# Sheet4.net
KiCad netlist of a schematic drawn in Altium Designer
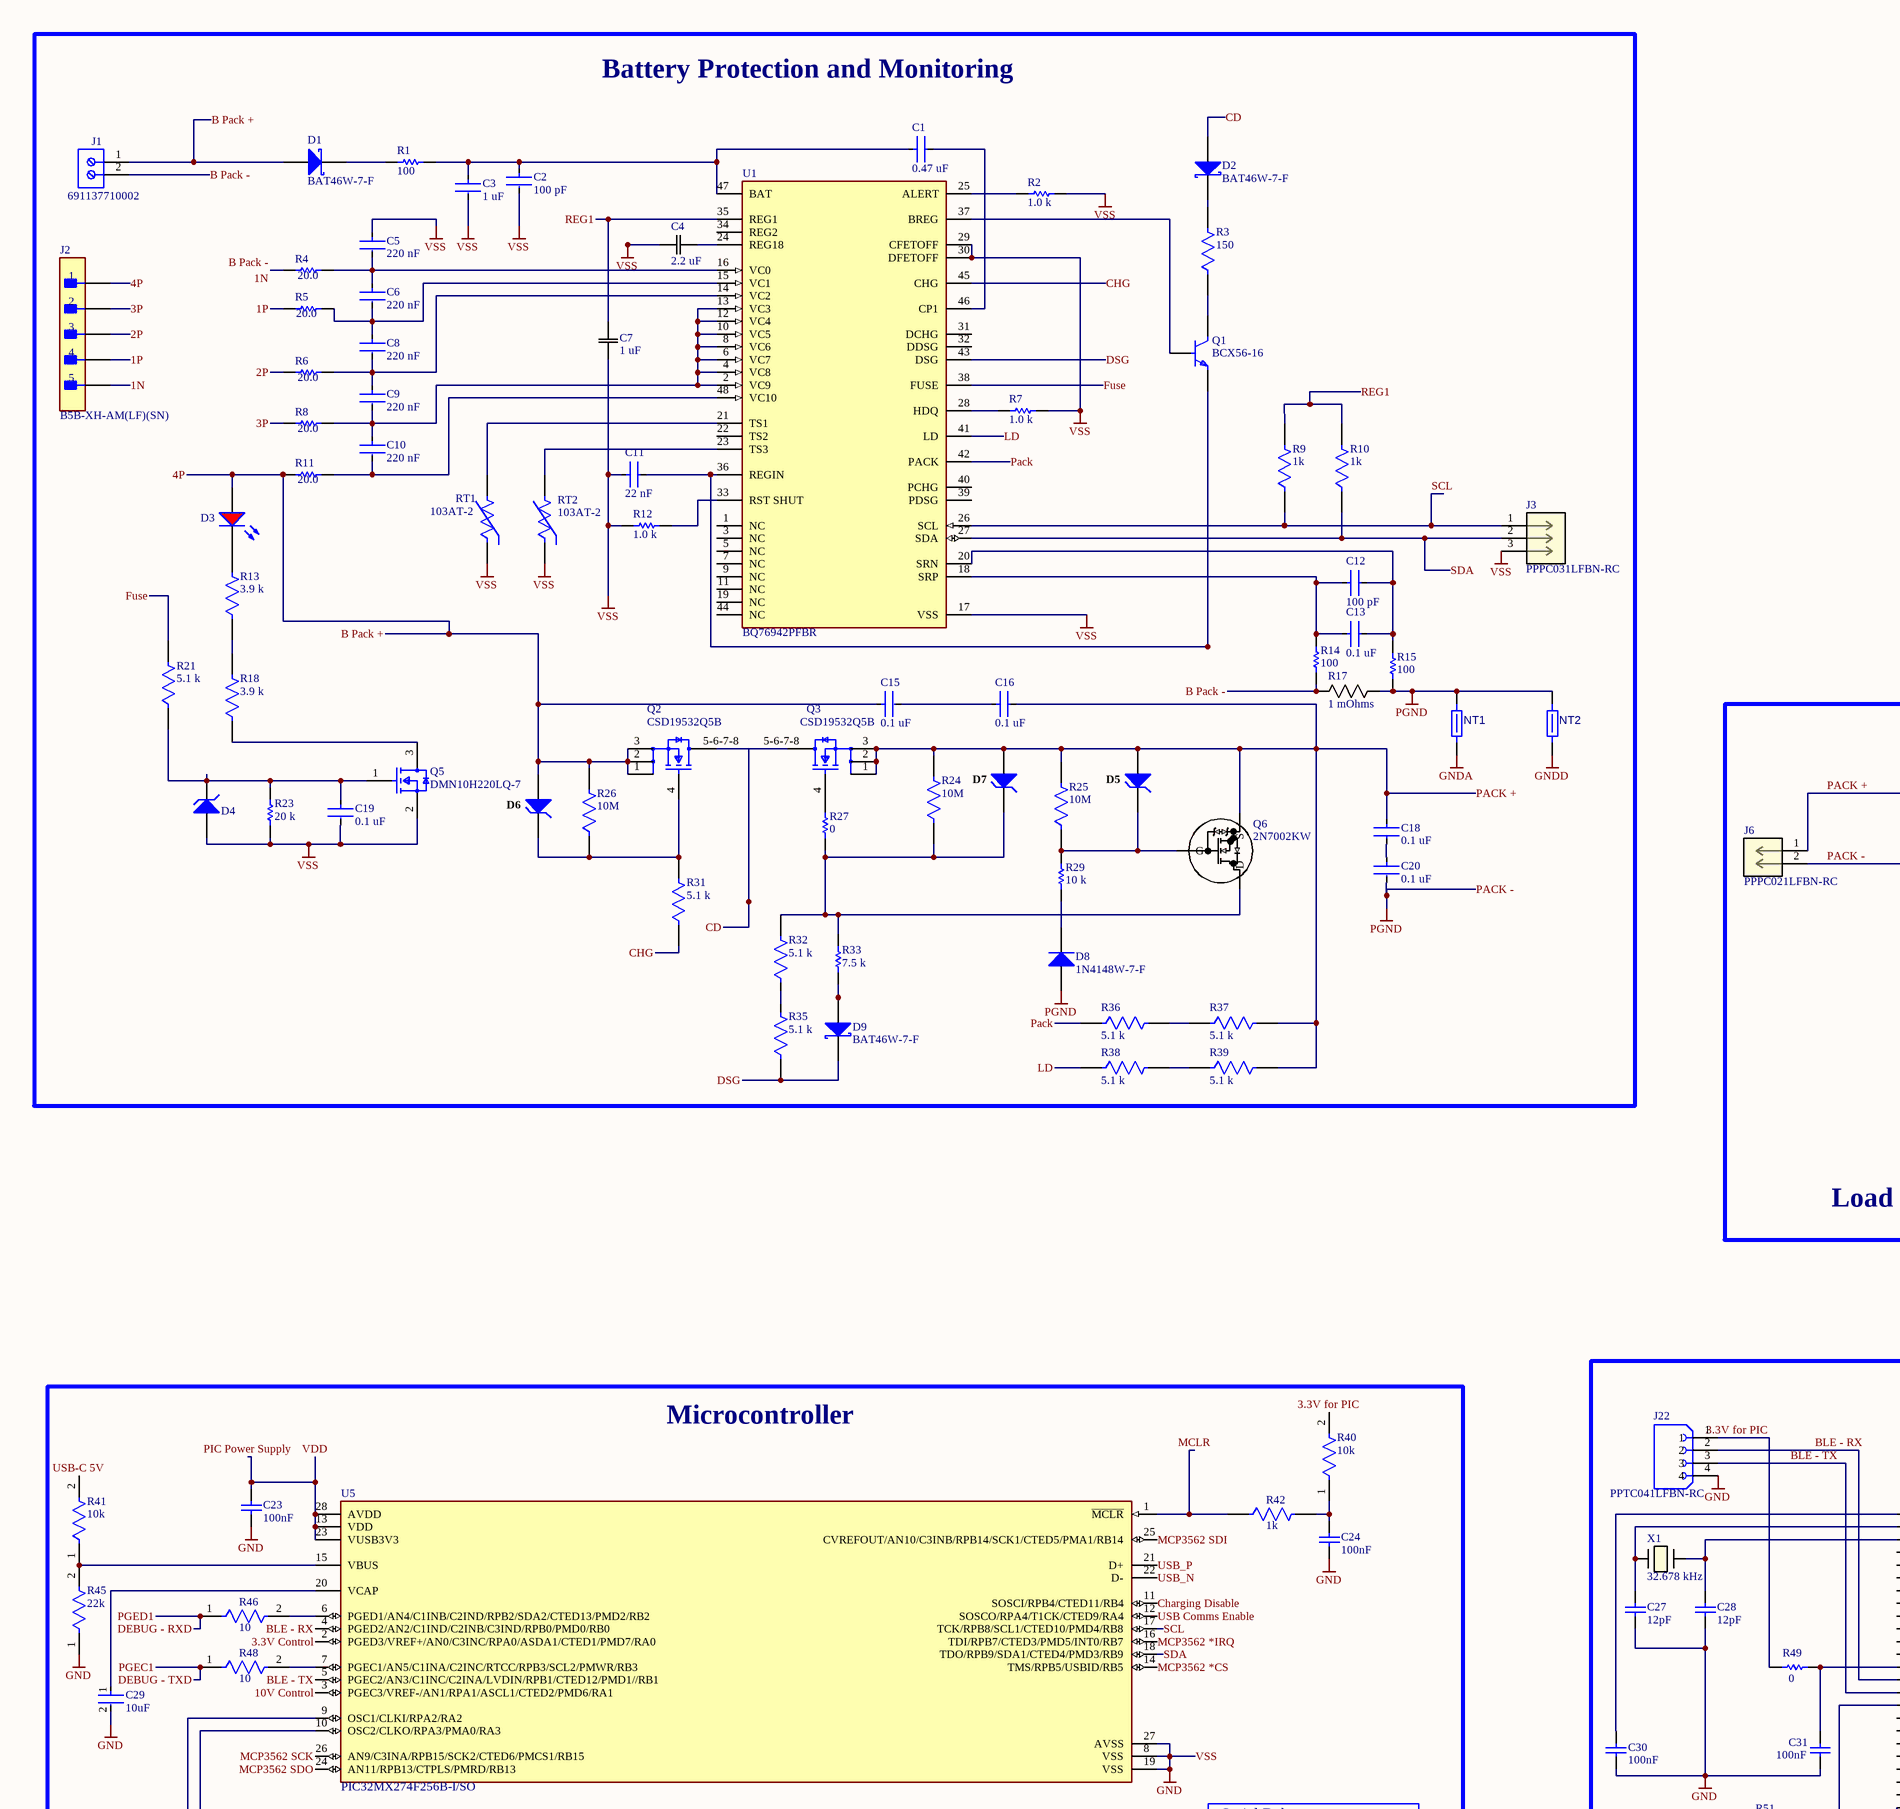
[diagram p0: Sheet4.SchDoc, top left]
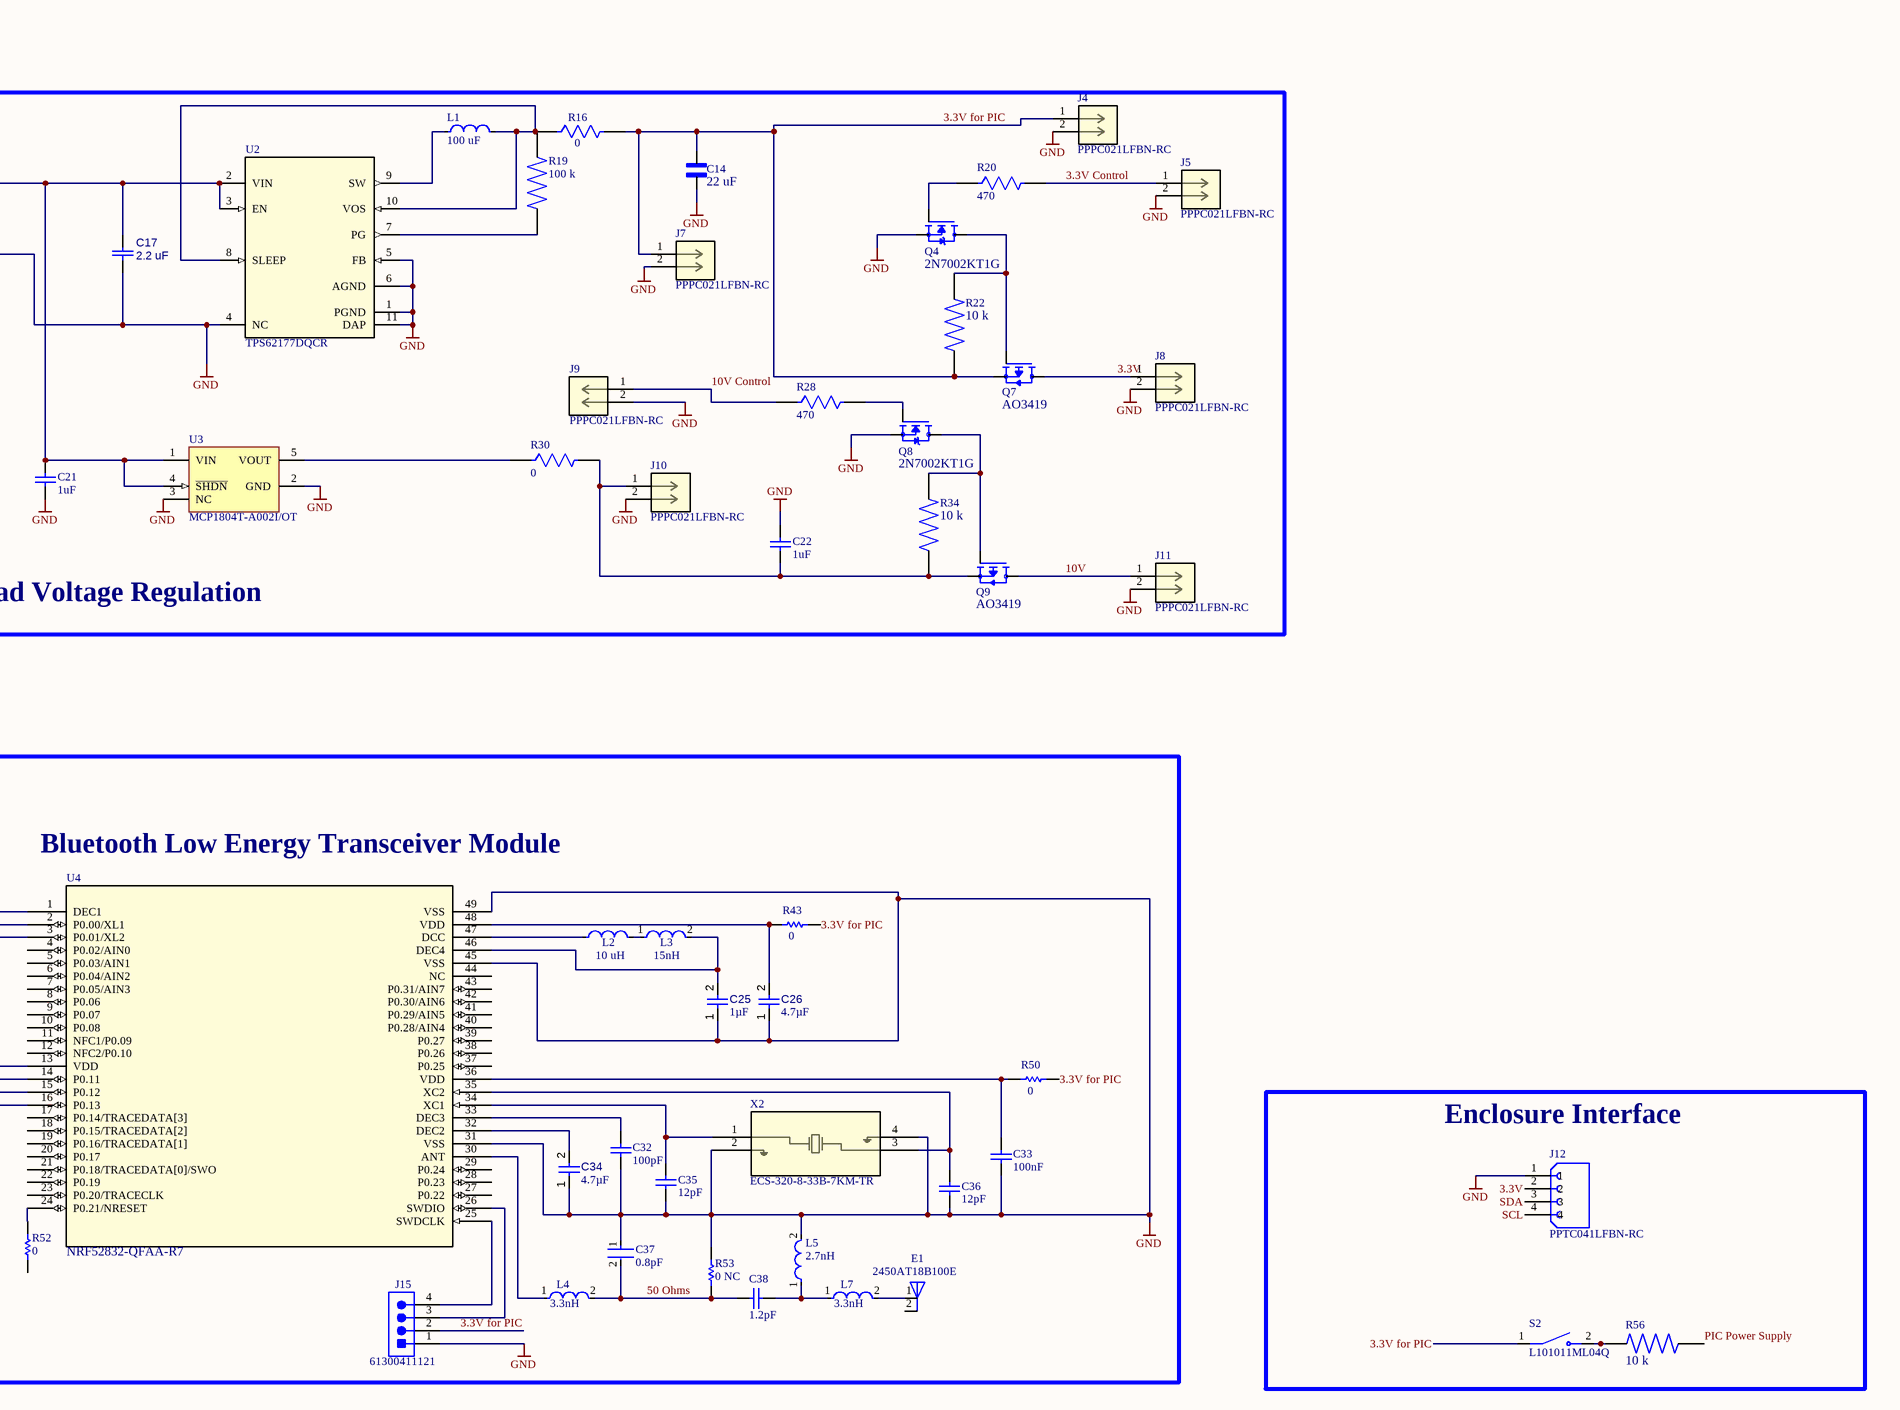
[diagram p1: Sheet4.SchDoc, top right]
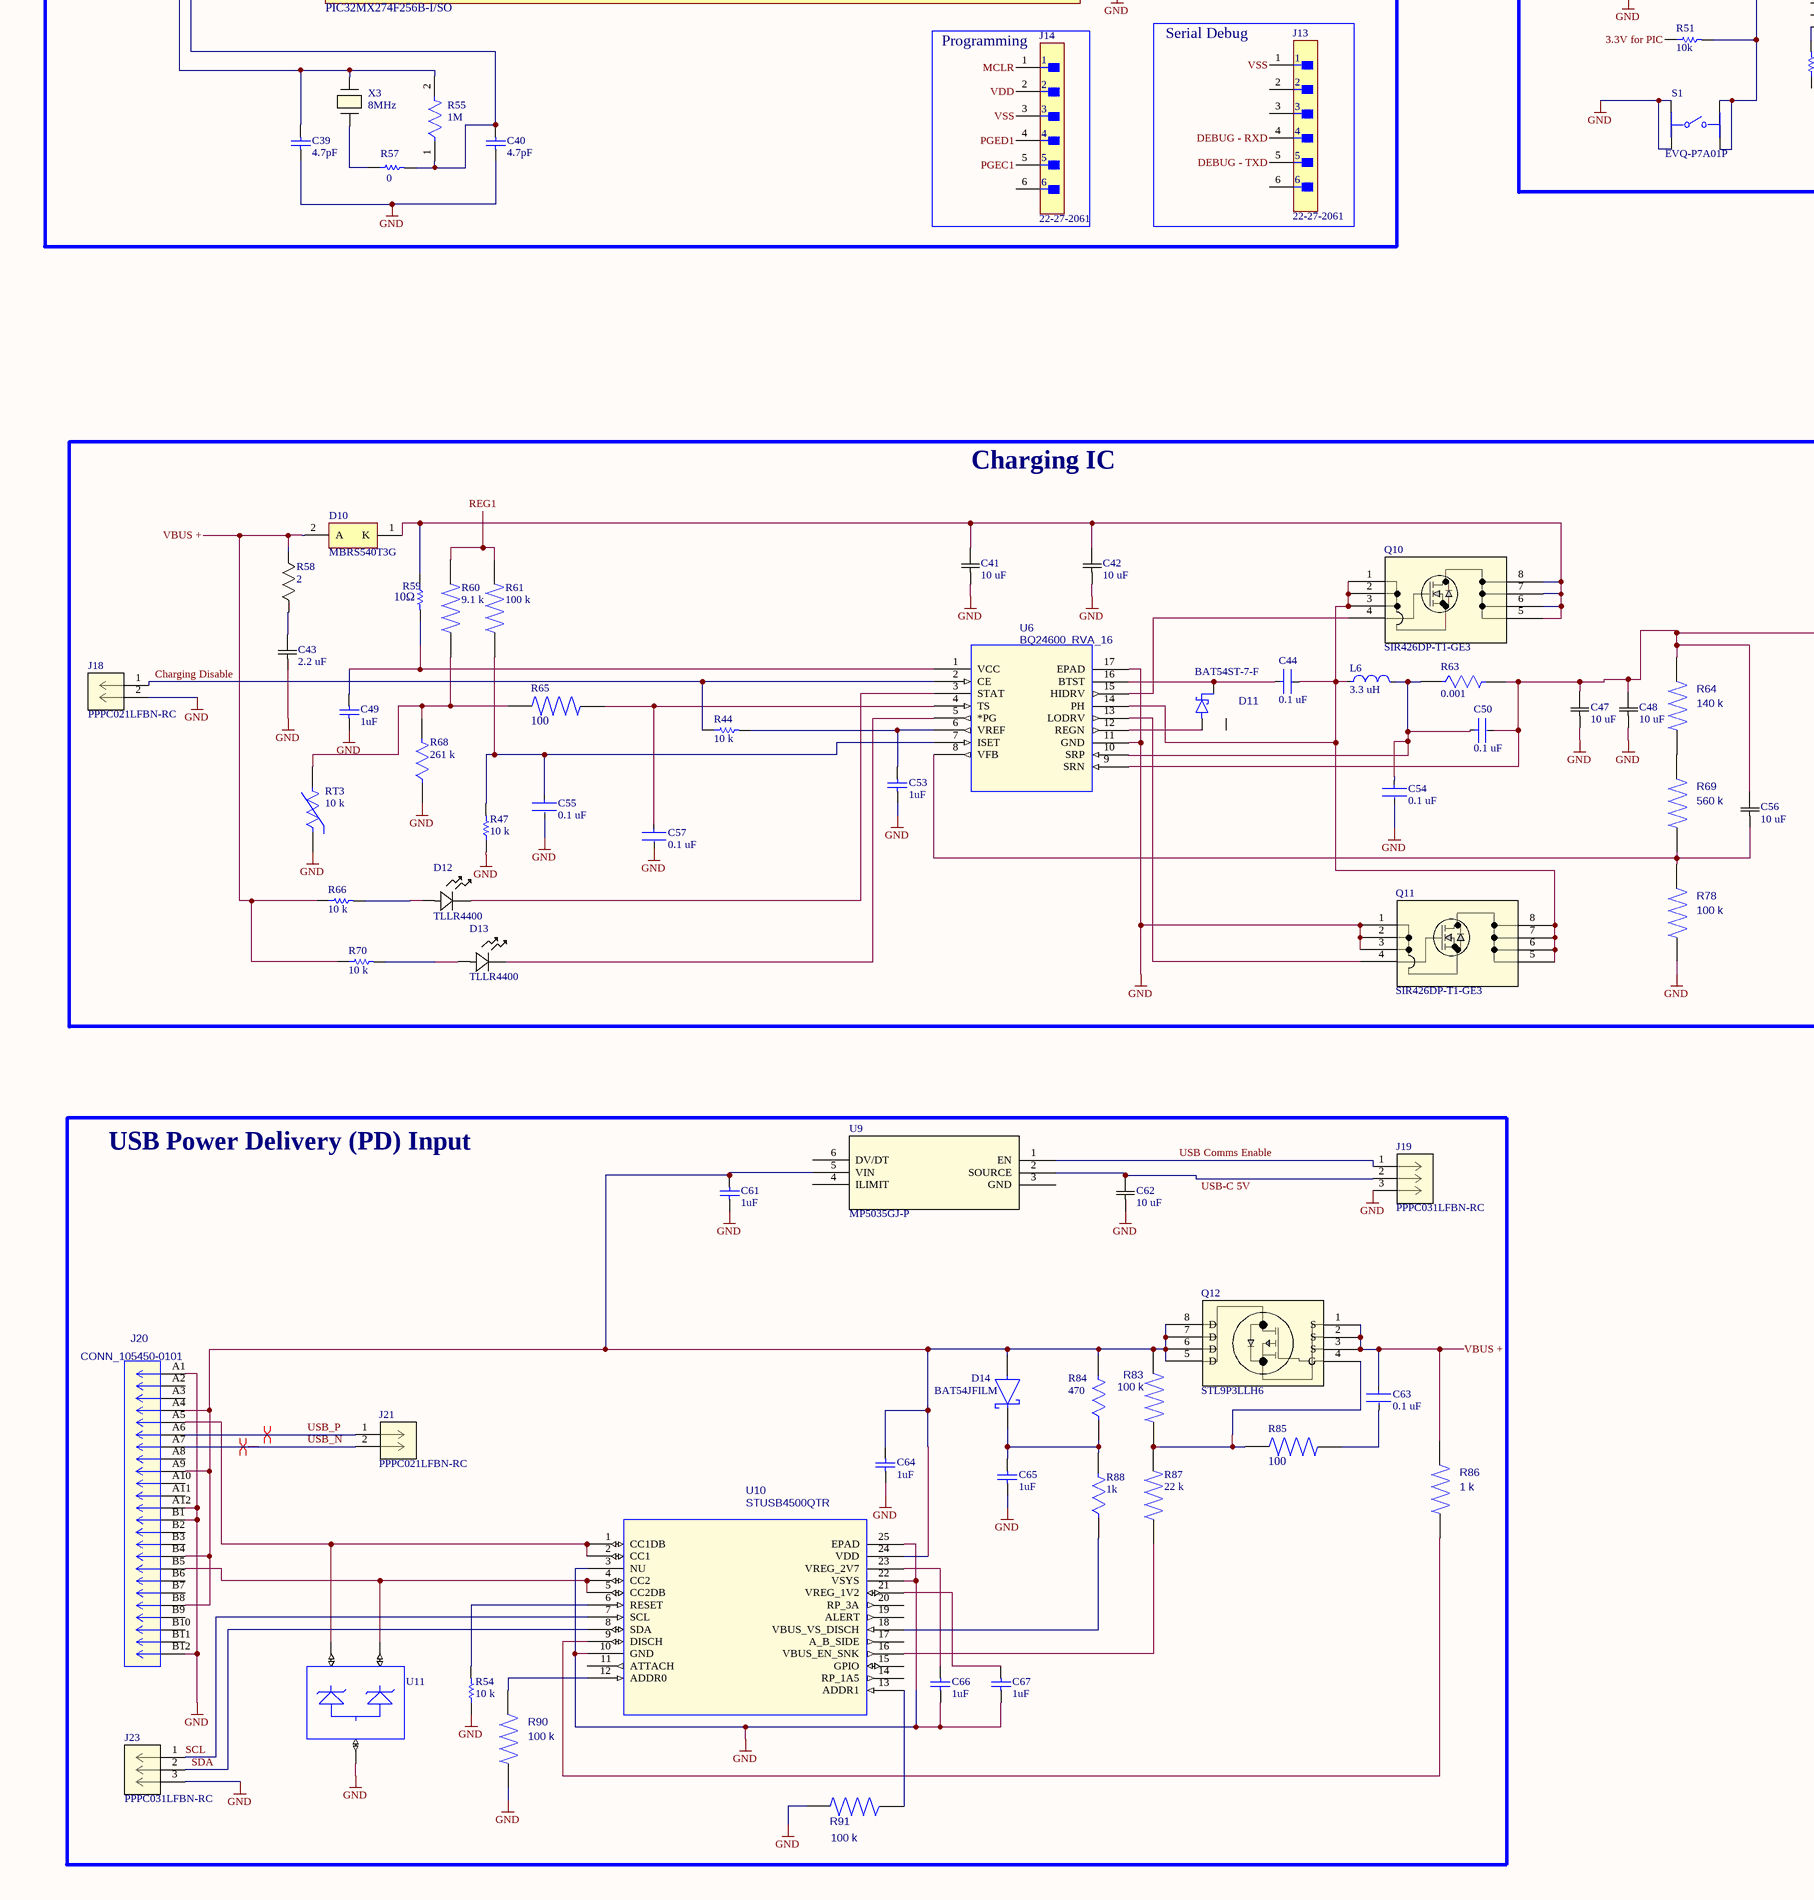
[diagram p2: Sheet4.SchDoc, bottom left]
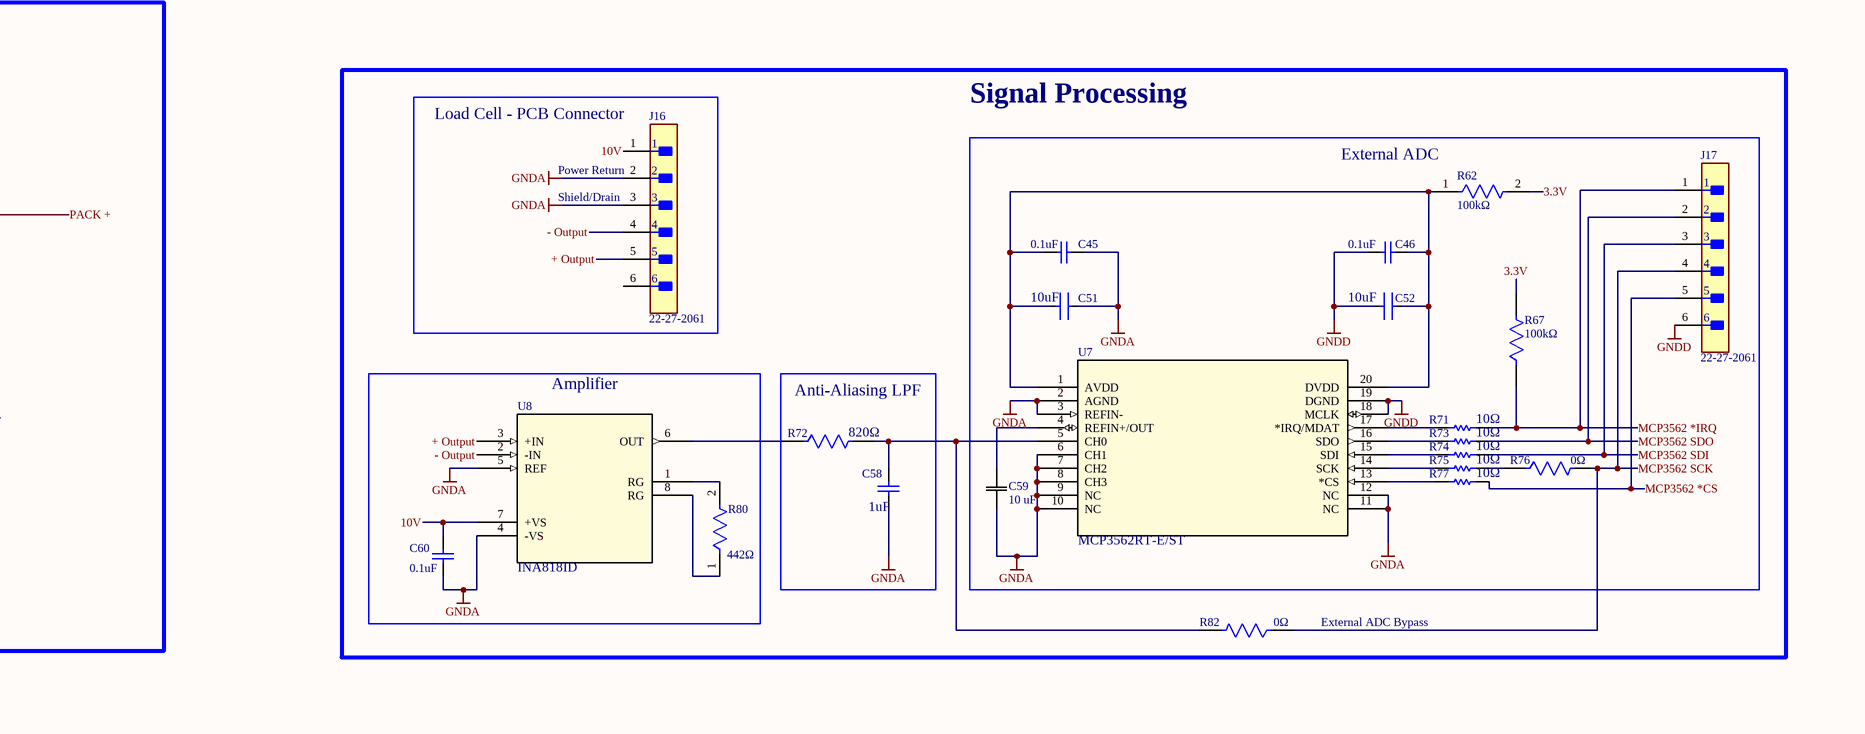
[diagram p3: Sheet4.SchDoc, bottom right]

(export (version "E")
  (design (tool "Eeschema 10.0.6"))
  (components
    (comp (ref "C1")
      (value "0.47 uF")
      (footprint "FP-GCM219-0_15-MFG")
      (description "Ceramic Capacitor for Automotive 470nF  ±10% 25VDC X7R 0805 Paper T/R")
      (fields (field (name "TOLERANCE") "10%"))
      (libsource (lib "Altium Content Vault") (part "11868f565c42a9108669ba33697ecf6"))
    )
    (comp (ref "C2")
      (value "100 pF")
      (footprint "FP-C0805C-DN-MFG")
      (description "CAP CER 100PF 100V C0G/NP0 0805")
      (fields
        (field (name "TOLERANCE") "0.05")
        (field (name "MANUFACTURER PART NUMBER") "C0805C101J1GACAUTO")
      )
      (libsource (lib "Altium Content Vault") (part "b4654b650e69147ec39a6b967a45e02"))
    )
    (comp (ref "C3")
      (value "1 uF")
      (footprint "FP-C3216-160-0_2-IPC_B")
      (description "Multilayer Ceramic Capacitors 1uF ±10% 100V X7R SMD 1206")
      (fields (field (name "TOLERANCE") "10%") (field (name "VOLTAGE") "100V"))
      (libsource (lib "Altium Content Vault") (part "11868f565c42a9108669ba33697ecf6"))
    )
    (comp (ref "C4")
      (value "2.2 uF")
      (footprint "CAPC2012X135N")
      (description "Description")
      (fields
        (field (name "MANUFACTURER_PART_NUMBER") "EMK212B7225KG-T")
        (field (name "COPYRIGHT") "Copyright (C) 2025 Ultra Librarian. All rights reserved.")
      )
      (libsource (lib "EMK212B7225KG-T") (part "EMK212B7225KG-T"))
    )
    (comp (ref "C5")
      (value "220 nF")
      (footprint "FP-C2012-125-0_2-IPC_C")
      (description "Multilayer Ceramic Capacitors 220nF ±10% 50V X7R SMD 0805")
      (fields (field (name "VOLTAGE") "50V") (field (name "TOLERANCE") "10%"))
      (libsource (lib "Altium Content Vault") (part "b4654b650e69147ec39a6b967a45e02"))
    )
    (comp (ref "C6")
      (value "220 nF")
      (footprint "FP-C2012-125-0_2-IPC_C")
      (description "Multilayer Ceramic Capacitors 220nF ±10% 50V X7R SMD 0805")
      (fields (field (name "VOLTAGE") "50V") (field (name "TOLERANCE") "10%"))
      (libsource (lib "Altium Content Vault") (part "b4654b650e69147ec39a6b967a45e02"))
    )
    (comp (ref "C7")
      (value "1 uF")
      (footprint "CAPC2012X135N")
      (description "No Description Available")
      (fields
        (field (name "MANUFACTURER_PART_NUMBER") "EMK212B7105KG-T")
        (field (name "COPYRIGHT") "Copyright (C) 2026 Ultra Librarian. All rights reserved.")
      )
      (libsource (lib "EMK212B7105KG-T") (part "EMK212B7105KG-T"))
    )
    (comp (ref "C8")
      (value "220 nF")
      (footprint "FP-C2012-125-0_2-IPC_C")
      (description "Multilayer Ceramic Capacitors 220nF ±10% 50V X7R SMD 0805")
      (fields (field (name "VOLTAGE") "50V") (field (name "TOLERANCE") "10%"))
      (libsource (lib "Altium Content Vault") (part "b4654b650e69147ec39a6b967a45e02"))
    )
    (comp (ref "C9")
      (value "220 nF")
      (footprint "FP-C2012-125-0_2-IPC_C")
      (description "Multilayer Ceramic Capacitors 220nF ±10% 50V X7R SMD 0805")
      (fields (field (name "VOLTAGE") "50V") (field (name "TOLERANCE") "10%"))
      (libsource (lib "Altium Content Vault") (part "b4654b650e69147ec39a6b967a45e02"))
    )
    (comp (ref "C10")
      (value "220 nF")
      (footprint "FP-C2012-125-0_2-IPC_C")
      (description "Multilayer Ceramic Capacitors 220nF ±10% 50V X7R SMD 0805")
      (fields (field (name "VOLTAGE") "50V") (field (name "TOLERANCE") "10%"))
      (libsource (lib "Altium Content Vault") (part "b4654b650e69147ec39a6b967a45e02"))
    )
    (comp (ref "C11")
      (value "22 nF")
      (footprint "FP-C0805C-DN-MFG")
      (description "CAP CER 0.022UF 16V X7R 0805")
      (fields
        (field (name "MANUFACTURER PART NUMBER") "C0805C223K4RACTU")
        (field (name "OCTOPART") "https://octopart.com/c0805c223k4ractu-kemet-16264534")
      )
      (libsource (lib "Altium Content Vault") (part "b4654b650e69147ec39a6b967a45e02"))
    )
    (comp (ref "C12")
      (value "100 pF")
      (footprint "FP-C0805C-DN-MFG")
      (description "CAP CER 100PF 100V C0G/NP0 0805")
      (fields
        (field (name "TOLERANCE") "0.05")
        (field (name "MANUFACTURER PART NUMBER") "C0805C101J1GACAUTO")
      )
      (libsource (lib "Altium Content Vault") (part "b4654b650e69147ec39a6b967a45e02"))
    )
    (comp (ref "C13")
      (value "0.1 uF")
      (footprint "FP-GCJ21B-0_3-MFG")
      (description "Multilayer Ceramic Capacitors MLCC - SMD/SMT 0805 0.1uF 10%, 100VDC,  X7R 15%")
      (libsource (lib "Altium Content Vault") (part "02cd4be3c70576c341d710602a673aa"))
    )
    (comp (ref "C14")
      (value "22 uF")
      (footprint "CAP_CL32_SAM")
      (description "Capacitor: ceramic; MLCC; 22uF; 25V; X5R; Â±10%; SMD; 1210; -55Ã·85Â°C")
      (fields (field (name "MF") "Samsung Electro-Mechanics") (field (name "MP") "CL32A226KAJNNNE"))
      (libsource (lib "CL32A226KAJNNNE") (part "CL32A226KAJNNNE"))
    )
    (comp (ref "C15")
      (value "0.1 uF")
      (footprint "FP-GCJ21B-0_3-MFG")
      (description "Multilayer Ceramic Capacitors MLCC - SMD/SMT 0805 0.1uF 10%, 100VDC,  X7R 15%")
      (libsource (lib "Altium Content Vault") (part "02cd4be3c70576c341d710602a673aa"))
    )
    (comp (ref "C16")
      (value "0.1 uF")
      (footprint "FP-GCJ21B-0_3-MFG")
      (description "Multilayer Ceramic Capacitors MLCC - SMD/SMT 0805 0.1uF 10%, 100VDC,  X7R 15%")
      (libsource (lib "Altium Content Vault") (part "02cd4be3c70576c341d710602a673aa"))
    )
    (comp (ref "C17")
      (value "2.2 uF")
      (footprint "CAPC3216X180N")
      (fields
        (field (name "MANUFACTURER_PART_NUMBER") "CL31B225KAHNNNE")
        (field (name "COPYRIGHT") "Copyright (C) 2025 Ultra Librarian. All rights reserved.")
      )
      (libsource (lib "*") (part "CL31B225KAHNNNE"))
    )
    (comp (ref "C18")
      (value "0.1 uF")
      (footprint "FP-GCJ21B-0_3-MFG")
      (description "Multilayer Ceramic Capacitors MLCC - SMD/SMT 0805 0.1uF 10%, 100VDC,  X7R 15%")
      (libsource (lib "Altium Content Vault") (part "02cd4be3c70576c341d710602a673aa"))
    )
    (comp (ref "C19")
      (value "0.1 uF")
      (footprint "FP-GCJ21B-0_3-MFG")
      (description "Multilayer Ceramic Capacitors MLCC - SMD/SMT 0805 0.1uF 10%, 100VDC,  X7R 15%")
      (libsource (lib "Altium Content Vault") (part "02cd4be3c70576c341d710602a673aa"))
    )
    (comp (ref "C20")
      (value "0.1 uF")
      (footprint "FP-GCJ21B-0_3-MFG")
      (description "Multilayer Ceramic Capacitors MLCC - SMD/SMT 0805 0.1uF 10%, 100VDC,  X7R 15%")
      (libsource (lib "Altium Content Vault") (part "02cd4be3c70576c341d710602a673aa"))
    )
    (comp (ref "C21")
      (value "1uF")
      (footprint "CAPC1206(3216)150_M")
      (description "CAP 1uF 6.3V ±10% 1206 (3216 Metric) Thickness 1.45mm SMD")
      (fields (field (name "TOLERANCE") "Â±10%"))
      (libsource (lib "Altium Content Vault") (part "CAP"))
    )
    (comp (ref "C22")
      (value "1uF")
      (footprint "CAPC1206(3216)150_M")
      (description "CAP 1uF 6.3V ±10% 1206 (3216 Metric) Thickness 1.45mm SMD")
      (fields (field (name "TOLERANCE") "Â±10%"))
      (libsource (lib "Altium Content Vault") (part "CAP"))
    )
    (comp (ref "C23")
      (value "100nF")
      (footprint "CAPC2013X145X48NL20T23")
      (fields (field (name "MANUFACTURER") "Vitramon") (field (name "PART NUMBER") "VJ0805Y104MXXMT"))
      (libsource (lib "Altium Content Vault") (part "CAP"))
    )
    (comp (ref "C24")
      (value "100nF")
      (footprint "CAPC2013X145X48NL20T23")
      (fields (field (name "MANUFACTURER") "Vitramon") (field (name "PART NUMBER") "VJ0805Y104MXXMT"))
      (libsource (lib "Altium Content Vault") (part "CAP"))
    )
    (comp (ref "C25")
      (value "1µF")
      (footprint "CAPC2013X145X50ML20T25")
      (description "Chip Capacitor, 1 uF, +/-10%, 25 V, 0805 (2012 Metric)")
      (fields (field (name "TOLERANCE") "10%") (field (name "Comment") "Capacitor 1 uF +/- 10% 25 V 0805"))
      (libsource (lib "UNB Workspace") (part "47uF Capacitor"))
    )
    (comp (ref "C26")
      (value "4.7µF")
      (footprint "CAPC0805(2012)145_L")
      (description "Chip Capacitor, 4.7µF +/-40%, 25V, 0805, Thickness 1.45 mm")
      (fields (field (name "TOLERANCE") "20%") (field (name "Comment") "Capacitor 4.7µF +/-40% 25V 0805"))
      (libsource (lib "UNB Workspace") (part "47uF Capacitor"))
    )
    (comp (ref "C27")
      (value "12pF")
      (footprint "CAPC0805(2012)145_M")
      (description "CAP 12pF 100V ±10% 0805 (2012 Metric) Thickness 1.45mm SMD")
      (fields (field (name "TOLERANCE") "Â±10%"))
      (libsource (lib "Altium Content Vault") (part "CAP"))
    )
    (comp (ref "C28")
      (value "12pF")
      (footprint "CAPC0805(2012)145_M")
      (description "CAP 12pF 100V ±10% 0805 (2012 Metric) Thickness 1.45mm SMD")
      (fields (field (name "TOLERANCE") "Â±10%"))
      (libsource (lib "Altium Content Vault") (part "CAP"))
    )
    (comp (ref "C29")
      (value "10uF")
      (footprint "FP-C0805C106K3PACTU-MFG")
      (description "CAP CER 10UF 25V X5R 0805")
      (fields (field (name "TOLERANCE") "10%") (field (name "VOLTAGE") "25V"))
      (libsource (lib "") (part "b4654b650e69147ec39a6b967a45e02_1"))
    )
    (comp (ref "C30")
      (value "100nF")
      (footprint "CAPC2013X145X48NL20T23")
      (fields (field (name "MANUFACTURER") "Vitramon") (field (name "PART NUMBER") "VJ0805Y104MXXMT"))
      (libsource (lib "Altium Content Vault") (part "CAP"))
    )
    (comp (ref "C31")
      (value "100nF")
      (footprint "CAPC2013X145X48NL20T23")
      (fields (field (name "MANUFACTURER") "Vitramon") (field (name "PART NUMBER") "VJ0805Y104MXXMT"))
      (libsource (lib "Altium Content Vault") (part "CAP"))
    )
    (comp (ref "C32")
      (value "100pF")
      (footprint "CAPC2013X145X48NL20T23")
      (fields (field (name "MANUFACTURER") "Vitramon") (field (name "PART NUMBER") "VJ0805Y104MXXMT"))
      (libsource (lib "Altium Content Vault") (part "CAP"))
    )
    (comp (ref "C33")
      (value "100nF")
      (footprint "CAPC2013X145X48NL20T23")
      (fields (field (name "MANUFACTURER") "Vitramon") (field (name "PART NUMBER") "VJ0805Y104MXXMT"))
      (libsource (lib "Altium Content Vault") (part "CAP"))
    )
    (comp (ref "C34")
      (value "4.7µF")
      (footprint "CAPC0805(2012)145_L")
      (description "Chip Capacitor, 4.7µF +/-40%, 25V, 0805, Thickness 1.45 mm")
      (fields (field (name "TOLERANCE") "20%") (field (name "Comment") "Capacitor 4.7µF +/-40% 25V 0805"))
      (libsource (lib "UNB Workspace") (part "47uF Capacitor"))
    )
    (comp (ref "C35")
      (value "12pF")
      (footprint "CAPC0805(2012)145_M")
      (description "CAP 12pF 100V ±10% 0805 (2012 Metric) Thickness 1.45mm SMD")
      (fields (field (name "TOLERANCE") "Â±10%"))
      (libsource (lib "Altium Content Vault") (part "CAP"))
    )
    (comp (ref "C36")
      (value "12pF")
      (footprint "CAPC0805(2012)145_M")
      (description "CAP 12pF 100V ±10% 0805 (2012 Metric) Thickness 1.45mm SMD")
      (fields (field (name "TOLERANCE") "Â±10%"))
      (libsource (lib "Altium Content Vault") (part "CAP"))
    )
    (comp (ref "C37")
      (value "0.8pF")
      (footprint "FP-CBR08C-MFG")
      (description "CAP CER 0.8PF 250V C0G/NP0 0805")
      (fields
        (field (name "OCTOPART") "https://octopart.com/cbr08c808bagac-kemet-23841679")
        (field (name "TOLERANCE") "0.1 pF")
      )
      (libsource (lib "") (part "11868f565c42a9108669ba33697ecf6_1"))
    )
    (comp (ref "C38")
      (value "1.2pF")
      (footprint "CAPC0805(2012)145_M")
      (description "CAP 1pF 100V ±0.1pF 0805 (2012 Metric) Thickness 1.45mm SMD")
      (fields (field (name "TOLERANCE") "Â±0.1pF"))
      (libsource (lib "Altium Content Vault") (part "CAP"))
    )
    (comp (ref "C39")
      (value "4.7pF")
      (footprint "CAPC0805(2012)75_N")
      (description "CAP 4.7pF 25V ±0.1pF 0805 (2012 Metric) Thickness 0.75mm SMD")
      (fields (field (name "TOLERANCE") "Â±0.1pF"))
      (libsource (lib "Altium Content Vault") (part "CAP"))
    )
    (comp (ref "C40")
      (value "4.7pF")
      (footprint "CAPC0805(2012)75_N")
      (description "CAP 4.7pF 25V ±0.1pF 0805 (2012 Metric) Thickness 0.75mm SMD")
      (fields (field (name "TOLERANCE") "Â±0.1pF"))
      (libsource (lib "Altium Content Vault") (part "CAP"))
    )
    (comp (ref "C41")
      (value "10 uF")
      (footprint "CAP_CL31_SAM")
      (description "Description")
      (fields
        (field (name "MANUFACTURER_PART_NUMBER") "CL31B106KAHNNNE")
        (field (name "COPYRIGHT") "Copyright (C) 2025 Ultra Librarian. All rights reserved.")
      )
      (libsource (lib "CL31B106KAHNNNE") (part "CL31B106KAHNNNE"))
    )
    (comp (ref "C42")
      (value "10 uF")
      (footprint "CAP_CL31_SAM")
      (description "Description")
      (fields
        (field (name "MANUFACTURER_PART_NUMBER") "CL31B106KAHNNNE")
        (field (name "COPYRIGHT") "Copyright (C) 2025 Ultra Librarian. All rights reserved.")
      )
      (libsource (lib "CL31B106KAHNNNE") (part "CL31B106KAHNNNE"))
    )
    (comp (ref "C43")
      (value "2.2 uF")
      (footprint "CAPC2012X135N")
      (description "Description")
      (fields
        (field (name "MANUFACTURER_PART_NUMBER") "EMK212B7225KG-T")
        (field (name "COPYRIGHT") "Copyright (C) 2025 Ultra Librarian. All rights reserved.")
      )
      (libsource (lib "EMK212B7225KG-T") (part "EMK212B7225KG-T"))
    )
    (comp (ref "C44")
      (value "0.1 uF")
      (footprint "FP-CC1206-1_25-MFG")
      (description "CAP CER 0.1UF 25V X7R 1206")
      (fields (field (name "TOLERANCE") "0.1") (field (name "MANUFACTURER PART NUMBER") "CC1206KRX7R8BB104"))
      (libsource (lib "Altium Content Vault") (part "11868f565c42a9108669ba33697ecf6"))
    )
    (comp (ref "C45")
      (value "0.1uF")
      (footprint "CAPC2013X145X50NL20T25")
      (fields (field (name "MANUFACTURER") "Kemet") (field (name "PART NUMBER") "C0805S104K5RACTU"))
      (libsource (lib "Altium Content Vault") (part "CAP"))
    )
    (comp (ref "C46")
      (value "0.1uF")
      (footprint "CAPC2013X145X50NL20T25")
      (fields (field (name "MANUFACTURER") "Kemet") (field (name "PART NUMBER") "C0805S104K5RACTU"))
      (libsource (lib "Altium Content Vault") (part "CAP"))
    )
    (comp (ref "C47")
      (value "10 uF")
      (footprint "CAP_CL31_SAM")
      (description "Description")
      (fields
        (field (name "MANUFACTURER_PART_NUMBER") "CL31B106KAHNNNE")
        (field (name "COPYRIGHT") "Copyright (C) 2025 Ultra Librarian. All rights reserved.")
      )
      (libsource (lib "CL31B106KAHNNNE") (part "CL31B106KAHNNNE"))
    )
    (comp (ref "C48")
      (value "10 uF")
      (footprint "CAP_CL31_SAM")
      (description "Description")
      (fields
        (field (name "MANUFACTURER_PART_NUMBER") "CL31B106KAHNNNE")
        (field (name "COPYRIGHT") "Copyright (C) 2025 Ultra Librarian. All rights reserved.")
      )
      (libsource (lib "CL31B106KAHNNNE") (part "CL31B106KAHNNNE"))
    )
    (comp (ref "C49")
      (value "1uF")
      (footprint "CAPC1206(3216)150_M")
      (description "CAP 1uF 6.3V ±10% 1206 (3216 Metric) Thickness 1.45mm SMD")
      (fields (field (name "TOLERANCE") "Â±10%"))
      (libsource (lib "Altium Content Vault") (part "CAP"))
    )
    (comp (ref "C50")
      (value "0.1 uF")
      (footprint "FP-CC1206-1_25-MFG")
      (description "CAP CER 0.1UF 25V X7R 1206")
      (fields (field (name "TOLERANCE") "0.1") (field (name "MANUFACTURER PART NUMBER") "CC1206KRX7R8BB104"))
      (libsource (lib "Altium Content Vault") (part "11868f565c42a9108669ba33697ecf6"))
    )
    (comp (ref "C51")
      (value "10uF")
      (footprint "FP-CL21B106KOQNNNE-MFG")
      (description "CAP CER 10UF 16V X7R 0805")
      (fields
        (field (name "MANUFACTURER PART NUMBER") "CL21B106KOQNNNE")
        (field (name "OCTOPART") "https://octopart.com/cl21b106koqnnne-samsung-19832289")
      )
      (libsource (lib "Altium Content Vault") (part "236180d848d6139a670b325ea6854c9"))
    )
    (comp (ref "C52")
      (value "10uF")
      (footprint "FP-CL21B106KOQNNNE-MFG")
      (description "CAP CER 10UF 16V X7R 0805")
      (fields
        (field (name "MANUFACTURER PART NUMBER") "CL21B106KOQNNNE")
        (field (name "OCTOPART") "https://octopart.com/cl21b106koqnnne-samsung-19832289")
      )
      (libsource (lib "Altium Content Vault") (part "236180d848d6139a670b325ea6854c9"))
    )
    (comp (ref "C53")
      (value "1uF")
      (footprint "CAPC1206(3216)150_M")
      (description "CAP 1uF 6.3V ±10% 1206 (3216 Metric) Thickness 1.45mm SMD")
      (fields (field (name "TOLERANCE") "Â±10%"))
      (libsource (lib "Altium Content Vault") (part "CAP"))
    )
    (comp (ref "C54")
      (value "0.1 uF")
      (footprint "FP-CC1206-1_25-MFG")
      (description "CAP CER 0.1UF 25V X7R 1206")
      (fields (field (name "TOLERANCE") "0.1") (field (name "MANUFACTURER PART NUMBER") "CC1206KRX7R8BB104"))
      (libsource (lib "Altium Content Vault") (part "11868f565c42a9108669ba33697ecf6"))
    )
    (comp (ref "C55")
      (value "0.1 uF")
      (footprint "FP-CC1206-1_25-MFG")
      (description "CAP CER 0.1UF 25V X7R 1206")
      (fields (field (name "TOLERANCE") "0.1") (field (name "MANUFACTURER PART NUMBER") "CC1206KRX7R8BB104"))
      (libsource (lib "Altium Content Vault") (part "11868f565c42a9108669ba33697ecf6"))
    )
    (comp (ref "C56")
      (value "10 uF")
      (footprint "CAP_CL31_SAM")
      (description "Description")
      (fields
        (field (name "MANUFACTURER_PART_NUMBER") "CL31B106KAHNNNE")
        (field (name "COPYRIGHT") "Copyright (C) 2025 Ultra Librarian. All rights reserved.")
      )
      (libsource (lib "CL31B106KAHNNNE") (part "CL31B106KAHNNNE"))
    )
    (comp (ref "C57")
      (value "0.1 uF")
      (footprint "FP-CC1206-1_25-MFG")
      (description "CAP CER 0.1UF 25V X7R 1206")
      (fields (field (name "TOLERANCE") "0.1") (field (name "MANUFACTURER PART NUMBER") "CC1206KRX7R8BB104"))
      (libsource (lib "Altium Content Vault") (part "11868f565c42a9108669ba33697ecf6"))
    )
    (comp (ref "C58")
      (value "1uF")
      (footprint "CAPC2013X145X50LL20T25")
      (fields (field (name "MANUFACTURER") "Kemet") (field (name "PART NUMBER") "C0805C105K4PACTU"))
      (libsource (lib "Altium Content Vault") (part "CAP"))
    )
    (comp (ref "C59")
      (value "10 uF")
      (footprint "CAP_CL31_SAM")
      (description "Description")
      (fields
        (field (name "MANUFACTURER_PART_NUMBER") "CL31B106KAHNNNE")
        (field (name "COPYRIGHT") "Copyright (C) 2025 Ultra Librarian. All rights reserved.")
      )
      (libsource (lib "CL31B106KAHNNNE") (part "CL31B106KAHNNNE"))
    )
    (comp (ref "C60")
      (value "0.1uF")
      (footprint "CAPC2013X145X50NL20T25")
      (fields (field (name "MANUFACTURER") "Kemet") (field (name "PART NUMBER") "C0805S104K5RACTU"))
      (libsource (lib "Altium Content Vault") (part "CAP"))
    )
    (comp (ref "C61")
      (value "1uF")
      (footprint "CAPC1206(3216)150_M")
      (description "CAP 1uF 6.3V ±10% 1206 (3216 Metric) Thickness 1.45mm SMD")
      (fields (field (name "TOLERANCE") "Â±10%"))
      (libsource (lib "Altium Content Vault") (part "CAP"))
    )
    (comp (ref "C62")
      (value "10 uF")
      (footprint "CAP_CL31_SAM")
      (description "Description")
      (fields
        (field (name "MANUFACTURER_PART_NUMBER") "CL31B106KAHNNNE")
        (field (name "COPYRIGHT") "Copyright (C) 2025 Ultra Librarian. All rights reserved.")
      )
      (libsource (lib "CL31B106KAHNNNE") (part "CL31B106KAHNNNE"))
    )
    (comp (ref "C63")
      (value "0.1 uF")
      (footprint "FP-CC1206-1_25-MFG")
      (description "CAP CER 0.1UF 25V X7R 1206")
      (fields (field (name "TOLERANCE") "0.1") (field (name "MANUFACTURER PART NUMBER") "CC1206KRX7R8BB104"))
      (libsource (lib "Altium Content Vault") (part "11868f565c42a9108669ba33697ecf6"))
    )
    (comp (ref "C64")
      (value "1uF")
      (footprint "CAPC1206(3216)150_M")
      (description "CAP 1uF 6.3V ±10% 1206 (3216 Metric) Thickness 1.45mm SMD")
      (fields (field (name "TOLERANCE") "Â±10%"))
      (libsource (lib "Altium Content Vault") (part "CAP"))
    )
    (comp (ref "C65")
      (value "1uF")
      (footprint "CAPC1206(3216)150_M")
      (description "CAP 1uF 6.3V ±10% 1206 (3216 Metric) Thickness 1.45mm SMD")
      (fields (field (name "TOLERANCE") "Â±10%"))
      (libsource (lib "Altium Content Vault") (part "CAP"))
    )
    (comp (ref "C66")
      (value "1uF")
      (footprint "CAPC1206(3216)150_M")
      (description "CAP 1uF 6.3V ±10% 1206 (3216 Metric) Thickness 1.45mm SMD")
      (fields (field (name "TOLERANCE") "Â±10%"))
      (libsource (lib "Altium Content Vault") (part "CAP"))
    )
    (comp (ref "C67")
      (value "1uF")
      (footprint "CAPC1206(3216)150_M")
      (description "CAP 1uF 6.3V ±10% 1206 (3216 Metric) Thickness 1.45mm SMD")
      (fields (field (name "TOLERANCE") "Â±10%"))
      (libsource (lib "Altium Content Vault") (part "CAP"))
    )
    (comp (ref "D1")
      (value "BAT46W-7-F")
      (footprint "DIOD-SOD-123-2_V")
      (description "Surface Mount Schottky Barrier Diode, 100 V, -55 to 125 degC, 2-Pin SOD123, RoHS, Tape and Reel")
      (fields (field (name "MANUFACTURER") "Diodes Inc"))
      (libsource (lib "Altium Content Vault") (part "DIOD-DSKY-A1K2-2"))
    )
    (comp (ref "D2")
      (value "BAT46W-7-F")
      (footprint "DIOD-SOD-123-2_V")
      (description "Surface Mount Schottky Barrier Diode, 100 V, -55 to 125 degC, 2-Pin SOD123, RoHS, Tape and Reel")
      (fields (field (name "MANUFACTURER") "Diodes Inc"))
      (libsource (lib "Altium Content Vault") (part "DIOD-DSKY-A1K2-2"))
    )
    (comp (ref "D3")
      (value "150060RS75000")
      (footprint "WL-SMCW_0603_150060xx75000")
      (description "LED Low-Power Uni-Color Red 630nm 2V 2-Pin Chip 0603(1608Metric) T/R")
      (libsource (lib "Altium Content Vault") (part "LED_Red_2A-1K"))
    )
    (comp (ref "D4")
      (value "MMSZ4697T1G")
      (footprint "ONSC-SOD-123-2-425-04_V")
      (description "Zener Voltage Regulator, 500 mW, 2-Pin SOD-123, Pb-Free, Tape and Reel")
      (fields (field (name "MANUFACTURER") "On Semiconductor"))
      (libsource (lib "Altium Content Vault") (part "ONSC-K1A2-2"))
    )
    (comp (ref "D5")
      (value "MMSZ5246B-E3-08")
      (footprint "VISH-SOD-123-2_V")
      (description "Small Signal Zener Diode, 16 V +/- 5%, -55 to 155 degC, 2-Pin SOD-123, RoHS, Tape and Reel")
      (fields (field (name "MANUFACTURER") "Vishay Semiconductor") (field (name "TOLERANCE") "+/- 5%"))
      (libsource (lib "Altium Content Vault") (part "VISH-DZEN_A1K2-2"))
    )
    (comp (ref "D6")
      (value "MMSZ5246B-E3-08")
      (footprint "VISH-SOD-123-2_V")
      (description "Small Signal Zener Diode, 16 V +/- 5%, -55 to 155 degC, 2-Pin SOD-123, RoHS, Tape and Reel")
      (fields (field (name "MANUFACTURER") "Vishay Semiconductor") (field (name "TOLERANCE") "+/- 5%"))
      (libsource (lib "Altium Content Vault") (part "VISH-DZEN_A1K2-2"))
    )
    (comp (ref "D7")
      (value "MMSZ5246B-E3-08")
      (footprint "VISH-SOD-123-2_V")
      (description "Small Signal Zener Diode, 16 V +/- 5%, -55 to 155 degC, 2-Pin SOD-123, RoHS, Tape and Reel")
      (fields (field (name "MANUFACTURER") "Vishay Semiconductor") (field (name "TOLERANCE") "+/- 5%"))
      (libsource (lib "Altium Content Vault") (part "VISH-DZEN_A1K2-2"))
    )
    (comp (ref "D8")
      (value "1N4148W-7-F")
      (footprint "DIOD-SOD123-2_V")
      (description "Fast Switching Diode, 100 V, 0.15 A, -65 to 150 degC, 2-Pin?SOD123, RoHS, Tape and Reel")
      (fields (field (name "MANUFACTURER") "DiodesIncorporated"))
      (libsource (lib "Altium Content Vault") (part "D-AK-2"))
    )
    (comp (ref "D9")
      (value "BAT46W-7-F")
      (footprint "DIOD-SOD-123-2_V")
      (description "Surface Mount Schottky Barrier Diode, 100 V, -55 to 125 degC, 2-Pin SOD123, RoHS, Tape and Reel")
      (fields (field (name "MANUFACTURER") "Diodes Inc"))
      (libsource (lib "Altium Content Vault") (part "DIOD-DSKY-A1K2-2"))
    )
    (comp (ref "D10")
      (value "MBRS540T3G")
      (footprint "ONSC-SMC-2-403-03_V")
      (description "Schottky Power Rectifier, 2-Pin SMC, Pb-Free, Tape and Reel")
      (fields (field (name "MANUFACTURER") "On Semiconductor"))
      (libsource (lib "Altium Content Vault") (part "ONSC-D-K1A2-2_A"))
    )
    (comp (ref "D11")
      (value "~")
      (footprint "SOT523_DIO")
      (description "Schottky, SOT-23, 30V, 0.2A, 150C")
      (fields
        (field (name "MF") "Diotec")
        (field (name "MP") "BAT54")
        (field (name "SUPPLIER PART NUMBER 1") "BAT54ST-7-F")
      )
      (libsource (lib "BAT54ST-7-F") (part "BAT54"))
    )
    (comp (ref "D12")
      (value "TLLR4400")
      (footprint "TLL_Series_VIS")
      (description "3MM LED RED LC TINT. DIFF-e3")
      (fields (field (name "COPYRIGHT") "Copyright (C) 2025 Ultra Librarian. All rights reserved."))
      (libsource (lib "TLLR4400") (part "TLLR4400"))
    )
    (comp (ref "D13")
      (value "TLLR4400")
      (footprint "TLL_Series_VIS")
      (description "3MM LED RED LC TINT. DIFF-e3")
      (fields (field (name "COPYRIGHT") "Copyright (C) 2025 Ultra Librarian. All rights reserved."))
      (libsource (lib "TLLR4400") (part "TLLR4400"))
    )
    (comp (ref "D14")
      (value "BAT54JFILM")
      (footprint "FP-SOD323-MFG")
      (description "DIODE SCHOTTKY 40V 300MA SOD323")
      (fields
        (field (name "OCTOPART") "https://octopart.com/bat54jfilm-stmicroelectronics-326073")
        (field (name "MANUFACTURER") "STMicroelectronics")
      )
      (libsource (lib "Altium Content Vault") (part "1d6ec82d83fb6aee721767c19dac4b9"))
    )
    (comp (ref "E1")
      (value "2450AT18B100E")
      (footprint "XDCR_2450AT18B100E")
      (description "2.4GHz - Chip RF Antenna 2.4GHz ~ 2.5GHz 0.5dBi Solder Surface Mount")
      (fields (field (name "MF") "Johanson Technology"))
      (libsource (lib "UNB Workspace") (part "2450AT18B100E"))
    )
    (comp (ref "J1")
      (value "691137710002")
      (footprint "691137710002")
      (description "Terminal Block, 5MM Pitch, Horizontal, Pressure Clamp Glow Wire, Pcb, 2PINS, Gr")
      (libsource (lib "Altium Content Vault") (part "TBL - 1R - 02P - Screw"))
    )
    (comp (ref "J2")
      (value "B5B-XH-AM(LF)(SN)")
      (footprint "FP-B5B-XH-AM_LF_SN-MFG")
      (description "CONN HEADER VERT 5POS 2.5MM")
      (libsource (lib "Altium Content Vault") (part "bf93c07fd2649a848d0ec8585582aab"))
    )
    (comp (ref "J3")
      (value "PPPC031LFBN-RC")
      (footprint "CONN_PPPC031LFBN-RC_SUL")
      (description "Description")
      (fields (field (name "COPYRIGHT") "Copyright (C) 2025 Ultra Librarian. All rights reserved."))
      (libsource (lib "PPPC031LFBN-RC") (part "PPPC031LFBN-RC"))
    )
    (comp (ref "J4")
      (value "PPPC021LFBN-RC")
      (footprint "CONN_PPPC021_SUL")
      (description "Description")
      (fields (field (name "COPYRIGHT") "Copyright (C) 2025 Ultra Librarian. All rights reserved."))
      (libsource (lib "") (part "PPPC021LFBN-RC_1"))
    )
    (comp (ref "J5")
      (value "PPPC021LFBN-RC")
      (footprint "CONN_PPPC021_SUL")
      (description "Description")
      (fields (field (name "COPYRIGHT") "Copyright (C) 2025 Ultra Librarian. All rights reserved."))
      (libsource (lib "") (part "PPPC021LFBN-RC_1"))
    )
    (comp (ref "J6")
      (value "PPPC021LFBN-RC")
      (footprint "CONN_PPPC021_SUL")
      (description "Description")
      (fields (field (name "COPYRIGHT") "Copyright (C) 2025 Ultra Librarian. All rights reserved."))
      (libsource (lib "PPPC021LFBN-RC") (part "PPPC021LFBN-RC"))
    )
    (comp (ref "J7")
      (value "PPPC021LFBN-RC")
      (footprint "CONN_PPPC021_SUL")
      (description "Description")
      (fields (field (name "COPYRIGHT") "Copyright (C) 2025 Ultra Librarian. All rights reserved."))
      (libsource (lib "") (part "PPPC021LFBN-RC_1"))
    )
    (comp (ref "J8")
      (value "PPPC021LFBN-RC")
      (footprint "CONN_PPPC021_SUL")
      (description "Description")
      (fields (field (name "COPYRIGHT") "Copyright (C) 2025 Ultra Librarian. All rights reserved."))
      (libsource (lib "") (part "PPPC021LFBN-RC_1"))
    )
    (comp (ref "J9")
      (value "PPPC021LFBN-RC")
      (footprint "CONN_PPPC021_SUL")
      (description "Description")
      (fields (field (name "COPYRIGHT") "Copyright (C) 2025 Ultra Librarian. All rights reserved."))
      (libsource (lib "PPPC021LFBN-RC") (part "PPPC021LFBN-RC"))
    )
    (comp (ref "J10")
      (value "PPPC021LFBN-RC")
      (footprint "CONN_PPPC021_SUL")
      (description "Description")
      (fields (field (name "COPYRIGHT") "Copyright (C) 2025 Ultra Librarian. All rights reserved."))
      (libsource (lib "") (part "PPPC021LFBN-RC_1"))
    )
    (comp (ref "J11")
      (value "PPPC021LFBN-RC")
      (footprint "CONN_PPPC021_SUL")
      (description "Description")
      (fields (field (name "COPYRIGHT") "Copyright (C) 2025 Ultra Librarian. All rights reserved."))
      (libsource (lib "") (part "PPPC021LFBN-RC_1"))
    )
    (comp (ref "J12")
      (value "PPTC041LFBN-RC")
      (footprint "SULLINS_PPTC041LFBN-RC")
      (description "4 Position Header Connector 0.100 (2.54mm) Through Hole Tin")
      (fields (field (name "MF") "Sullins Connector"))
      (libsource (lib "PPTC041LFBN-RC") (part "PPTC041LFBN-RC"))
    )
    (comp (ref "J13")
      (value "22-27-2061")
      (footprint "FP-22-27-2061-MFG")
      (description "CONN HEADER VERT 6POS 2.54MM")
      (libsource (lib "Altium Content Vault") (part "f2cb566baf1c37ab5a3b8e90bbeafd6"))
    )
    (comp (ref "J14")
      (value "22-27-2061")
      (footprint "FP-22-27-2061-MFG")
      (description "CONN HEADER VERT 6POS 2.54MM")
      (libsource (lib "Altium Content Vault") (part "f2cb566baf1c37ab5a3b8e90bbeafd6"))
    )
    (comp (ref "J15")
      (value "61300411121")
      (footprint "JST-S4B-XH-A(LF)(SN)_V")
      (fields (field (name "MANUFACTURER") "JST"))
      (libsource (lib "UNB Workspace") (part "CN-1P-M-R4"))
    )
    (comp (ref "J16")
      (value "22-27-2061")
      (footprint "FP-22-27-2061-MFG")
      (description "CONN HEADER VERT 6POS 2.54MM")
      (libsource (lib "Altium Content Vault") (part "f2cb566baf1c37ab5a3b8e90bbeafd6"))
    )
    (comp (ref "J17")
      (value "22-27-2061")
      (footprint "FP-22-27-2061-MFG")
      (description "CONN HEADER VERT 6POS 2.54MM")
      (libsource (lib "Altium Content Vault") (part "f2cb566baf1c37ab5a3b8e90bbeafd6"))
    )
    (comp (ref "J18")
      (value "PPPC021LFBN-RC")
      (footprint "CONN_PPPC021_SUL")
      (description "Description")
      (fields (field (name "COPYRIGHT") "Copyright (C) 2025 Ultra Librarian. All rights reserved."))
      (libsource (lib "PPPC021LFBN-RC") (part "PPPC021LFBN-RC"))
    )
    (comp (ref "J19")
      (value "PPPC031LFBN-RC")
      (footprint "CONN_PPPC031LFBN-RC_SUL")
      (description "Description")
      (fields (field (name "COPYRIGHT") "Copyright (C) 2025 Ultra Librarian. All rights reserved."))
      (libsource (lib "PPPC031LFBN-RC") (part "PPPC031LFBN-RC"))
    )
    (comp (ref "J20")
      (value "CONN_105450-0101")
      (footprint "CONN_1054500101_MOL")
      (fields
        (field (name "MANUFACTURER_PART_NUMBER") "1054500101")
        (field (name "COPYRIGHT") "Copyright (C) 2025 Ultra Librarian. All rights reserved.")
      )
      (libsource (lib "1054500101") (part "1054500101"))
    )
    (comp (ref "J21")
      (value "PPPC021LFBN-RC")
      (footprint "CONN_PPPC021_SUL")
      (description "Description")
      (fields (field (name "COPYRIGHT") "Copyright (C) 2025 Ultra Librarian. All rights reserved."))
      (libsource (lib "") (part "PPPC021LFBN-RC_1"))
    )
    (comp (ref "J22")
      (value "PPTC041LFBN-RC")
      (footprint "SULLINS_PPTC041LFBN-RC")
      (description "4 Position Header Connector 0.100 (2.54mm) Through Hole Tin")
      (fields (field (name "MF") "Sullins Connector"))
      (libsource (lib "") (part "PPTC041LFBN-RC_1"))
    )
    (comp (ref "J23")
      (value "PPPC031LFBN-RC")
      (footprint "CONN_PPPC031LFBN-RC_SUL")
      (description "Description")
      (fields (field (name "COPYRIGHT") "Copyright (C) 2025 Ultra Librarian. All rights reserved."))
      (libsource (lib "") (part "PPPC031LFBN-RC_1"))
    )
    (comp (ref "L1")
      (value "100 uF")
      (footprint "FP-CB3225-IPC_A")
      (description "SMD Inductors 100uH ±10% 0.34A 1.82Ω 1210")
      (fields (field (name "TOLERANCE") "10%"))
      (libsource (lib "Altium Content Vault") (part "725321dda6339637d4d059423bc1c3c"))
    )
    (comp (ref "L2")
      (value "10 uH")
      (footprint "FP-MLZ2012-1_25-MFG")
      (description "Shielded Multilayer Inductor 10uH ±20% 500mA 390mΩ SMD 0805")
      (fields (field (name "TOLERANCE") "20%"))
      (libsource (lib "Altium Content Vault") (part "725321dda6339637d4d059423bc1c3c"))
    )
    (comp (ref "L3")
      (value "15nH")
      (footprint "FP-LQW2BHN_03-MFG")
      (description "Wire Wound RF Inductor 15nH ±10% 1000mA 0.04Ω 0805 (2015)")
      (fields (field (name "TOLERANCE") "10%"))
      (libsource (lib "") (part "725321dda6339637d4d059423bc1c3c_1"))
    )
    (comp (ref "L4")
      (value "3.3nH")
      (footprint "FP-LQW2BHN_03-MFG")
      (description "Wire Wound RF Inductor 3.3nH ±0.5nH 1700mA 0.02Ω 0805 (2015)")
      (libsource (lib "") (part "725321dda6339637d4d059423bc1c3c_1"))
    )
    (comp (ref "L5")
      (value "2.7nH")
      (footprint "FP-LQW2BHN_03-MFG")
      (description "Wire Wound RF Inductor 2.7nH ±0.5nH 1900mA 0.02Ω 0805 (2015)")
      (libsource (lib "") (part "725321dda6339637d4d059423bc1c3c_1"))
    )
    (comp (ref "L6")
      (value "3.3 uH")
      (footprint "FP-IHLP-5050EZ-FP_3_226x4-MFG")
      (description "Commercial Inductors, High Saturation Series 3.3uH 15A 9.2mΩ 20%")
      (fields (field (name "TOLERANCE") "20%"))
      (libsource (lib "Altium Content Vault") (part "725321dda6339637d4d059423bc1c3c"))
    )
    (comp (ref "L7")
      (value "3.3nH")
      (footprint "FP-LQW2BHN_03-MFG")
      (description "Wire Wound RF Inductor 3.3nH ±0.5nH 1700mA 0.02Ω 0805 (2015)")
      (libsource (lib "") (part "725321dda6339637d4d059423bc1c3c_1"))
    )
    (comp (ref "NT1")
      (value "Net Tie 12x8mil")
      (footprint "SHORT06-FP")
      (libsource (lib "UNB Workspace") (part "CMP-00022-00002-2"))
    )
    (comp (ref "NT2")
      (value "Net Tie 12x8mil")
      (footprint "SHORT06-FP")
      (libsource (lib "UNB Workspace") (part "CMP-00022-00002-2"))
    )
    (comp (ref "Q1")
      (value "BCX56-16")
      (footprint "FP-SOT89-MFG")
      (description "TRANS NPN 150V 1A SOT89")
      (fields
        (field (name "MANUFACTURER PART NUMBER") "PBHV8115X,115")
        (field (name "MANUFACTURER") "Nexperia")
      )
      (libsource (lib "Altium Content Vault") (part "22d2bcc0fe72a7c4622b2c6aaace23d"))
    )
    (comp (ref "Q2")
      (value "CSD19532Q5B")
      (footprint "FP-DNK0008A-MFG")
      (description "MOSFET N-CH 100V 100A 8SON")
      (fields
        (field (name "OCTOPART") "https://octopart.com/csd19532q5b-texas+instruments-32890191")
        (field (name "MANUFACTURER") "Texas Instruments")
      )
      (libsource (lib "Altium Content Vault") (part "6fb2c024a3b9031f6d89538bc87a0fd"))
    )
    (comp (ref "Q3")
      (value "CSD19532Q5B")
      (footprint "FP-DNK0008A-MFG")
      (description "MOSFET N-CH 100V 100A 8SON")
      (fields
        (field (name "OCTOPART") "https://octopart.com/csd19532q5b-texas+instruments-32890191")
        (field (name "MANUFACTURER") "Texas Instruments")
      )
      (libsource (lib "Altium Content Vault") (part "6fb2c024a3b9031f6d89538bc87a0fd"))
    )
    (comp (ref "Q4")
      (value "2N7002KT1G")
      (footprint "SOT95P240X111-3N")
      (description "Mosfet Array 2 N-Channel (Dual) 60V 300mA 500mW Surface Mount PG-SOT363-6")
      (fields (field (name "MF") "onsemi") (field (name "MP") "2N7002"))
      (libsource (lib "2N7002") (part "2N7002"))
    )
    (comp (ref "Q5")
      (value "DMN10H220LQ-7")
      (footprint "FP-SOT23-MFG")
      (description "MOSFET N-CH 100V 1.6A SOT-23")
      (fields
        (field (name "MANUFACTURER PART NUMBER") "DMN10H220L-7")
        (field (name "MANUFACTURER") "Diodes Inc.")
      )
      (libsource (lib "Altium Content Vault") (part "3b9c635fedb024a5347a57b145af9cc"))
    )
    (comp (ref "Q6")
      (value "2N7002KW")
      (footprint "SC-70_419AB-01_OSI")
      (description "Description")
      (fields (field (name "COPYRIGHT") "Copyright (C) 2025 Ultra Librarian. All rights reserved."))
      (libsource (lib "2N7002KW") (part "2N7002KW"))
    )
    (comp (ref "Q7")
      (value "AO3419")
      (footprint "SOT95P237X112-3N")
      (description "P-Channel 20 V 3.7A (Ta) 1.3W (Ta) Surface Mount Micro3Ã¢â€žÂ¢ /SOT-23")
      (fields (field (name "MF") "Infineon") (field (name "MP") "IRLML6402TRPBF"))
      (libsource (lib "IRLML6402TRPBF") (part "IRLML6402TRPBF"))
    )
    (comp (ref "Q8")
      (value "2N7002KT1G")
      (footprint "SOT95P240X111-3N")
      (description "Mosfet Array 2 N-Channel (Dual) 60V 300mA 500mW Surface Mount PG-SOT363-6")
      (fields (field (name "MF") "onsemi") (field (name "MP") "2N7002"))
      (libsource (lib "2N7002") (part "2N7002"))
    )
    (comp (ref "Q9")
      (value "AO3419")
      (footprint "SOT95P237X112-3N")
      (description "P-Channel 20 V 3.7A (Ta) 1.3W (Ta) Surface Mount Micro3Ã¢â€žÂ¢ /SOT-23")
      (fields (field (name "MF") "Infineon") (field (name "MP") "IRLML6402TRPBF"))
      (libsource (lib "IRLML6402TRPBF") (part "IRLML6402TRPBF"))
    )
    (comp (ref "Q10")
      (value "SIR426DP-T1-GE3")
      (footprint "POWERPAK_SO-8_SINGLE")
      (description "N-CHANNEL 40-V (D-S) MOSFET")
      (fields (field (name "COPYRIGHT") "Copyright (C) 2025 Ultra Librarian. All rights reserved."))
      (libsource (lib "SIR426DP-T1-GE3") (part "SIR426DP-T1-GE3"))
    )
    (comp (ref "Q11")
      (value "SIR426DP-T1-GE3")
      (footprint "POWERPAK_SO-8_SINGLE")
      (description "N-CHANNEL 40-V (D-S) MOSFET")
      (fields (field (name "COPYRIGHT") "Copyright (C) 2025 Ultra Librarian. All rights reserved."))
      (libsource (lib "SIR426DP-T1-GE3") (part "SIR426DP-T1-GE3"))
    )
    (comp (ref "Q12")
      (value "STL9P3LLH6")
      (footprint "POWERFLAT_3P3X3P3_STM")
      (description "P-channel -30 V, 12 mOhm typ., -9 A STripFET H6 Power MOSFET in a PowerFLAT 3.3 x 3.3 package")
      (fields (field (name "COPYRIGHT") "Copyright (C) 2025 Ultra Librarian. All rights reserved."))
      (libsource (lib "STL9P3LLH6") (part "STL9P3LLH6"))
    )
    (comp (ref "R1")
      (value "100")
      (footprint "RESC2013X70X40ML20T20")
      (fields (field (name "PART NUMBER") "ERJ-6GEYJ101V") (field (name "MANUFACTURER") "Panasonic"))
      (libsource (lib "Altium Content Vault") (part "RES"))
    )
    (comp (ref "R2")
      (value "1.0 k")
      (footprint "RESC2013X70X40ML20T20")
      (fields (field (name "MANUFACTURER") "Panasonic") (field (name "PART NUMBER") "ERJ-6GEYJ102V"))
      (libsource (lib "Altium Content Vault") (part "RES"))
    )
    (comp (ref "R3")
      (value "150")
      (footprint "FP-CRCW2512-e3-IPC_B")
      (description "RES Thick Film, 150Ω, 5%, 1W, 200ppm/°C, 2512")
      (fields (field (name "TOLERANCE") "5%"))
      (libsource (lib "Altium Content Vault") (part "1029c3af85768c4190bb7ad29bc67b5"))
    )
    (comp (ref "R4")
      (value "20.0")
      (footprint "RESC3216X60X45ML10T20")
      (fields (field (name "MANUFACTURER") "Vishay Dale") (field (name "PART NUMBER") "CRCW120620R0FKEA"))
      (libsource (lib "Altium Content Vault") (part "RES"))
    )
    (comp (ref "R5")
      (value "20.0")
      (footprint "RESC3216X60X45ML10T20")
      (fields (field (name "MANUFACTURER") "Vishay Dale") (field (name "PART NUMBER") "CRCW120620R0FKEA"))
      (libsource (lib "Altium Content Vault") (part "RES"))
    )
    (comp (ref "R6")
      (value "20.0")
      (footprint "RESC3216X60X45ML10T20")
      (fields (field (name "MANUFACTURER") "Vishay Dale") (field (name "PART NUMBER") "CRCW120620R0FKEA"))
      (libsource (lib "Altium Content Vault") (part "RES"))
    )
    (comp (ref "R7")
      (value "1.0 k")
      (footprint "RESC2013X70X40ML20T20")
      (fields (field (name "MANUFACTURER") "Panasonic") (field (name "PART NUMBER") "ERJ-6GEYJ102V"))
      (libsource (lib "Altium Content Vault") (part "RES"))
    )
    (comp (ref "R8")
      (value "20.0")
      (footprint "RESC3216X60X45ML10T20")
      (fields (field (name "MANUFACTURER") "Vishay Dale") (field (name "PART NUMBER") "CRCW120620R0FKEA"))
      (libsource (lib "Altium Content Vault") (part "RES"))
    )
    (comp (ref "R9")
      (value "1k")
      (footprint "FP-RMCF0805-MFG")
      (description "1kΩ ±1% 0.125W 0805 Thick Film Chip Resistor AEC-Q200 compliant")
      (fields (field (name "TOLERANCE") "1%"))
      (libsource (lib "Altium Content Vault") (part "1029c3af85768c4190bb7ad29bc67b5"))
    )
    (comp (ref "R10")
      (value "1k")
      (footprint "FP-RMCF0805-MFG")
      (description "1kΩ ±1% 0.125W 0805 Thick Film Chip Resistor AEC-Q200 compliant")
      (fields (field (name "TOLERANCE") "1%"))
      (libsource (lib "Altium Content Vault") (part "1029c3af85768c4190bb7ad29bc67b5"))
    )
    (comp (ref "R11")
      (value "20.0")
      (footprint "RESC3216X60X45ML10T20")
      (fields (field (name "MANUFACTURER") "Vishay Dale") (field (name "PART NUMBER") "CRCW120620R0FKEA"))
      (libsource (lib "Altium Content Vault") (part "RES"))
    )
    (comp (ref "R12")
      (value "1.0 k")
      (footprint "RESC2013X70X40ML20T20")
      (fields (field (name "MANUFACTURER") "Panasonic") (field (name "PART NUMBER") "ERJ-6GEYJ102V"))
      (libsource (lib "Altium Content Vault") (part "RES"))
    )
    (comp (ref "R13")
      (value "3.9 k")
      (footprint "Vishay_CRCW1206-e3_MFG")
      (fields (field (name "TOLERANCE") "5%"))
      (libsource (lib "Altium Content Vault") (part "CRCW12063K90JNEA"))
    )
    (comp (ref "R14")
      (value "100")
      (footprint "RESC2013X70X40ML20T20")
      (fields (field (name "PART NUMBER") "ERJ-6GEYJ101V") (field (name "MANUFACTURER") "Panasonic"))
      (libsource (lib "Altium Content Vault") (part "RES"))
    )
    (comp (ref "R15")
      (value "100")
      (footprint "RESC2013X70X40ML20T20")
      (fields (field (name "PART NUMBER") "ERJ-6GEYJ101V") (field (name "MANUFACTURER") "Panasonic"))
      (libsource (lib "Altium Content Vault") (part "RES"))
    )
    (comp (ref "R16")
      (value "0")
      (footprint "FP-RMCF0805-MFG")
      (description "RES 0 OHM JUMPER 1/8W 0805")
      (libsource (lib "Altium Content Vault") (part "1029c3af85768c4190bb7ad29bc67b5"))
    )
    (comp (ref "R17")
      (value "1 mOhms")
      (footprint "RES_R2512_ROM")
      (description "No Description Available")
      (fields
        (field (name "MANUFACTURER_PART_NUMBER") "PMR100HZPFV1L00")
        (field (name "COPYRIGHT") "Copyright (C) 2026 Ultra Librarian. All rights reserved.")
      )
      (libsource (lib "PMR100HZPFV1L00") (part "PMR100HZPFV1L00"))
    )
    (comp (ref "R18")
      (value "3.9 k")
      (footprint "Vishay_CRCW1206-e3_MFG")
      (fields (field (name "TOLERANCE") "5%"))
      (libsource (lib "Altium Content Vault") (part "CRCW12063K90JNEA"))
    )
    (comp (ref "R19")
      (value "100 k")
      (footprint "RESC5025X65N")
      (fields (field (name "MF") "Yageo Corporation") (field (name "MP") "RC2010FK07100KL"))
      (libsource (lib "RC2010FK-07100KL") (part "RC2010FK-07100KL"))
    )
    (comp (ref "R20")
      (value "470")
      (footprint "FP-CRGCQ0805-IPC_C")
      (description "CRGCQ0805 470Ω 0.125W ±100ppm/°C 5% 150V")
      (fields (field (name "TOLERANCE") "0.05") (field (name "MANUFACTURER") "TE Connectivity"))
      (libsource (lib "Altium Content Vault") (part "1029c3af85768c4190bb7ad29bc67b5"))
    )
    (comp (ref "R21")
      (value "5.1 k")
      (footprint "FP-CRCW1206-e3-IPC_A")
      (description "RES Thick Film, 5.1kΩ, 5%, 0.25W, 200ppm/°C, 1206")
      (fields (field (name "TOLERANCE") "5%"))
      (libsource (lib "Altium Content Vault") (part "1029c3af85768c4190bb7ad29bc67b5"))
    )
    (comp (ref "R22")
      (value "10 k")
      (footprint "RESC5025X65N")
      (fields (field (name "MP") "RC2010JK-0710KL"))
      (libsource (lib "RC2010JK-0710KL") (part "RC2010JK-0710KL"))
    )
    (comp (ref "R23")
      (value "20 k")
      (footprint "RESC2013X70X40NL20T20")
      (fields (field (name "MANUFACTURER") "Panasonic") (field (name "PART NUMBER") "ERJ-6GEYJ203V"))
      (libsource (lib "Altium Content Vault") (part "RES"))
    )
    (comp (ref "R24")
      (value "10M")
      (footprint "FP-RMCF0805-IPC_A")
      (description "10MΩ ±5% 0.125W 0805 Thick Film Chip Resistor AEC-Q200 compliant")
      (fields (field (name "TOLERANCE") "5%"))
      (libsource (lib "Altium Content Vault") (part "1029c3af85768c4190bb7ad29bc67b5"))
    )
    (comp (ref "R25")
      (value "10M")
      (footprint "FP-RMCF0805-IPC_A")
      (description "10MΩ ±5% 0.125W 0805 Thick Film Chip Resistor AEC-Q200 compliant")
      (fields (field (name "TOLERANCE") "5%"))
      (libsource (lib "Altium Content Vault") (part "1029c3af85768c4190bb7ad29bc67b5"))
    )
    (comp (ref "R26")
      (value "10M")
      (footprint "FP-RMCF0805-IPC_A")
      (description "10MΩ ±5% 0.125W 0805 Thick Film Chip Resistor AEC-Q200 compliant")
      (fields (field (name "TOLERANCE") "5%"))
      (libsource (lib "Altium Content Vault") (part "1029c3af85768c4190bb7ad29bc67b5"))
    )
    (comp (ref "R27")
      (value "0")
      (footprint "RESC2013X65X40LL15T20")
      (description "Chip Resistor, 0 Ohm, 0.125 W, -55 to 125 degC, 0805 (2012 Metric), RoHS, Tape and Reel")
      (fields (field (name "TOLERANCE") "0%") (field (name "MANUFACTURER") "TE Connectivity"))
      (libsource (lib "Altium Content Vault") (part "RES-2"))
    )
    (comp (ref "R28")
      (value "470")
      (footprint "FP-CRGCQ0805-IPC_C")
      (description "CRGCQ0805 470Ω 0.125W ±100ppm/°C 5% 150V")
      (fields (field (name "TOLERANCE") "0.05") (field (name "MANUFACTURER") "TE Connectivity"))
      (libsource (lib "Altium Content Vault") (part "1029c3af85768c4190bb7ad29bc67b5"))
    )
    (comp (ref "R29")
      (value "10 k")
      (footprint "RESC2013X70X40LL20T20")
      (fields (field (name "PART NUMBER") "ERJ-6GEYJ103V") (field (name "MANUFACTURER") "Panasonic"))
      (libsource (lib "Altium Content Vault") (part "RES"))
    )
    (comp (ref "R30")
      (value "0")
      (footprint "FP-RMCF0805-MFG")
      (description "RES 0 OHM JUMPER 1/8W 0805")
      (libsource (lib "Altium Content Vault") (part "1029c3af85768c4190bb7ad29bc67b5"))
    )
    (comp (ref "R31")
      (value "5.1 k")
      (footprint "FP-CRCW1206-e3-IPC_A")
      (description "RES Thick Film, 5.1kΩ, 5%, 0.25W, 200ppm/°C, 1206")
      (fields (field (name "TOLERANCE") "5%"))
      (libsource (lib "Altium Content Vault") (part "1029c3af85768c4190bb7ad29bc67b5"))
    )
    (comp (ref "R32")
      (value "5.1 k")
      (footprint "FP-CRCW1206-e3-IPC_A")
      (description "RES Thick Film, 5.1kΩ, 5%, 0.25W, 200ppm/°C, 1206")
      (fields (field (name "TOLERANCE") "5%"))
      (libsource (lib "Altium Content Vault") (part "1029c3af85768c4190bb7ad29bc67b5"))
    )
    (comp (ref "R33")
      (value "7.5 k")
      (footprint "RESC2013X70X40LL20T20")
      (fields (field (name "PART NUMBER") "ERJ-6GEYJ752V") (field (name "MANUFACTURER") "Panasonic"))
      (libsource (lib "Altium Content Vault") (part "RES"))
    )
    (comp (ref "R34")
      (value "10 k")
      (footprint "RESC5025X65N")
      (fields (field (name "MP") "RC2010JK-0710KL"))
      (libsource (lib "RC2010JK-0710KL") (part "RC2010JK-0710KL"))
    )
    (comp (ref "R35")
      (value "5.1 k")
      (footprint "FP-CRCW1206-e3-IPC_A")
      (description "RES Thick Film, 5.1kΩ, 5%, 0.25W, 200ppm/°C, 1206")
      (fields (field (name "TOLERANCE") "5%"))
      (libsource (lib "Altium Content Vault") (part "1029c3af85768c4190bb7ad29bc67b5"))
    )
    (comp (ref "R36")
      (value "5.1 k")
      (footprint "FP-CRCW1206-e3-IPC_A")
      (description "RES Thick Film, 5.1kΩ, 5%, 0.25W, 200ppm/°C, 1206")
      (fields (field (name "TOLERANCE") "5%"))
      (libsource (lib "Altium Content Vault") (part "1029c3af85768c4190bb7ad29bc67b5"))
    )
    (comp (ref "R37")
      (value "5.1 k")
      (footprint "FP-CRCW1206-e3-IPC_A")
      (description "RES Thick Film, 5.1kΩ, 5%, 0.25W, 200ppm/°C, 1206")
      (fields (field (name "TOLERANCE") "5%"))
      (libsource (lib "Altium Content Vault") (part "1029c3af85768c4190bb7ad29bc67b5"))
    )
    (comp (ref "R38")
      (value "5.1 k")
      (footprint "FP-CRCW1206-e3-IPC_A")
      (description "RES Thick Film, 5.1kΩ, 5%, 0.25W, 200ppm/°C, 1206")
      (fields (field (name "TOLERANCE") "5%"))
      (libsource (lib "Altium Content Vault") (part "1029c3af85768c4190bb7ad29bc67b5"))
    )
    (comp (ref "R39")
      (value "5.1 k")
      (footprint "FP-CRCW1206-e3-IPC_A")
      (description "RES Thick Film, 5.1kΩ, 5%, 0.25W, 200ppm/°C, 1206")
      (fields (field (name "TOLERANCE") "5%"))
      (libsource (lib "Altium Content Vault") (part "1029c3af85768c4190bb7ad29bc67b5"))
    )
    (comp (ref "R40")
      (value "10k")
      (footprint "FP-AT0805-MFG")
      (description "Thin Film Chip Resistors Automotive Grade 10kΩ 0.5% 50ppm/°C 0805")
      (fields (field (name "TOLERANCE") "0.5%"))
      (libsource (lib "") (part "1029c3af85768c4190bb7ad29bc67b5_1"))
    )
    (comp (ref "R41")
      (value "10k")
      (footprint "FP-AT0805-MFG")
      (description "Thin Film Chip Resistors Automotive Grade 10kΩ 0.5% 50ppm/°C 0805")
      (fields (field (name "TOLERANCE") "0.5%"))
      (libsource (lib "") (part "1029c3af85768c4190bb7ad29bc67b5_1"))
    )
    (comp (ref "R42")
      (value "1k")
      (footprint "FP-RMCF0805-MFG")
      (description "1kΩ ±1% 0.125W 0805 Thick Film Chip Resistor AEC-Q200 compliant")
      (fields (field (name "TOLERANCE") "1%"))
      (libsource (lib "Altium Content Vault") (part "1029c3af85768c4190bb7ad29bc67b5"))
    )
    (comp (ref "R43")
      (value "0")
      (footprint "RESC2013X65X40LL15T20")
      (description "Chip Resistor, 0 Ohm, 0.125 W, -55 to 125 degC, 0805 (2012 Metric), RoHS, Tape and Reel")
      (fields (field (name "TOLERANCE") "0%") (field (name "MANUFACTURER") "TE Connectivity"))
      (libsource (lib "Altium Content Vault") (part "RES-2"))
    )
    (comp (ref "R44")
      (value "10 k")
      (footprint "RESC2013X70X40LL20T20")
      (fields (field (name "PART NUMBER") "ERJ-6GEYJ103V") (field (name "MANUFACTURER") "Panasonic"))
      (libsource (lib "Altium Content Vault") (part "RES"))
    )
    (comp (ref "R45")
      (value "22k")
      (footprint "FP-MCU0805-IPC_C")
      (description "RES 1.05K OHM 0.5% 1/5W 0805")
      (fields (field (name "TOLERANCE") "1%"))
      (libsource (lib "") (part "1029c3af85768c4190bb7ad29bc67b5_1"))
    )
    (comp (ref "R46")
      (value "10")
      (footprint "FP-RT0805-MFG")
      (description "RT0805 10Ω 0.125W 10 ppm/°C 0.25%")
      (fields (field (name "MANUFACTURER") "Yageo") (field (name "TOLERANCE") "0.0025"))
      (libsource (lib "") (part "1029c3af85768c4190bb7ad29bc67b5_1"))
    )
    (comp (ref "R47")
      (value "10 k")
      (footprint "RESC2013X70X40LL20T20")
      (fields (field (name "PART NUMBER") "ERJ-6GEYJ103V") (field (name "MANUFACTURER") "Panasonic"))
      (libsource (lib "Altium Content Vault") (part "RES"))
    )
    (comp (ref "R48")
      (value "10")
      (footprint "FP-RT0805-MFG")
      (description "RT0805 10Ω 0.125W 10 ppm/°C 0.25%")
      (fields (field (name "MANUFACTURER") "Yageo") (field (name "TOLERANCE") "0.0025"))
      (libsource (lib "") (part "1029c3af85768c4190bb7ad29bc67b5_1"))
    )
    (comp (ref "R49")
      (value "0")
      (footprint "RESC2013X65X40LL15T20")
      (description "Chip Resistor, 0 Ohm, 0.125 W, -55 to 125 degC, 0805 (2012 Metric), RoHS, Tape and Reel")
      (fields (field (name "TOLERANCE") "0%") (field (name "MANUFACTURER") "TE Connectivity"))
      (libsource (lib "Altium Content Vault") (part "RES-2"))
    )
    (comp (ref "R50")
      (value "0")
      (footprint "RESC2013X65X40LL15T20")
      (description "Chip Resistor, 0 Ohm, 0.125 W, -55 to 125 degC, 0805 (2012 Metric), RoHS, Tape and Reel")
      (fields (field (name "TOLERANCE") "0%") (field (name "MANUFACTURER") "TE Connectivity"))
      (libsource (lib "Altium Content Vault") (part "RES-2"))
    )
    (comp (ref "R51")
      (value "10k")
      (footprint "RESC0805(2012)_L")
      (description "10K 0.125W 5% 0805 (2012 Metric)  SMD")
      (fields (field (name "POWER") "0.125 W") (field (name "TOLERANCE") "5 %"))
      (libsource (lib "Altium Content Vault") (part "RES"))
    )
    (comp (ref "R52")
      (value "0")
      (footprint "RESC2013X65X40LL15T20")
      (description "Chip Resistor, 0 Ohm, 0.125 W, -55 to 125 degC, 0805 (2012 Metric), RoHS, Tape and Reel")
      (fields (field (name "TOLERANCE") "0%") (field (name "MANUFACTURER") "TE Connectivity"))
      (libsource (lib "Altium Content Vault") (part "RES-2"))
    )
    (comp (ref "R53")
      (value "0 NC")
      (footprint "RESC2013X65X40LL15T20")
      (description "Chip Resistor, 0 Ohm, 0.125 W, -55 to 125 degC, 0805 (2012 Metric), RoHS, Tape and Reel")
      (fields (field (name "TOLERANCE") "0%") (field (name "MANUFACTURER") "TE Connectivity"))
      (libsource (lib "Altium Content Vault") (part "RES-2"))
    )
    (comp (ref "R54")
      (value "10 k")
      (footprint "RESC2013X70X40LL20T20")
      (fields (field (name "PART NUMBER") "ERJ-6GEYJ103V") (field (name "MANUFACTURER") "Panasonic"))
      (libsource (lib "Altium Content Vault") (part "RES"))
    )
    (comp (ref "R55")
      (value "1M")
      (footprint "FP-MCU0805-IPC_B")
      (description "RES 1.05K OHM 0.5% 1/5W 0805")
      (fields (field (name "TOLERANCE") "0.1%"))
      (libsource (lib "") (part "1029c3af85768c4190bb7ad29bc67b5_1"))
    )
    (comp (ref "R56")
      (value "10 k")
      (footprint "RESC5025X65N")
      (fields (field (name "MP") "RC2010JK-0710KL"))
      (libsource (lib "RC2010JK-0710KL") (part "RC2010JK-0710KL"))
    )
    (comp (ref "R57")
      (value "0")
      (footprint "RESC2013X65X40LL15T20")
      (description "Chip Resistor, 0 Ohm, 0.125 W, -55 to 125 degC, 0805 (2012 Metric), RoHS, Tape and Reel")
      (fields (field (name "TOLERANCE") "0%") (field (name "MANUFACTURER") "TE Connectivity"))
      (libsource (lib "Altium Content Vault") (part "RES-2"))
    )
    (comp (ref "R58")
      (value "2")
      (footprint "RES_RMCF2010_STP")
      (description "No Description Available")
      (fields
        (field (name "MANUFACTURER_PART_NUMBER") "RMCF2010FT2R00")
        (field (name "COPYRIGHT") "Copyright (C) 2026 Ultra Librarian. All rights reserved.")
      )
      (libsource (lib "RMCF2010FT2R00") (part "RMCF2010FT2R00"))
    )
    (comp (ref "R59")
      (value "10Ω")
      (footprint "RESC2013X60X35NL10T20")
      (fields (field (name "MANUFACTURER") "Yageo") (field (name "PART NUMBER") "RC0805JR-1310RL"))
      (libsource (lib "Altium Content Vault") (part "RES"))
    )
    (comp (ref "R60")
      (value "9.1 k")
      (footprint "RESC5025X65N:RESC5025X65N")
      (description "RES SMD 9.1K OHM 5% 3/4W 2010")
      (fields (field (name "MP") "RC2010JK-079K1L"))
      (libsource (lib "RC2010JK-079K1L") (part "RC2010JK-079K1L"))
    )
    (comp (ref "R61")
      (value "100 k")
      (footprint "RESC5025X65N")
      (fields (field (name "MF") "Yageo Corporation") (field (name "MP") "RC2010FK07100KL"))
      (libsource (lib "RC2010FK-07100KL") (part "RC2010FK-07100KL"))
    )
    (comp (ref "R62")
      (value "100kΩ")
      (footprint "FP-CRCW0805-e3-MFG")
      (description "RES Thick Film, 100kΩ, 1%, 0.125W, 100ppm/°C, 0805")
      (fields (field (name "TOLERANCE") "1%"))
      (libsource (lib "") (part "1029c3af85768c4190bb7ad29bc67b5_1"))
    )
    (comp (ref "R63")
      (value "0.001")
      (footprint "FP-WSL2010-1_47-MFG")
      (fields (field (name "TOLERANCE") "1%"))
      (libsource (lib "Altium Content Vault") (part "1029c3af85768c4190bb7ad29bc67b5"))
    )
    (comp (ref "R64")
      (value "140 k")
      (footprint "RES_RMCF2010_STP")
      (fields (field (name "MANUFACTURER PART NUMBER") "RMCF2010FT140K"))
      (libsource (lib "*") (part "RMCF2010FT140K"))
    )
    (comp (ref "R65")
      (value "100")
      (footprint "RESC3126X65N")
      (description "100 Ohms Â±5% 0.5W, 1/2W Chip Resistor 1210 (3225 Metric) Moisture Resistant Thick Film")
      (fields (field (name "MF") "Yageo") (field (name "MP") "RC1210JR-07100RL"))
      (libsource (lib "RC1210JR-07100RL") (part "RC1210JR-07100RL"))
    )
    (comp (ref "R66")
      (value "10 k")
      (footprint "RESC2013X70X40LL20T20")
      (fields (field (name "PART NUMBER") "ERJ-6GEYJ103V") (field (name "MANUFACTURER") "Panasonic"))
      (libsource (lib "Altium Content Vault") (part "RES"))
    )
    (comp (ref "R67")
      (value "100kΩ")
      (footprint "FP-CRCW0805-e3-MFG")
      (description "RES Thick Film, 100kΩ, 1%, 0.125W, 100ppm/°C, 0805")
      (fields (field (name "TOLERANCE") "1%"))
      (libsource (lib "Altium Content Vault") (part "1029c3af85768c4190bb7ad29bc67b5"))
    )
    (comp (ref "R68")
      (value "261 k")
      (footprint "FP-CRCW2512-e3-IPC_B")
      (description "RES Thick Film, 261kΩ, 1%, 1W, 100ppm/°C, 2512")
      (fields (field (name "TOLERANCE") "1%"))
      (libsource (lib "Altium Content Vault") (part "1029c3af85768c4190bb7ad29bc67b5"))
    )
    (comp (ref "R69")
      (value "560 k")
      (footprint "RESC5025X65N")
      (fields (field (name "MANUFACTURER PART NUMBER") "RC2010FK-07560KL"))
      (libsource (lib "*") (part "RC2010FK-07560KL"))
    )
    (comp (ref "R70")
      (value "10 k")
      (footprint "RESC2013X70X40LL20T20")
      (fields (field (name "PART NUMBER") "ERJ-6GEYJ103V") (field (name "MANUFACTURER") "Panasonic"))
      (libsource (lib "Altium Content Vault") (part "RES"))
    )
    (comp (ref "R71")
      (value "10Ω")
      (footprint "RESC2013X60X35NL10T20")
      (fields (field (name "MANUFACTURER") "Yageo") (field (name "PART NUMBER") "RC0805JR-1310RL"))
      (libsource (lib "Altium Content Vault") (part "RES"))
    )
    (comp (ref "R72")
      (value "820Ω")
      (footprint "FP-AC0805-MFG")
      (description "RES SMD 820 OHM 1% 1/8W 0805")
      (fields
        (field (name "TOLERANCE") "0.01")
        (field (name "OCTOPART") "https://octopart.com/ac0805fr-07820rl-yageo-26041182")
      )
      (libsource (lib "Altium Content Vault") (part "1029c3af85768c4190bb7ad29bc67b5"))
    )
    (comp (ref "R73")
      (value "10Ω")
      (footprint "RESC2013X60X35NL10T20")
      (fields (field (name "MANUFACTURER") "Yageo") (field (name "PART NUMBER") "RC0805JR-1310RL"))
      (libsource (lib "Altium Content Vault") (part "RES"))
    )
    (comp (ref "R74")
      (value "10Ω")
      (footprint "RESC2013X60X35NL10T20")
      (fields (field (name "MANUFACTURER") "Yageo") (field (name "PART NUMBER") "RC0805JR-1310RL"))
      (libsource (lib "Altium Content Vault") (part "RES"))
    )
    (comp (ref "R75")
      (value "10Ω")
      (footprint "RESC2013X60X35NL10T20")
      (fields (field (name "MANUFACTURER") "Yageo") (field (name "PART NUMBER") "RC0805JR-1310RL"))
      (libsource (lib "Altium Content Vault") (part "RES"))
    )
    (comp (ref "R76")
      (value "0Ω")
      (footprint "FP-RCC0805-e3-MFG")
      (description "RCC08050000Z0EA Res Thick Film 0805 0 Ohm Conformal Coated Pad SMD Automotive AEC-Q200 T/R")
      (libsource (lib "Altium Content Vault") (part "1029c3af85768c4190bb7ad29bc67b5"))
    )
    (comp (ref "R77")
      (value "10Ω")
      (footprint "RESC2013X60X35NL10T20")
      (fields (field (name "MANUFACTURER") "Yageo") (field (name "PART NUMBER") "RC0805JR-1310RL"))
      (libsource (lib "Altium Content Vault") (part "RES"))
    )
    (comp (ref "R78")
      (value "100 k")
      (footprint "RESC5025X65N")
      (fields (field (name "MANUFACTURER PART NUMBER") "RC2010FK-07100KL"))
      (libsource (lib "*") (part "RC2010FK-07100KL"))
    )
    (comp (ref "R80")
      (value "442Ω")
      (footprint "FP-RN73R2A-IPC_C")
      (description "442Ω ±0.1% 0.125W, 1/8W Chip Resistor 0805 (2012 Metric) Moisture Resistant Thin Film")
      (libsource (lib "") (part "1029c3af85768c4190bb7ad29bc67b5_1"))
    )
    (comp (ref "R82")
      (value "0Ω")
      (footprint "FP-RCC0805-e3-MFG")
      (description "RCC08050000Z0EA Res Thick Film 0805 0 Ohm Conformal Coated Pad SMD Automotive AEC-Q200 T/R")
      (libsource (lib "Altium Content Vault") (part "1029c3af85768c4190bb7ad29bc67b5"))
    )
    (comp (ref "R83")
      (value "100 k")
      (footprint "RESC5025X65N")
      (fields (field (name "MANUFACTURER PART NUMBER") "RC2010FK-07100KL"))
      (libsource (lib "*") (part "RC2010FK-07100KL"))
    )
    (comp (ref "R84")
      (value "470")
      (footprint "FP-CRGCQ0805-IPC_C")
      (description "CRGCQ0805 470Ω 0.125W ±100ppm/°C 5% 150V")
      (fields (field (name "TOLERANCE") "0.05") (field (name "MANUFACTURER") "TE Connectivity"))
      (libsource (lib "Altium Content Vault") (part "1029c3af85768c4190bb7ad29bc67b5"))
    )
    (comp (ref "R85")
      (value "100")
      (footprint "RESC3126X65N")
      (description "100 Ohms Â±5% 0.5W, 1/2W Chip Resistor 1210 (3225 Metric) Moisture Resistant Thick Film")
      (fields (field (name "MF") "Yageo") (field (name "MP") "RC1210JR-07100RL"))
      (libsource (lib "RC1210JR-07100RL") (part "RC1210JR-07100RL"))
    )
    (comp (ref "R86")
      (value "1 k")
      (footprint "RESC5025X65N")
      (fields (field (name "MANUFACTURER PART NUMBER") "RC2010FK-071KL"))
      (libsource (lib "*") (part "RC2010FK-071KL"))
    )
    (comp (ref "R87")
      (value "22 k")
      (footprint "RESC5025X65N")
      (fields (field (name "MP") "RC2010FK-0722KL"))
      (libsource (lib "RC2010FK-0722KL") (part "RC2010FK-0722KL"))
    )
    (comp (ref "R88")
      (value "1k")
      (footprint "FP-RMCF0805-MFG")
      (description "1kΩ ±1% 0.125W 0805 Thick Film Chip Resistor AEC-Q200 compliant")
      (fields (field (name "TOLERANCE") "1%"))
      (libsource (lib "Altium Content Vault") (part "1029c3af85768c4190bb7ad29bc67b5"))
    )
    (comp (ref "R90")
      (value "100 k")
      (footprint "RESC5025X65N")
      (fields (field (name "MANUFACTURER PART NUMBER") "RC2010FK-07100KL"))
      (libsource (lib "*") (part "RC2010FK-07100KL"))
    )
    (comp (ref "R91")
      (value "100 k")
      (footprint "RESC5025X65N")
      (fields (field (name "MANUFACTURER PART NUMBER") "RC2010FK-07100KL"))
      (libsource (lib "*") (part "RC2010FK-07100KL"))
    )
    (comp (ref "RT1")
      (value "103AT-2")
      (footprint "FP-103AT-2-MFG")
      (description "Thermistor NTC 10KOhm 1% 2-Pin")
      (fields (field (name "TOLERANCE") "1%"))
      (libsource (lib "Altium Content Vault") (part "3b148a6ebabc5fb4d708a66c052d352"))
    )
    (comp (ref "RT2")
      (value "103AT-2")
      (footprint "FP-103AT-2-MFG")
      (description "Thermistor NTC 10KOhm 1% 2-Pin")
      (fields (field (name "TOLERANCE") "1%"))
      (libsource (lib "Altium Content Vault") (part "3b148a6ebabc5fb4d708a66c052d352"))
    )
    (comp (ref "RT3")
      (value "10 k")
      (footprint "FP-NCP15-NCU15-0_05-IPC_A")
      (description "NTC Thermistor for Temperature Sensor, Automotive, 0402, 10kΩ, 1%, 0.1mA, 5V")
      (libsource (lib "Altium Content Vault") (part "3b148a6ebabc5fb4d708a66c052d352"))
    )
    (comp (ref "S1")
      (value "EVQ-P7A01P")
      (footprint "FP-EVQ-P7A01P-MFG")
      (description "SWITCH TACTILE SPST-NO 0.05A 12V")
      (fields
        (field (name "OCTOPART") "https://octopart.com/evq-p7a01p-panasonic-29917075")
        (field (name "MANUFACTURER") "Panasonic")
      )
      (libsource (lib "Altium Content Vault") (part "c93661f14280f1e5a1fd29b4a471f7d"))
    )
    (comp (ref "S2")
      (value "L101011ML04Q")
      (footprint "SW_L101011ML04Q")
      (description "Switch Slide ON OFF SPST Side Slide 4A 250VAC 125VDC PC Pins Thru-Hole Bulk")
      (fields (field (name "MF") "C&K"))
      (libsource (lib "L101011ML04Q") (part "L101011ML04Q"))
    )
    (comp (ref "U1")
      (value "BQ76942PFBR")
      (footprint "FP-PFB0048A-IPC_C")
      (description "3-SERIES TO 10-SERIES MULTICELL")
      (libsource (lib "Altium Content Vault") (part "9d4dc2406375bad60342955c0997ed6"))
    )
    (comp (ref "U2")
      (value "TPS62177DQCR")
      (footprint "DQC0010A")
      (description "28V, 0.5A Step-Down Converter with SNOOZE Mode 10-WSON -40 to 85")
      (fields (field (name "COPYRIGHT") "Copyright (C) 2026 Ultra Librarian. All rights reserved."))
      (libsource (lib "TPS62177DQCR") (part "TPS62177DQCR"))
    )
    (comp (ref "U3")
      (value "MCP1804T-A002I/OT")
      (footprint "SOT-23-OT5_N")
      (description "150 mA, 28V LDO Regulator With Shutdown, 5-Pin SOT-23, Industrial Temperature, Tape and Reel")
      (libsource (lib "Altium Content Vault") (part "PM-LINEREG-MCP1804T-SOT23-5"))
    )
    (comp (ref "U4")
      (value "NRF52832-QFAA-R7")
      (footprint "QFN48_6X6_QF_NOR")
      (description "Description")
      (fields (field (name "COPYRIGHT") "Copyright (C) 2025 Ultra Librarian. All rights reserved."))
      (libsource (lib "NRF52832-QFAA-R7") (part "NRF52832-QFAA-R7"))
    )
    (comp (ref "U5")
      (value "PIC32MX274F256B-I/SO")
      (footprint "FP-C04-052-MFG")
      (description "PIC32MX274F256BT-I/SO MCU 32-bit MIPS32 M4K RISC 256KB Flash 2.5V/3.3V 28-Pin SOIC W T/R")
      (libsource (lib "Altium Content Vault") (part "cc761d43bf30e6de3bae40b41436225"))
    )
    (comp (ref "U6")
      (value "BQ24600_RVA_16")
      (footprint "RVA16_2P14X2P14")
      (description "Standalone 1-6 cell Buck battery charge controller 16-VQFN -40 to 85")
      (fields
        (field (name "MANUFACTURER_PART_NUMBER") "BQ24600RVAR")
        (field (name "COPYRIGHT") "Copyright (C) 2025 Ultra Librarian. All rights reserved.")
      )
      (libsource (lib "*") (part "BQ24600RVAR"))
    )
    (comp (ref "U7")
      (value "MCP3562RT-E/ST")
      (footprint "TSSOP20_ST_MCH")
      (description "Description")
      (fields (field (name "COPYRIGHT") "Copyright (C) 2025 Ultra Librarian. All rights reserved."))
      (libsource (lib "MCP3562RT-EST") (part "MCP3562RT-EST"))
    )
    (comp (ref "U8")
      (value "INA818ID")
      (footprint "SOIC-8_TEX")
      (fields (field (name "COPYRIGHT") "Copyright (C) 2025 Ultra Librarian. All rights reserved."))
      (libsource (lib "INA818ID") (part "INA818ID"))
    )
    (comp (ref "U9")
      (value "MP5035GJ-P")
      (footprint "TSOT23-6_MP5035_MNP")
      (description "2.9V to 22V 50mA to 2A Configurable Current-Limit Switch in a TSOT23-6 Package")
      (fields (field (name "COPYRIGHT") "Copyright (C) 2026 Ultra Librarian. All rights reserved."))
      (libsource (lib "MP5035GJ-P") (part "MP5035GJ-P"))
    )
    (comp (ref "U10")
      (value "STUSB4500QTR")
      (footprint "QFN24_STUSB4500_STM")
      (description "Standalone USB Type-C port controller for power sinking devices")
      (fields
        (field (name "MANUFACTURER_PART_NUMBER") "STUSB4500LQTR")
        (field (name "COPYRIGHT") "Copyright (C) 2025 Ultra Librarian. All rights reserved.")
      )
      (libsource (lib "STUSB4500LQTR") (part "STUSB4500LQTR"))
    )
    (comp (ref "U11")
      (value "ESDA25L")
      (footprint "SOT_A25L_STM")
      (description "- Clamp - Ipp Tvs Diode Surface Mount SOT-23-3")
      (fields (field (name "MF") "STMicroelectronics"))
      (libsource (lib "ESDA25L") (part "ESDA25L"))
    )
    (comp (ref "X1")
      (value "32.678 kHz")
      (footprint "XTAL_FC-135R_EPS")
      (description "SMD Crystal 32.768KHz-12.5pF-20ppm-2P-3.2*1.5*0.9mm")
      (fields
        (field (name "MANUFACTURER_PART_NUMBER") "FC-135 32.7680KA-A3")
        (field (name "COPYRIGHT") "Copyright (C) 2025 Ultra Librarian. All rights reserved.")
      )
      (libsource (lib "FC-13532P7680KA-A3") (part "FC-135 32.7680KA-A3"))
    )
    (comp (ref "X2")
      (value "ECS-320-8-33B-7KM-TR")
      (footprint "ECS-33B_ECS")
      (description "No Description Available")
      (fields (field (name "COPYRIGHT") "Copyright (C) 2026 Ultra Librarian. All rights reserved."))
      (libsource (lib "ECS-320-8-33B-7KM-TR") (part "ECS-320-8-33B-7KM-TR"))
    )
    (comp (ref "X3")
      (value "8MHz")
      (footprint "XTAL_NX3225GD-8MHZ-STD-CRA-3_NDK")
      (description "Description")
      (fields
        (field (name "MANUFACTURER_PART_NUMBER") "NX3225GD-8MHZ-STD-CRA-3")
        (field (name "COPYRIGHT") "Copyright (C) 2025 Ultra Librarian. All rights reserved.")
      )
      (libsource (lib "NX3225GD-8MHZ-STD-CRA-3") (part "NX3225GD-8MHZ-STD-CRA-3"))
    )
  )
  (nets
    (net (code "1") (name "/+ Output") (class "Default")
      (node (ref "J16") (pin "5") (pinfunction "5_5") (pintype "passive"))
      (node (ref "U8") (pin "3") (pinfunction "+IN_3") (pintype "input"))
    )
    (net (code "2") (name "/- Output") (class "Default")
      (node (ref "J16") (pin "4") (pinfunction "4_4") (pintype "passive"))
      (node (ref "U8") (pin "2") (pinfunction "-IN_2") (pintype "input"))
    )
    (net (code "3") (name "/1N") (class "Default")
      (node (ref "J1") (pin "2") (pinfunction "2_2") (pintype "passive"))
      (node (ref "J2") (pin "5") (pinfunction "5_5") (pintype "passive"))
      (node (ref "R14") (pin "1") (pinfunction "1_1") (pintype "passive"))
      (node (ref "R17") (pin "1") (pinfunction "1_1") (pintype "passive"))
      (node (ref "R4") (pin "1") (pinfunction "1_1") (pintype "passive"))
    )
    (net (code "4") (name "/1P") (class "Default")
      (node (ref "J2") (pin "4") (pinfunction "4_4") (pintype "passive"))
      (node (ref "R5") (pin "1") (pinfunction "1_1") (pintype "passive"))
    )
    (net (code "5") (name "/2P") (class "Default")
      (node (ref "J2") (pin "3") (pinfunction "3_3") (pintype "passive"))
      (node (ref "R6") (pin "1") (pinfunction "1_1") (pintype "passive"))
    )
    (net (code "6") (name "/3.3V") (class "Default")
      (node (ref "J12") (pin "2") (pinfunction "2_2") (pintype "passive"))
      (node (ref "J8") (pin "1") (pinfunction "1_1") (pintype "passive"))
      (node (ref "Q7") (pin "3") (pinfunction "D_3") (pintype "passive"))
      (node (ref "R62") (pin "2") (pinfunction "2_2") (pintype "passive"))
      (node (ref "R67") (pin "2") (pinfunction "2_2") (pintype "passive"))
    )
    (net (code "7") (name "/3.3V Control") (class "Default")
      (node (ref "J5") (pin "1") (pinfunction "1_1") (pintype "passive"))
      (node (ref "R20") (pin "2") (pinfunction "2_2") (pintype "passive"))
      (node (ref "U5") (pin "2") (pinfunction "PGED3/VREF+/AN0/C3INC/RPA0/ASDA1/CTED1/PMD7/RA0_2") (pintype "bidirectional"))
    )
    (net (code "8") (name "/3.3V for PIC") (class "Default")
      (node (ref "C14") (pin "2") (pinfunction "2_2") (pintype "passive"))
      (node (ref "J15") (pin "2") (pinfunction "2_2") (pintype "passive"))
      (node (ref "J22") (pin "1") (pinfunction "1_1") (pintype "passive"))
      (node (ref "J4") (pin "1") (pinfunction "1_1") (pintype "passive"))
      (node (ref "J7") (pin "1") (pinfunction "1_1") (pintype "passive"))
      (node (ref "Q7") (pin "2") (pinfunction "S_2") (pintype "passive"))
      (node (ref "R16") (pin "2") (pinfunction "2_2") (pintype "passive"))
      (node (ref "R22") (pin "1") (pinfunction "1_1") (pintype "passive"))
      (node (ref "R40") (pin "2") (pinfunction "2_2") (pintype "passive"))
      (node (ref "R43") (pin "2") (pinfunction "2_2") (pintype "passive"))
      (node (ref "R49") (pin "1") (pinfunction "1_1") (pintype "passive"))
      (node (ref "R50") (pin "2") (pinfunction "2_2") (pintype "passive"))
      (node (ref "R51") (pin "1") (pinfunction "1_1") (pintype "passive"))
      (node (ref "S2") (pin "1") (pinfunction "COM_1") (pintype "passive"))
    )
    (net (code "9") (name "/3P") (class "Default")
      (node (ref "J2") (pin "2") (pinfunction "2_2") (pintype "passive"))
      (node (ref "R8") (pin "1") (pinfunction "1_1") (pintype "passive"))
    )
    (net (code "10") (name "/4P") (class "Default")
      (node (ref "C15") (pin "1") (pinfunction "1_1") (pintype "passive"))
      (node (ref "D1") (pin "1") (pinfunction "A_1") (pintype "passive"))
      (node (ref "D3") (pin "2") (pinfunction "A_2") (pintype "passive"))
      (node (ref "D6") (pin "1") (pinfunction "A_1") (pintype "passive"))
      (node (ref "J1") (pin "1") (pinfunction "1_1") (pintype "passive"))
      (node (ref "J2") (pin "1") (pinfunction "1_1") (pintype "passive"))
      (node (ref "Q2") (pin "1") (pinfunction "S_1") (pintype "passive"))
      (node (ref "Q2") (pin "2") (pinfunction "S_2") (pintype "passive"))
      (node (ref "Q2") (pin "3") (pinfunction "S_3") (pintype "passive"))
      (node (ref "R11") (pin "1") (pinfunction "1_1") (pintype "passive"))
      (node (ref "R26") (pin "2") (pinfunction "2_2") (pintype "passive"))
    )
    (net (code "11") (name "/10V") (class "Default")
      (node (ref "C60") (pin "2") (pinfunction "2_2") (pintype "passive"))
      (node (ref "J11") (pin "1") (pinfunction "1_1") (pintype "passive"))
      (node (ref "J16") (pin "1") (pinfunction "1_1") (pintype "passive"))
      (node (ref "Q9") (pin "3") (pinfunction "D_3") (pintype "passive"))
      (node (ref "U8") (pin "7") (pinfunction "+VS_7") (pintype "passive"))
    )
    (net (code "12") (name "/10V Control") (class "Default")
      (node (ref "J9") (pin "1") (pinfunction "1_1") (pintype "passive"))
      (node (ref "R28") (pin "1") (pinfunction "1_1") (pintype "passive"))
      (node (ref "U5") (pin "3") (pinfunction "PGEC3/VREF-/AN1/RPA1/ASCL1/CTED2/PMD6/RA1_3") (pintype "bidirectional"))
    )
    (net (code "13") (name "/50 Ohms") (class "Default")
      (node (ref "C37") (pin "2") (pinfunction "2_2") (pintype "passive"))
      (node (ref "C38") (pin "2") (pinfunction "2_2") (pintype "passive"))
      (node (ref "L4") (pin "2") (pinfunction "2_2") (pintype "passive"))
      (node (ref "R53") (pin "1") (pinfunction "1_1") (pintype "passive"))
    )
    (net (code "14") (name "/BLE - RX") (class "Default")
      (node (ref "J22") (pin "2") (pinfunction "2_2") (pintype "passive"))
      (node (ref "U4") (pin "14") (pinfunction "P0.11_14") (pintype "bidirectional"))
      (node (ref "U5") (pin "4") (pinfunction "PGED2/AN2/C1IND/C2INB/C3IND/RPB0/PMD0/RB0_4") (pintype "bidirectional"))
    )
    (net (code "15") (name "/BLE - TX") (class "Default")
      (node (ref "J22") (pin "3") (pinfunction "3_3") (pintype "passive"))
      (node (ref "U4") (pin "15") (pinfunction "P0.12_15") (pintype "bidirectional"))
      (node (ref "U5") (pin "5") (pinfunction "PGEC2/AN3/C1INC/C2INA/LVDIN/RPB1/CTED12/PMD1//RB1_5") (pintype "bidirectional"))
    )
    (net (code "16") (name "/CD") (class "Default")
      (node (ref "D2") (pin "1") (pinfunction "A_1") (pintype "passive"))
      (node (ref "Q2") (pin "5-6-7-8") (pinfunction "D_5-6-7-8") (pintype "passive"))
      (node (ref "Q3") (pin "5-6-7-8") (pinfunction "D_5-6-7-8") (pintype "passive"))
    )
    (net (code "17") (name "/CHG") (class "Default")
      (node (ref "R31") (pin "1") (pinfunction "1_1") (pintype "passive"))
      (node (ref "U1") (pin "45") (pinfunction "CHG_45") (pintype "passive"))
    )
    (net (code "18") (name "/Charging Disable") (class "Default")
      (node (ref "J18") (pin "1") (pinfunction "1_1") (pintype "passive"))
      (node (ref "R44") (pin "1") (pinfunction "1_1") (pintype "passive"))
      (node (ref "U5") (pin "11") (pinfunction "SOSCI/RPB4/CTED11/RB4_11") (pintype "bidirectional"))
      (node (ref "U6") (pin "2") (pinfunction "CE_2") (pintype "input"))
    )
    (net (code "19") (name "/DEBUG - RXD") (class "Default")
      (node (ref "J13") (pin "4") (pinfunction "4_4") (pintype "passive"))
      (node (ref "J14") (pin "4") (pinfunction "4_4") (pintype "passive"))
      (node (ref "R46") (pin "1") (pinfunction "1_1") (pintype "passive"))
    )
    (net (code "20") (name "/DEBUG - TXD") (class "Default")
      (node (ref "J13") (pin "5") (pinfunction "5_5") (pintype "passive"))
      (node (ref "J14") (pin "5") (pinfunction "5_5") (pintype "passive"))
      (node (ref "R48") (pin "1") (pinfunction "1_1") (pintype "passive"))
    )
    (net (code "21") (name "/DSG") (class "Default")
      (node (ref "D9") (pin "2") (pinfunction "K_2") (pintype "passive"))
      (node (ref "R35") (pin "1") (pinfunction "1_1") (pintype "passive"))
      (node (ref "U1") (pin "43") (pinfunction "DSG_43") (pintype "passive"))
    )
    (net (code "22") (name "/Fuse") (class "Default")
      (node (ref "R21") (pin "2") (pinfunction "2_2") (pintype "passive"))
      (node (ref "U1") (pin "38") (pinfunction "FUSE_38") (pintype "passive"))
    )
    (net (code "23") (name "/LD") (class "Default")
      (node (ref "R38") (pin "1") (pinfunction "1_1") (pintype "passive"))
      (node (ref "U1") (pin "41") (pinfunction "LD_41") (pintype "passive"))
    )
    (net (code "24") (name "/MCLR") (class "Default")
      (node (ref "J14") (pin "1") (pinfunction "1_1") (pintype "passive"))
      (node (ref "R42") (pin "1") (pinfunction "1_1") (pintype "passive"))
      (node (ref "U5") (pin "1") (pinfunction "~{MCLR}_1") (pintype "input"))
    )
    (net (code "25") (name "/MCP3562 *CS") (class "Default")
      (node (ref "J17") (pin "5") (pinfunction "5_5") (pintype "passive"))
      (node (ref "R77") (pin "2") (pinfunction "2_2") (pintype "passive"))
      (node (ref "U5") (pin "14") (pinfunction "TMS/RPB5/USBID/RB5_14") (pintype "bidirectional"))
    )
    (net (code "26") (name "/MCP3562 *IRQ") (class "Default")
      (node (ref "J17") (pin "1") (pinfunction "1_1") (pintype "passive"))
      (node (ref "R67") (pin "1") (pinfunction "1_1") (pintype "passive"))
      (node (ref "R71") (pin "2") (pinfunction "2_2") (pintype "passive"))
      (node (ref "U5") (pin "16") (pinfunction "TDI/RPB7/CTED3/PMD5/INT0/RB7_16") (pintype "bidirectional"))
    )
    (net (code "27") (name "/MCP3562 SCK") (class "Default")
      (node (ref "J17") (pin "4") (pinfunction "4_4") (pintype "passive"))
      (node (ref "R76") (pin "2") (pinfunction "2_2") (pintype "passive"))
      (node (ref "R82") (pin "1") (pinfunction "1_1") (pintype "passive"))
      (node (ref "U5") (pin "26") (pinfunction "AN9/C3INA/RPB15/SCK2/CTED6/PMCS1/RB15_26") (pintype "bidirectional"))
    )
    (net (code "28") (name "/MCP3562 SDI") (class "Default")
      (node (ref "J17") (pin "3") (pinfunction "3_3") (pintype "passive"))
      (node (ref "R74") (pin "2") (pinfunction "2_2") (pintype "passive"))
      (node (ref "U5") (pin "25") (pinfunction "CVREFOUT/AN10/C3INB/RPB14/SCK1/CTED5/PMA1/RB14_25") (pintype "bidirectional"))
    )
    (net (code "29") (name "/MCP3562 SDO") (class "Default")
      (node (ref "J17") (pin "2") (pinfunction "2_2") (pintype "passive"))
      (node (ref "R73") (pin "2") (pinfunction "2_2") (pintype "passive"))
      (node (ref "U5") (pin "24") (pinfunction "AN11/RPB13/CTPLS/PMRD/RB13_24") (pintype "bidirectional"))
    )
    (net (code "30") (name "/PACK +") (class "Default")
      (node (ref "C16") (pin "2") (pinfunction "2_2") (pintype "passive"))
      (node (ref "C17") (pin "2") (pinfunction "2_2") (pintype "passive"))
      (node (ref "C18") (pin "1") (pinfunction "1_1") (pintype "passive"))
      (node (ref "C21") (pin "2") (pinfunction "2_2") (pintype "passive"))
      (node (ref "C47") (pin "2") (pinfunction "2_2") (pintype "passive"))
      (node (ref "C48") (pin "2") (pinfunction "2_2") (pintype "passive"))
      (node (ref "C50") (pin "2") (pinfunction "2_2") (pintype "passive"))
      (node (ref "C56") (pin "2") (pinfunction "2_2") (pintype "passive"))
      (node (ref "D5") (pin "1") (pinfunction "A_1") (pintype "passive"))
      (node (ref "D7") (pin "1") (pinfunction "A_1") (pintype "passive"))
      (node (ref "J6") (pin "1") (pinfunction "1_1") (pintype "passive"))
      (node (ref "Q3") (pin "1") (pinfunction "S_1") (pintype "passive"))
      (node (ref "Q3") (pin "2") (pinfunction "S_2") (pintype "passive"))
      (node (ref "Q3") (pin "3") (pinfunction "S_3") (pintype "passive"))
      (node (ref "Q6") (pin "2") (pinfunction "S_2") (pintype "passive"))
      (node (ref "R24") (pin "2") (pinfunction "2_2") (pintype "passive"))
      (node (ref "R25") (pin "2") (pinfunction "2_2") (pintype "passive"))
      (node (ref "R37") (pin "2") (pinfunction "2_2") (pintype "passive"))
      (node (ref "R39") (pin "2") (pinfunction "2_2") (pintype "passive"))
      (node (ref "R63") (pin "2") (pinfunction "2_2") (pintype "passive"))
      (node (ref "R64") (pin "2") (pinfunction "2_2") (pintype "passive"))
      (node (ref "U2") (pin "2") (pinfunction "VIN_2") (pintype "power_in"))
      (node (ref "U2") (pin "3") (pinfunction "EN_3") (pintype "input"))
      (node (ref "U3") (pin "1") (pinfunction "VIN_1") (pintype "power_in"))
      (node (ref "U3") (pin "4") (pinfunction "~{SHDN}_4") (pintype "input"))
      (node (ref "U6") (pin "9") (pinfunction "SRN_9") (pintype "input"))
    )
    (net (code "31") (name "/PIC Power Supply") (class "Default")
      (node (ref "C23") (pin "2") (pinfunction "2_2") (pintype "passive"))
      (node (ref "J14") (pin "2") (pinfunction "2_2") (pintype "passive"))
      (node (ref "R56") (pin "2") (pinfunction "2_2") (pintype "passive"))
      (node (ref "U5") (pin "13") (pinfunction "VDD_13") (pintype "power_in"))
      (node (ref "U5") (pin "23") (pinfunction "VUSB3V3_23") (pintype "power_in"))
      (node (ref "U5") (pin "28") (pinfunction "AVDD_28") (pintype "power_in"))
    )
    (net (code "32") (name "/Pack") (class "Default")
      (node (ref "R36") (pin "1") (pinfunction "1_1") (pintype "passive"))
      (node (ref "U1") (pin "42") (pinfunction "PACK_42") (pintype "passive"))
    )
    (net (code "33") (name "/REG1") (class "Default")
      (node (ref "C7") (pin "2") (pinfunction "2_2") (pintype "passive"))
      (node (ref "R10") (pin "2") (pinfunction "2_2") (pintype "passive"))
      (node (ref "R60") (pin "2") (pinfunction "2_2") (pintype "passive"))
      (node (ref "R61") (pin "2") (pinfunction "2_2") (pintype "passive"))
      (node (ref "R9") (pin "2") (pinfunction "2_2") (pintype "passive"))
      (node (ref "U1") (pin "35") (pinfunction "REG1_35") (pintype "passive"))
    )
    (net (code "34") (name "/SCL") (class "Default")
      (node (ref "J12") (pin "4") (pinfunction "4_4") (pintype "passive"))
      (node (ref "J23") (pin "1") (pinfunction "1_1") (pintype "passive"))
      (node (ref "J3") (pin "1") (pinfunction "1_1") (pintype "passive"))
      (node (ref "R9") (pin "1") (pinfunction "1_1") (pintype "passive"))
      (node (ref "U1") (pin "26") (pinfunction "SCL_26") (pintype "input"))
      (node (ref "U10") (pin "7") (pinfunction "SCL_7") (pintype "input"))
      (node (ref "U5") (pin "17") (pinfunction "TCK/RPB8/SCL1/CTED10/PMD4/RB8_17") (pintype "bidirectional"))
    )
    (net (code "35") (name "/SDA") (class "Default")
      (node (ref "J12") (pin "3") (pinfunction "3_3") (pintype "passive"))
      (node (ref "J23") (pin "2") (pinfunction "2_2") (pintype "passive"))
      (node (ref "J3") (pin "2") (pinfunction "2_2") (pintype "passive"))
      (node (ref "R10") (pin "1") (pinfunction "1_1") (pintype "passive"))
      (node (ref "U1") (pin "27") (pinfunction "SDA_27") (pintype "bidirectional"))
      (node (ref "U10") (pin "8") (pinfunction "SDA_8") (pintype "bidirectional"))
      (node (ref "U5") (pin "18") (pinfunction "TDO/RPB9/SDA1/CTED4/PMD3/RB9_18") (pintype "bidirectional"))
    )
    (net (code "36") (name "/USB Comms Enable") (class "Default")
      (node (ref "J19") (pin "1") (pinfunction "1_1") (pintype "passive"))
      (node (ref "U5") (pin "12") (pinfunction "SOSCO/RPA4/T1CK/CTED9/RA4_12") (pintype "bidirectional"))
      (node (ref "U9") (pin "1") (pinfunction "EN_1") (pintype "passive"))
    )
    (net (code "37") (name "/USB-C 5V") (class "Default")
      (node (ref "C62") (pin "2") (pinfunction "2_2") (pintype "passive"))
      (node (ref "J19") (pin "2") (pinfunction "2_2") (pintype "passive"))
      (node (ref "R41") (pin "2") (pinfunction "2_2") (pintype "passive"))
      (node (ref "U9") (pin "2") (pinfunction "SOURCE_2") (pintype "power_in"))
    )
    (net (code "38") (name "/USB_N") (class "Default")
      (node (ref "J20") (pin "A7") (pinfunction "A7_A7") (pintype "passive"))
      (node (ref "J21") (pin "2") (pinfunction "2_2") (pintype "passive"))
      (node (ref "U5") (pin "22") (pinfunction "D-_22") (pintype "passive"))
    )
    (net (code "39") (name "/USB_P") (class "Default")
      (node (ref "J20") (pin "A6") (pinfunction "A6_A6") (pintype "passive"))
      (node (ref "J21") (pin "1") (pinfunction "1_1") (pintype "passive"))
      (node (ref "U5") (pin "21") (pinfunction "D+_21") (pintype "passive"))
    )
    (net (code "40") (name "/VBUS +") (class "Default")
      (node (ref "C63") (pin "1") (pinfunction "1_1") (pintype "passive"))
      (node (ref "D10") (pin "2") (pinfunction "A_2") (pintype "passive"))
      (node (ref "Q12") (pin "1") (pinfunction "S_1") (pintype "passive"))
      (node (ref "Q12") (pin "2") (pinfunction "S_2") (pintype "passive"))
      (node (ref "Q12") (pin "3") (pinfunction "S_3") (pintype "passive"))
      (node (ref "R58") (pin "2") (pinfunction "2_2") (pintype "passive"))
      (node (ref "R66") (pin "1") (pinfunction "1_1") (pintype "passive"))
      (node (ref "R70") (pin "1") (pinfunction "1_1") (pintype "passive"))
      (node (ref "R86") (pin "2") (pinfunction "2_2") (pintype "passive"))
    )
    (net (code "41") (name "GND") (class "Default")
      (node (ref "C11") (pin "1") (pinfunction "1_1") (pintype "passive"))
      (node (ref "C14") (pin "1") (pinfunction "1_1") (pintype "passive"))
      (node (ref "C17") (pin "1") (pinfunction "1_1") (pintype "passive"))
      (node (ref "C19") (pin "2") (pinfunction "2_2") (pintype "passive"))
      (node (ref "C2") (pin "2") (pinfunction "2_2") (pintype "passive"))
      (node (ref "C20") (pin "2") (pinfunction "2_2") (pintype "passive"))
      (node (ref "C21") (pin "1") (pinfunction "1_1") (pintype "passive"))
      (node (ref "C22") (pin "2") (pinfunction "2_2") (pintype "passive"))
      (node (ref "C23") (pin "1") (pinfunction "1_1") (pintype "passive"))
      (node (ref "C24") (pin "1") (pinfunction "1_1") (pintype "passive"))
      (node (ref "C25") (pin "1") (pinfunction "1_1") (pintype "passive"))
      (node (ref "C26") (pin "1") (pinfunction "1_1") (pintype "passive"))
      (node (ref "C27") (pin "1") (pinfunction "1_1") (pintype "passive"))
      (node (ref "C28") (pin "1") (pinfunction "1_1") (pintype "passive"))
      (node (ref "C29") (pin "2") (pinfunction "2_2") (pintype "passive"))
      (node (ref "C3") (pin "2") (pinfunction "2_2") (pintype "passive"))
      (node (ref "C30") (pin "1") (pinfunction "1_1") (pintype "passive"))
      (node (ref "C31") (pin "1") (pinfunction "1_1") (pintype "passive"))
      (node (ref "C32") (pin "1") (pinfunction "1_1") (pintype "passive"))
      (node (ref "C33") (pin "1") (pinfunction "1_1") (pintype "passive"))
      (node (ref "C34") (pin "1") (pinfunction "1_1") (pintype "passive"))
      (node (ref "C35") (pin "1") (pinfunction "1_1") (pintype "passive"))
      (node (ref "C36") (pin "1") (pinfunction "1_1") (pintype "passive"))
      (node (ref "C37") (pin "1") (pinfunction "1_1") (pintype "passive"))
      (node (ref "C39") (pin "1") (pinfunction "1_1") (pintype "passive"))
      (node (ref "C4") (pin "1") (pinfunction "1_1") (pintype "passive"))
      (node (ref "C40") (pin "1") (pinfunction "1_1") (pintype "passive"))
      (node (ref "C41") (pin "1") (pinfunction "1_1") (pintype "passive"))
      (node (ref "C42") (pin "1") (pinfunction "1_1") (pintype "passive"))
      (node (ref "C43") (pin "1") (pinfunction "1_1") (pintype "passive"))
      (node (ref "C47") (pin "1") (pinfunction "1_1") (pintype "passive"))
      (node (ref "C48") (pin "1") (pinfunction "1_1") (pintype "passive"))
      (node (ref "C49") (pin "1") (pinfunction "1_1") (pintype "passive"))
      (node (ref "C5") (pin "1") (pinfunction "1_1") (pintype "passive"))
      (node (ref "C53") (pin "1") (pinfunction "1_1") (pintype "passive"))
      (node (ref "C54") (pin "2") (pinfunction "2_2") (pintype "passive"))
      (node (ref "C55") (pin "2") (pinfunction "2_2") (pintype "passive"))
      (node (ref "C57") (pin "2") (pinfunction "2_2") (pintype "passive"))
      (node (ref "C61") (pin "1") (pinfunction "1_1") (pintype "passive"))
      (node (ref "C62") (pin "1") (pinfunction "1_1") (pintype "passive"))
      (node (ref "C64") (pin "1") (pinfunction "1_1") (pintype "passive"))
      (node (ref "C65") (pin "1") (pinfunction "1_1") (pintype "passive"))
      (node (ref "C66") (pin "1") (pinfunction "1_1") (pintype "passive"))
      (node (ref "C67") (pin "1") (pinfunction "1_1") (pintype "passive"))
      (node (ref "C7") (pin "1") (pinfunction "1_1") (pintype "passive"))
      (node (ref "D4") (pin "2") (pinfunction "A_2") (pintype "passive"))
      (node (ref "D8") (pin "1") (pinfunction "A_1") (pintype "passive"))
      (node (ref "J10") (pin "2") (pinfunction "2_2") (pintype "passive"))
      (node (ref "J11") (pin "2") (pinfunction "2_2") (pintype "passive"))
      (node (ref "J12") (pin "1") (pinfunction "1_1") (pintype "passive"))
      (node (ref "J13") (pin "1") (pinfunction "1_1") (pintype "passive"))
      (node (ref "J14") (pin "3") (pinfunction "3_3") (pintype "passive"))
      (node (ref "J15") (pin "1") (pinfunction "1_1") (pintype "passive"))
      (node (ref "J18") (pin "2") (pinfunction "2_2") (pintype "passive"))
      (node (ref "J19") (pin "3") (pinfunction "3_3") (pintype "passive"))
      (node (ref "J20") (pin "A1") (pinfunction "A1_A1") (pintype "passive"))
      (node (ref "J20") (pin "A12") (pinfunction "A12_A12") (pintype "passive"))
      (node (ref "J20") (pin "B1") (pinfunction "B1_B1") (pintype "passive"))
      (node (ref "J20") (pin "B12") (pinfunction "B12_B12") (pintype "passive"))
      (node (ref "J22") (pin "4") (pinfunction "4_4") (pintype "passive"))
      (node (ref "J23") (pin "3") (pinfunction "3_3") (pintype "passive"))
      (node (ref "J3") (pin "3") (pinfunction "3_3") (pintype "passive"))
      (node (ref "J4") (pin "2") (pinfunction "2_2") (pintype "passive"))
      (node (ref "J5") (pin "2") (pinfunction "2_2") (pintype "passive"))
      (node (ref "J6") (pin "2") (pinfunction "2_2") (pintype "passive"))
      (node (ref "J7") (pin "2") (pinfunction "2_2") (pintype "passive"))
      (node (ref "J8") (pin "2") (pinfunction "2_2") (pintype "passive"))
      (node (ref "J9") (pin "2") (pinfunction "2_2") (pintype "passive"))
      (node (ref "L5") (pin "2") (pinfunction "2_2") (pintype "passive"))
      (node (ref "NT1") (pin "2") (pinfunction "2_2") (pintype "passive"))
      (node (ref "NT2") (pin "2") (pinfunction "2_2") (pintype "passive"))
      (node (ref "Q11") (pin "1") (pinfunction "S_1") (pintype "passive"))
      (node (ref "Q11") (pin "2") (pinfunction "S_2") (pintype "passive"))
      (node (ref "Q11") (pin "3") (pinfunction "S_3") (pintype "passive"))
      (node (ref "Q4") (pin "2") (pinfunction "S_2") (pintype "passive"))
      (node (ref "Q5") (pin "2") (pinfunction "S_2") (pintype "passive"))
      (node (ref "Q8") (pin "2") (pinfunction "S_2") (pintype "passive"))
      (node (ref "R12") (pin "1") (pinfunction "1_1") (pintype "passive"))
      (node (ref "R15") (pin "1") (pinfunction "1_1") (pintype "passive"))
      (node (ref "R17") (pin "2") (pinfunction "2_2") (pintype "passive"))
      (node (ref "R2") (pin "2") (pinfunction "2_2") (pintype "passive"))
      (node (ref "R23") (pin "1") (pinfunction "1_1") (pintype "passive"))
      (node (ref "R45") (pin "1") (pinfunction "1_1") (pintype "passive"))
      (node (ref "R47") (pin "1") (pinfunction "1_1") (pintype "passive"))
      (node (ref "R53") (pin "2") (pinfunction "2_2") (pintype "passive"))
      (node (ref "R54") (pin "1") (pinfunction "1_1") (pintype "passive"))
      (node (ref "R68") (pin "1") (pinfunction "1_1") (pintype "passive"))
      (node (ref "R7") (pin "2") (pinfunction "2_2") (pintype "passive"))
      (node (ref "R78") (pin "1") (pinfunction "1_1") (pintype "passive"))
      (node (ref "R90") (pin "1") (pinfunction "1_1") (pintype "passive"))
      (node (ref "R91") (pin "1") (pinfunction "1_1") (pintype "passive"))
      (node (ref "RT1") (pin "1") (pinfunction "1_1") (pintype "passive"))
      (node (ref "RT2") (pin "1") (pinfunction "1_1") (pintype "passive"))
      (node (ref "RT3") (pin "1") (pinfunction "1_1") (pintype "passive"))
      (node (ref "S1") (pin "2") (pinfunction "2_2") (pintype "passive"))
      (node (ref "S1") (pin "2'") (pinfunction "2'_2'") (pintype "passive"))
      (node (ref "U1") (pin "17") (pinfunction "VSS_17") (pintype "power_in"))
      (node (ref "U1") (pin "29") (pinfunction "CFETOFF_29") (pintype "passive"))
      (node (ref "U1") (pin "30") (pinfunction "DFETOFF_30") (pintype "passive"))
      (node (ref "U10") (pin "10") (pinfunction "GND_10") (pintype "power_in"))
      (node (ref "U10") (pin "22") (pinfunction "VSYS_22") (pintype "power_in"))
      (node (ref "U10") (pin "25") (pinfunction "EPAD_25") (pintype "power_in"))
      (node (ref "U10") (pin "3") (pinfunction "NU_3") (pintype "power_in"))
      (node (ref "U11") (pin "3") (pinfunction "3_3") (pintype "bidirectional"))
      (node (ref "U2") (pin "1") (pinfunction "PGND_1") (pintype "power_in"))
      (node (ref "U2") (pin "11") (pinfunction "DAP_11") (pintype "power_in"))
      (node (ref "U2") (pin "4") (pinfunction "NC_4") (pintype "passive"))
      (node (ref "U2") (pin "5") (pinfunction "FB_5") (pintype "input"))
      (node (ref "U2") (pin "6") (pinfunction "AGND_6") (pintype "power_in"))
      (node (ref "U3") (pin "2") (pinfunction "GND_2") (pintype "power_in"))
      (node (ref "U3") (pin "3") (pinfunction "NC_3") (pintype "passive"))
      (node (ref "U4") (pin "31") (pinfunction "VSS_31") (pintype "power_in"))
      (node (ref "U4") (pin "45") (pinfunction "VSS_45") (pintype "power_in"))
      (node (ref "U4") (pin "49") (pinfunction "VSS_49") (pintype "power_in"))
      (node (ref "U5") (pin "19") (pinfunction "VSS_19") (pintype "power_in"))
      (node (ref "U5") (pin "27") (pinfunction "AVSS_27") (pintype "power_in"))
      (node (ref "U5") (pin "8") (pinfunction "VSS_8") (pintype "power_in"))
      (node (ref "U6") (pin "11") (pinfunction "GND_11") (pintype "power_in"))
      (node (ref "U6") (pin "17") (pinfunction "EPAD_17") (pintype "power_in"))
      (node (ref "X2") (pin "2") (pinfunction "2_2") (pintype "passive"))
      (node (ref "X2") (pin "4") (pinfunction "4_4") (pintype "passive"))
    )
    (net (code "42") (name "GNDA") (class "Default")
      (node (ref "C45") (pin "2") (pinfunction "2_2") (pintype "passive"))
      (node (ref "C51") (pin "1") (pinfunction "1_1") (pintype "passive"))
      (node (ref "C58") (pin "1") (pinfunction "1_1") (pintype "passive"))
      (node (ref "C59") (pin "1") (pinfunction "1_1") (pintype "passive"))
      (node (ref "C60") (pin "1") (pinfunction "1_1") (pintype "passive"))
      (node (ref "J16") (pin "2") (pinfunction "2_2") (pintype "passive"))
      (node (ref "J16") (pin "3") (pinfunction "3_3") (pintype "passive"))
      (node (ref "NT1") (pin "1") (pinfunction "1_1") (pintype "passive"))
      (node (ref "U7") (pin "10") (pinfunction "NC_10") (pintype "passive"))
      (node (ref "U7") (pin "11") (pinfunction "NC_11") (pintype "passive"))
      (node (ref "U7") (pin "12") (pinfunction "NC_12") (pintype "passive"))
      (node (ref "U7") (pin "2") (pinfunction "AGND_2") (pintype "power_in"))
      (node (ref "U7") (pin "3") (pinfunction "REFIN-_3") (pintype "input"))
      (node (ref "U7") (pin "6") (pinfunction "CH1_6") (pintype "passive"))
      (node (ref "U7") (pin "7") (pinfunction "CH2_7") (pintype "passive"))
      (node (ref "U7") (pin "8") (pinfunction "CH3_8") (pintype "passive"))
      (node (ref "U7") (pin "9") (pinfunction "NC_9") (pintype "passive"))
      (node (ref "U8") (pin "4") (pinfunction "-VS_4") (pintype "passive"))
      (node (ref "U8") (pin "5") (pinfunction "REF_5") (pintype "input"))
    )
    (net (code "43") (name "GNDD") (class "Default")
      (node (ref "C46") (pin "1") (pinfunction "1_1") (pintype "passive"))
      (node (ref "C52") (pin "2") (pinfunction "2_2") (pintype "passive"))
      (node (ref "J17") (pin "6") (pinfunction "6_6") (pintype "passive"))
      (node (ref "NT2") (pin "1") (pinfunction "1_1") (pintype "passive"))
      (node (ref "U7") (pin "18") (pinfunction "MCLK_18") (pintype "bidirectional"))
      (node (ref "U7") (pin "19") (pinfunction "DGND_19") (pintype "power_in"))
    )
    (net (code "44") (name "Net-(C15-Pad2)") (class "Default")
      (node (ref "C15") (pin "2") (pinfunction "2_2") (pintype "passive"))
      (node (ref "C16") (pin "1") (pinfunction "1_1") (pintype "passive"))
    )
    (net (code "45") (name "Net-(C18-Pad2)") (class "Default")
      (node (ref "C18") (pin "2") (pinfunction "2_2") (pintype "passive"))
      (node (ref "C20") (pin "1") (pinfunction "1_1") (pintype "passive"))
    )
    (net (code "46") (name "Net-(C24-Pad2)") (class "Default")
      (node (ref "C24") (pin "2") (pinfunction "2_2") (pintype "passive"))
      (node (ref "R40") (pin "1") (pinfunction "1_1") (pintype "passive"))
      (node (ref "R42") (pin "2") (pinfunction "2_2") (pintype "passive"))
    )
    (net (code "47") (name "Net-(C26-Pad2)") (class "Default")
      (node (ref "C26") (pin "2") (pinfunction "2_2") (pintype "passive"))
      (node (ref "R43") (pin "1") (pinfunction "1_1") (pintype "passive"))
      (node (ref "U4") (pin "48") (pinfunction "VDD_48") (pintype "power_in"))
    )
    (net (code "48") (name "Net-(C31-Pad2)") (class "Default")
      (node (ref "C31") (pin "2") (pinfunction "2_2") (pintype "passive"))
      (node (ref "R49") (pin "2") (pinfunction "2_2") (pintype "passive"))
      (node (ref "U4") (pin "13") (pinfunction "VDD_13") (pintype "power_in"))
    )
    (net (code "49") (name "Net-(C33-Pad2)") (class "Default")
      (node (ref "C33") (pin "2") (pinfunction "2_2") (pintype "passive"))
      (node (ref "R50") (pin "1") (pinfunction "1_1") (pintype "passive"))
      (node (ref "U4") (pin "36") (pinfunction "VDD_36") (pintype "power_in"))
    )
    (net (code "50") (name "Net-(C38-Pad1)") (class "Default")
      (node (ref "C38") (pin "1") (pinfunction "1_1") (pintype "passive"))
      (node (ref "L5") (pin "1") (pinfunction "1_1") (pintype "passive"))
      (node (ref "L7") (pin "1") (pinfunction "1_1") (pintype "passive"))
    )
    (net (code "51") (name "Net-(C43-Pad2)") (class "Default")
      (node (ref "C43") (pin "2") (pinfunction "2_2") (pintype "passive"))
      (node (ref "R58") (pin "1") (pinfunction "1_1") (pintype "passive"))
    )
    (net (code "52") (name "Net-(C63-Pad2)") (class "Default")
      (node (ref "C63") (pin "2") (pinfunction "2_2") (pintype "passive"))
      (node (ref "R85") (pin "2") (pinfunction "2_2") (pintype "passive"))
    )
    (net (code "53") (name "Net-(D1-K)") (class "Default")
      (node (ref "D1") (pin "2") (pinfunction "K_2") (pintype "passive"))
      (node (ref "R1") (pin "1") (pinfunction "1_1") (pintype "passive"))
    )
    (net (code "54") (name "Net-(D2-K)") (class "Default")
      (node (ref "D2") (pin "2") (pinfunction "K_2") (pintype "passive"))
      (node (ref "R3") (pin "2") (pinfunction "2_2") (pintype "passive"))
    )
    (net (code "55") (name "Net-(D3-K)") (class "Default")
      (node (ref "D3") (pin "1") (pinfunction "K_1") (pintype "passive"))
      (node (ref "R13") (pin "2") (pinfunction "2_2") (pintype "passive"))
    )
    (net (code "56") (name "Net-(D4-K)") (class "Default")
      (node (ref "C19") (pin "1") (pinfunction "1_1") (pintype "passive"))
      (node (ref "D4") (pin "1") (pinfunction "K_1") (pintype "passive"))
      (node (ref "Q5") (pin "1") (pinfunction "G_1") (pintype "passive"))
      (node (ref "R21") (pin "1") (pinfunction "1_1") (pintype "passive"))
      (node (ref "R23") (pin "2") (pinfunction "2_2") (pintype "passive"))
    )
    (net (code "57") (name "Net-(D5-K)") (class "Default")
      (node (ref "D5") (pin "2") (pinfunction "K_2") (pintype "passive"))
      (node (ref "Q6") (pin "1") (pinfunction "G_1") (pintype "passive"))
      (node (ref "R25") (pin "1") (pinfunction "1_1") (pintype "passive"))
      (node (ref "R29") (pin "2") (pinfunction "2_2") (pintype "passive"))
    )
    (net (code "58") (name "Net-(D6-K)") (class "Default")
      (node (ref "D6") (pin "2") (pinfunction "K_2") (pintype "passive"))
      (node (ref "Q2") (pin "4") (pinfunction "G_4") (pintype "passive"))
      (node (ref "R26") (pin "1") (pinfunction "1_1") (pintype "passive"))
      (node (ref "R31") (pin "2") (pinfunction "2_2") (pintype "passive"))
    )
    (net (code "59") (name "Net-(D7-K)") (class "Default")
      (node (ref "D7") (pin "2") (pinfunction "K_2") (pintype "passive"))
      (node (ref "Q6") (pin "3") (pinfunction "D_3") (pintype "passive"))
      (node (ref "R24") (pin "1") (pinfunction "1_1") (pintype "passive"))
      (node (ref "R27") (pin "1") (pinfunction "1_1") (pintype "passive"))
      (node (ref "R32") (pin "2") (pinfunction "2_2") (pintype "passive"))
      (node (ref "R33") (pin "2") (pinfunction "2_2") (pintype "passive"))
    )
    (net (code "60") (name "Net-(D8-K)") (class "Default")
      (node (ref "D8") (pin "2") (pinfunction "K_2") (pintype "passive"))
      (node (ref "R29") (pin "1") (pinfunction "1_1") (pintype "passive"))
    )
    (net (code "61") (name "Net-(D9-A)") (class "Default")
      (node (ref "D9") (pin "1") (pinfunction "A_1") (pintype "passive"))
      (node (ref "R33") (pin "1") (pinfunction "1_1") (pintype "passive"))
    )
    (net (code "62") (name "Net-(D10-K)") (class "Default")
      (node (ref "C41") (pin "2") (pinfunction "2_2") (pintype "passive"))
      (node (ref "C42") (pin "2") (pinfunction "2_2") (pintype "passive"))
      (node (ref "D10") (pin "1") (pinfunction "K_1") (pintype "passive"))
      (node (ref "Q10") (pin "5") (pinfunction "D_5") (pintype "passive"))
      (node (ref "Q10") (pin "6") (pinfunction "D_6") (pintype "passive"))
      (node (ref "Q10") (pin "7") (pinfunction "D_7") (pintype "passive"))
      (node (ref "Q10") (pin "8") (pinfunction "D_8") (pintype "passive"))
      (node (ref "R59") (pin "1") (pinfunction "1_1") (pintype "passive"))
    )
    (net (code "63") (name "Net-(D12-Pad2)") (class "Default")
      (node (ref "D12") (pin "2") (pinfunction "2_2") (pintype "passive"))
      (node (ref "R66") (pin "2") (pinfunction "2_2") (pintype "passive"))
    )
    (net (code "64") (name "Net-(D13-Pad2)") (class "Default")
      (node (ref "D13") (pin "2") (pinfunction "2_2") (pintype "passive"))
      (node (ref "R70") (pin "2") (pinfunction "2_2") (pintype "passive"))
    )
    (net (code "65") (name "Net-(D14-A)") (class "Default")
      (node (ref "C61") (pin "2") (pinfunction "2_2") (pintype "passive"))
      (node (ref "C64") (pin "2") (pinfunction "2_2") (pintype "passive"))
      (node (ref "D14") (pin "2") (pinfunction "A_2") (pintype "passive"))
      (node (ref "J20") (pin "A4") (pinfunction "A4_A4") (pintype "passive"))
      (node (ref "J20") (pin "A9") (pinfunction "A9_A9") (pintype "passive"))
      (node (ref "J20") (pin "B4") (pinfunction "B4_B4") (pintype "passive"))
      (node (ref "J20") (pin "B8") (pinfunction "B8_B8") (pintype "passive"))
      (node (ref "Q12") (pin "5") (pinfunction "D_5") (pintype "passive"))
      (node (ref "Q12") (pin "6") (pinfunction "D_6") (pintype "passive"))
      (node (ref "Q12") (pin "7") (pinfunction "D_7") (pintype "passive"))
      (node (ref "Q12") (pin "8") (pinfunction "D_8") (pintype "passive"))
      (node (ref "R83") (pin "2") (pinfunction "2_2") (pintype "passive"))
      (node (ref "R84") (pin "2") (pinfunction "2_2") (pintype "passive"))
      (node (ref "U10") (pin "24") (pinfunction "VDD_24") (pintype "power_in"))
      (node (ref "U9") (pin "5") (pinfunction "VIN_5") (pintype "power_in"))
    )
    (net (code "66") (name "Net-(D14-C)") (class "Default")
      (node (ref "C65") (pin "2") (pinfunction "2_2") (pintype "passive"))
      (node (ref "D14") (pin "1") (pinfunction "C_1") (pintype "passive"))
      (node (ref "R84") (pin "1") (pinfunction "1_1") (pintype "passive"))
      (node (ref "R88") (pin "2") (pinfunction "2_2") (pintype "passive"))
    )
    (net (code "67") (name "Net-(E1-FEED)") (class "Default")
      (node (ref "E1") (pin "1") (pinfunction "FEED_1") (pintype "passive"))
      (node (ref "L7") (pin "2") (pinfunction "2_2") (pintype "passive"))
    )
    (net (code "68") (name "Net-(L2-Pad2)") (class "Default")
      (node (ref "L2") (pin "2") (pinfunction "2_2") (pintype "passive"))
      (node (ref "L3") (pin "1") (pinfunction "1_1") (pintype "passive"))
    )
    (net (code "69") (name "Net-(Q1-B)") (class "Default")
      (node (ref "Q1") (pin "3") (pinfunction "B_3") (pintype "passive"))
      (node (ref "U1") (pin "37") (pinfunction "BREG_37") (pintype "passive"))
    )
    (net (code "70") (name "Net-(Q1-C)") (class "Default")
      (node (ref "Q1") (pin "2") (pinfunction "C_2") (pintype "passive"))
      (node (ref "R3") (pin "1") (pinfunction "1_1") (pintype "passive"))
    )
    (net (code "71") (name "Net-(Q1-E)") (class "Default")
      (node (ref "C11") (pin "2") (pinfunction "2_2") (pintype "passive"))
      (node (ref "Q1") (pin "1") (pinfunction "E_1") (pintype "passive"))
      (node (ref "U1") (pin "36") (pinfunction "REGIN_36") (pintype "passive"))
    )
    (net (code "72") (name "Net-(Q3-G)") (class "Default")
      (node (ref "Q3") (pin "4") (pinfunction "G_4") (pintype "passive"))
      (node (ref "R27") (pin "2") (pinfunction "2_2") (pintype "passive"))
    )
    (net (code "73") (name "Net-(Q4-D)") (class "Default")
      (node (ref "Q4") (pin "3") (pinfunction "D_3") (pintype "passive"))
      (node (ref "Q7") (pin "1") (pinfunction "G_1") (pintype "passive"))
      (node (ref "R22") (pin "2") (pinfunction "2_2") (pintype "passive"))
    )
    (net (code "74") (name "Net-(Q4-G)") (class "Default")
      (node (ref "Q4") (pin "1") (pinfunction "G_1") (pintype "passive"))
      (node (ref "R20") (pin "1") (pinfunction "1_1") (pintype "passive"))
    )
    (net (code "75") (name "Net-(Q5-D)") (class "Default")
      (node (ref "Q5") (pin "3") (pinfunction "D_3") (pintype "passive"))
      (node (ref "R18") (pin "1") (pinfunction "1_1") (pintype "passive"))
    )
    (net (code "76") (name "Net-(Q8-D)") (class "Default")
      (node (ref "Q8") (pin "3") (pinfunction "D_3") (pintype "passive"))
      (node (ref "Q9") (pin "1") (pinfunction "G_1") (pintype "passive"))
      (node (ref "R34") (pin "2") (pinfunction "2_2") (pintype "passive"))
    )
    (net (code "77") (name "Net-(Q8-G)") (class "Default")
      (node (ref "Q8") (pin "1") (pinfunction "G_1") (pintype "passive"))
      (node (ref "R28") (pin "2") (pinfunction "2_2") (pintype "passive"))
    )
    (net (code "78") (name "Net-(Q9-S)") (class "Default")
      (node (ref "C22") (pin "1") (pinfunction "1_1") (pintype "passive"))
      (node (ref "J10") (pin "1") (pinfunction "1_1") (pintype "passive"))
      (node (ref "Q9") (pin "2") (pinfunction "S_2") (pintype "passive"))
      (node (ref "R30") (pin "2") (pinfunction "2_2") (pintype "passive"))
      (node (ref "R34") (pin "1") (pinfunction "1_1") (pintype "passive"))
    )
    (net (code "79") (name "Net-(Q10-G)") (class "Default")
      (node (ref "Q10") (pin "4") (pinfunction "G_4") (pintype "passive"))
      (node (ref "U6") (pin "15") (pinfunction "HIDRV_15") (pintype "output"))
    )
    (net (code "80") (name "Net-(Q11-G)") (class "Default")
      (node (ref "Q11") (pin "4") (pinfunction "G_4") (pintype "passive"))
      (node (ref "U6") (pin "13") (pinfunction "LODRV_13") (pintype "output"))
    )
    (net (code "81") (name "Net-(Q12-G)") (class "Default")
      (node (ref "Q12") (pin "4") (pinfunction "G_4") (pintype "passive"))
      (node (ref "R83") (pin "1") (pinfunction "1_1") (pintype "passive"))
      (node (ref "R85") (pin "1") (pinfunction "1_1") (pintype "passive"))
      (node (ref "R87") (pin "2") (pinfunction "2_2") (pintype "passive"))
    )
    (net (code "82") (name "Net-(R13-Pad1)") (class "Default")
      (node (ref "R13") (pin "1") (pinfunction "1_1") (pintype "passive"))
      (node (ref "R18") (pin "2") (pinfunction "2_2") (pintype "passive"))
    )
    (net (code "83") (name "Net-(R32-Pad1)") (class "Default")
      (node (ref "R32") (pin "1") (pinfunction "1_1") (pintype "passive"))
      (node (ref "R35") (pin "2") (pinfunction "2_2") (pintype "passive"))
    )
    (net (code "84") (name "Net-(R36-Pad2)") (class "Default")
      (node (ref "R36") (pin "2") (pinfunction "2_2") (pintype "passive"))
      (node (ref "R37") (pin "1") (pinfunction "1_1") (pintype "passive"))
    )
    (net (code "85") (name "Net-(R38-Pad2)") (class "Default")
      (node (ref "R38") (pin "2") (pinfunction "2_2") (pintype "passive"))
      (node (ref "R39") (pin "1") (pinfunction "1_1") (pintype "passive"))
    )
    (net (code "86") (name "Net-(R57-Pad1)") (class "Default")
      (node (ref "R57") (pin "1") (pinfunction "1_1") (pintype "passive"))
      (node (ref "X3") (pin "1") (pinfunction "1_1") (pintype "passive"))
    )
    (net (code "87") (name "Net-(R60-Pad1)") (class "Default")
      (node (ref "R60") (pin "1") (pinfunction "1_1") (pintype "passive"))
      (node (ref "R65") (pin "1") (pinfunction "1_1") (pintype "passive"))
      (node (ref "R68") (pin "2") (pinfunction "2_2") (pintype "passive"))
      (node (ref "RT3") (pin "2") (pinfunction "2_2") (pintype "passive"))
    )
    (net (code "88") (name "Net-(R64-Pad1)") (class "Default")
      (node (ref "R64") (pin "1") (pinfunction "1_1") (pintype "passive"))
      (node (ref "R69") (pin "2") (pinfunction "2_2") (pintype "passive"))
    )
    (net (code "89") (name "Net-(R75-Pad2)") (class "Default")
      (node (ref "R75") (pin "2") (pinfunction "2_2") (pintype "passive"))
      (node (ref "R76") (pin "1") (pinfunction "1_1") (pintype "passive"))
    )
    (net (code "90") (name "Net-(R80-Pad1)") (class "Default")
      (node (ref "R80") (pin "1") (pinfunction "1_1") (pintype "passive"))
      (node (ref "U8") (pin "8") (pinfunction "RG_8") (pintype "passive"))
    )
    (net (code "91") (name "Net-(R80-Pad2)") (class "Default")
      (node (ref "R80") (pin "2") (pinfunction "2_2") (pintype "passive"))
      (node (ref "U8") (pin "1") (pinfunction "RG_1") (pintype "passive"))
    )
    (net (code "92") (name "Net-(S2-NO)") (class "Default")
      (node (ref "R56") (pin "1") (pinfunction "1_1") (pintype "passive"))
      (node (ref "S2") (pin "2") (pinfunction "NO_2") (pintype "passive"))
    )
    (net (code "93") (name "Net-(U1-ALERT)") (class "Default")
      (node (ref "R2") (pin "1") (pinfunction "1_1") (pintype "passive"))
      (node (ref "U1") (pin "25") (pinfunction "ALERT_25") (pintype "passive"))
    )
    (net (code "94") (name "Net-(U1-BAT)") (class "Default")
      (node (ref "C1") (pin "1") (pinfunction "1_1") (pintype "passive"))
      (node (ref "C2") (pin "1") (pinfunction "1_1") (pintype "passive"))
      (node (ref "C3") (pin "1") (pinfunction "1_1") (pintype "passive"))
      (node (ref "R1") (pin "2") (pinfunction "2_2") (pintype "passive"))
      (node (ref "U1") (pin "47") (pinfunction "BAT_47") (pintype "power_in"))
    )
    (net (code "95") (name "Net-(U1-CP1)") (class "Default")
      (node (ref "C1") (pin "2") (pinfunction "2_2") (pintype "passive"))
      (node (ref "U1") (pin "46") (pinfunction "CP1_46") (pintype "passive"))
    )
    (net (code "96") (name "Net-(U1-HDQ)") (class "Default")
      (node (ref "R7") (pin "1") (pinfunction "1_1") (pintype "passive"))
      (node (ref "U1") (pin "28") (pinfunction "HDQ_28") (pintype "passive"))
    )
    (net (code "97") (name "Net-(U1-REG18)") (class "Default")
      (node (ref "C4") (pin "2") (pinfunction "2_2") (pintype "passive"))
      (node (ref "U1") (pin "24") (pinfunction "REG18_24") (pintype "power_in"))
    )
    (net (code "98") (name "Net-(U1-RST_SHUT)") (class "Default")
      (node (ref "R12") (pin "2") (pinfunction "2_2") (pintype "passive"))
      (node (ref "U1") (pin "33") (pinfunction "RST_SHUT_33") (pintype "passive"))
    )
    (net (code "99") (name "Net-(U1-SRN)") (class "Default")
      (node (ref "C12") (pin "2") (pinfunction "2_2") (pintype "passive"))
      (node (ref "C13") (pin "2") (pinfunction "2_2") (pintype "passive"))
      (node (ref "R15") (pin "2") (pinfunction "2_2") (pintype "passive"))
      (node (ref "U1") (pin "20") (pinfunction "SRN_20") (pintype "passive"))
    )
    (net (code "100") (name "Net-(U1-SRP)") (class "Default")
      (node (ref "C12") (pin "1") (pinfunction "1_1") (pintype "passive"))
      (node (ref "C13") (pin "1") (pinfunction "1_1") (pintype "passive"))
      (node (ref "R14") (pin "2") (pinfunction "2_2") (pintype "passive"))
      (node (ref "U1") (pin "18") (pinfunction "SRP_18") (pintype "passive"))
    )
    (net (code "101") (name "Net-(U1-TS1)") (class "Default")
      (node (ref "RT1") (pin "2") (pinfunction "2_2") (pintype "passive"))
      (node (ref "U1") (pin "21") (pinfunction "TS1_21") (pintype "passive"))
    )
    (net (code "102") (name "Net-(U1-TS3)") (class "Default")
      (node (ref "RT2") (pin "2") (pinfunction "2_2") (pintype "passive"))
      (node (ref "U1") (pin "23") (pinfunction "TS3_23") (pintype "passive"))
    )
    (net (code "103") (name "Net-(U1-VC0)") (class "Default")
      (node (ref "C5") (pin "2") (pinfunction "2_2") (pintype "passive"))
      (node (ref "C6") (pin "1") (pinfunction "1_1") (pintype "passive"))
      (node (ref "R4") (pin "2") (pinfunction "2_2") (pintype "passive"))
      (node (ref "U1") (pin "16") (pinfunction "VC0_16") (pintype "input"))
    )
    (net (code "104") (name "Net-(U1-VC1)") (class "Default")
      (node (ref "C6") (pin "2") (pinfunction "2_2") (pintype "passive"))
      (node (ref "C8") (pin "1") (pinfunction "1_1") (pintype "passive"))
      (node (ref "R5") (pin "2") (pinfunction "2_2") (pintype "passive"))
      (node (ref "U1") (pin "15") (pinfunction "VC1_15") (pintype "input"))
    )
    (net (code "105") (name "Net-(U1-VC2)") (class "Default")
      (node (ref "C8") (pin "2") (pinfunction "2_2") (pintype "passive"))
      (node (ref "C9") (pin "1") (pinfunction "1_1") (pintype "passive"))
      (node (ref "R6") (pin "2") (pinfunction "2_2") (pintype "passive"))
      (node (ref "U1") (pin "14") (pinfunction "VC2_14") (pintype "input"))
    )
    (net (code "106") (name "Net-(U1-VC3)") (class "Default")
      (node (ref "C10") (pin "1") (pinfunction "1_1") (pintype "passive"))
      (node (ref "C9") (pin "2") (pinfunction "2_2") (pintype "passive"))
      (node (ref "R8") (pin "2") (pinfunction "2_2") (pintype "passive"))
      (node (ref "U1") (pin "10") (pinfunction "VC5_10") (pintype "input"))
      (node (ref "U1") (pin "12") (pinfunction "VC4_12") (pintype "input"))
      (node (ref "U1") (pin "13") (pinfunction "VC3_13") (pintype "input"))
      (node (ref "U1") (pin "2") (pinfunction "VC9_2") (pintype "input"))
      (node (ref "U1") (pin "4") (pinfunction "VC8_4") (pintype "input"))
      (node (ref "U1") (pin "6") (pinfunction "VC7_6") (pintype "input"))
      (node (ref "U1") (pin "8") (pinfunction "VC6_8") (pintype "input"))
    )
    (net (code "107") (name "Net-(U1-VC10)") (class "Default")
      (node (ref "C10") (pin "2") (pinfunction "2_2") (pintype "passive"))
      (node (ref "R11") (pin "2") (pinfunction "2_2") (pintype "passive"))
      (node (ref "U1") (pin "48") (pinfunction "VC10_48") (pintype "input"))
    )
    (net (code "108") (name "Net-(U2-PG)") (class "Default")
      (node (ref "R19") (pin "1") (pinfunction "1_1") (pintype "passive"))
      (node (ref "U2") (pin "7") (pinfunction "PG_7") (pintype "output"))
    )
    (net (code "109") (name "Net-(U2-SLEEP)") (class "Default")
      (node (ref "L1") (pin "2") (pinfunction "2_2") (pintype "passive"))
      (node (ref "R16") (pin "1") (pinfunction "1_1") (pintype "passive"))
      (node (ref "R19") (pin "2") (pinfunction "2_2") (pintype "passive"))
      (node (ref "U2") (pin "10") (pinfunction "VOS_10") (pintype "input"))
      (node (ref "U2") (pin "8") (pinfunction "SLEEP_8") (pintype "input"))
    )
    (net (code "110") (name "Net-(U2-SW)") (class "Default")
      (node (ref "L1") (pin "1") (pinfunction "1_1") (pintype "passive"))
      (node (ref "U2") (pin "9") (pinfunction "SW_9") (pintype "output"))
    )
    (net (code "111") (name "Net-(U3-VOUT)") (class "Default")
      (node (ref "R30") (pin "1") (pinfunction "1_1") (pintype "passive"))
      (node (ref "U3") (pin "5") (pinfunction "VOUT_5") (pintype "power_in"))
    )
    (net (code "112") (name "Net-(U4-ANT)") (class "Default")
      (node (ref "L4") (pin "1") (pinfunction "1_1") (pintype "passive"))
      (node (ref "U4") (pin "30") (pinfunction "ANT_30") (pintype "passive"))
    )
    (net (code "113") (name "Net-(U4-DCC)") (class "Default")
      (node (ref "L2") (pin "1") (pinfunction "1_1") (pintype "passive"))
      (node (ref "U4") (pin "47") (pinfunction "DCC_47") (pintype "power_in"))
    )
    (net (code "114") (name "Net-(U4-DEC1)") (class "Default")
      (node (ref "C30") (pin "2") (pinfunction "2_2") (pintype "passive"))
      (node (ref "U4") (pin "1") (pinfunction "DEC1_1") (pintype "power_in"))
    )
    (net (code "115") (name "Net-(U4-DEC2)") (class "Default")
      (node (ref "C34") (pin "2") (pinfunction "2_2") (pintype "passive"))
      (node (ref "U4") (pin "32") (pinfunction "DEC2_32") (pintype "power_in"))
    )
    (net (code "116") (name "Net-(U4-DEC3)") (class "Default")
      (node (ref "C32") (pin "2") (pinfunction "2_2") (pintype "passive"))
      (node (ref "U4") (pin "33") (pinfunction "DEC3_33") (pintype "power_in"))
    )
    (net (code "117") (name "Net-(U4-DEC4)") (class "Default")
      (node (ref "C25") (pin "2") (pinfunction "2_2") (pintype "passive"))
      (node (ref "L3") (pin "2") (pinfunction "2_2") (pintype "passive"))
      (node (ref "U4") (pin "46") (pinfunction "DEC4_46") (pintype "power_in"))
    )
    (net (code "118") (name "Net-(U4-P0.00{slash}XL1)") (class "Default")
      (node (ref "C27") (pin "2") (pinfunction "2_2") (pintype "passive"))
      (node (ref "U4") (pin "2") (pinfunction "P0.00/XL1_2") (pintype "bidirectional"))
      (node (ref "X1") (pin "1") (pinfunction "1_1") (pintype "passive"))
    )
    (net (code "119") (name "Net-(U4-P0.01{slash}XL2)") (class "Default")
      (node (ref "C28") (pin "2") (pinfunction "2_2") (pintype "passive"))
      (node (ref "U4") (pin "3") (pinfunction "P0.01/XL2_3") (pintype "bidirectional"))
      (node (ref "X1") (pin "2") (pinfunction "2_2") (pintype "passive"))
    )
    (net (code "120") (name "Net-(U4-P0.13)") (class "Default")
      (node (ref "R51") (pin "2") (pinfunction "2_2") (pintype "passive"))
      (node (ref "S1") (pin "1") (pinfunction "1_1") (pintype "passive"))
      (node (ref "S1") (pin "1'") (pinfunction "1'_1'") (pintype "passive"))
      (node (ref "U4") (pin "16") (pinfunction "P0.13_16") (pintype "bidirectional"))
    )
    (net (code "121") (name "Net-(U4-P0.21{slash}NRESET)") (class "Default")
      (node (ref "R52") (pin "2") (pinfunction "2_2") (pintype "passive"))
      (node (ref "U4") (pin "24") (pinfunction "P0.21/NRESET_24") (pintype "bidirectional"))
    )
    (net (code "122") (name "Net-(U4-SWDCLK)") (class "Default")
      (node (ref "J15") (pin "4") (pinfunction "4_4") (pintype "passive"))
      (node (ref "U4") (pin "25") (pinfunction "SWDCLK_25") (pintype "input"))
    )
    (net (code "123") (name "Net-(U4-SWDIO)") (class "Default")
      (node (ref "J15") (pin "3") (pinfunction "3_3") (pintype "passive"))
      (node (ref "U4") (pin "26") (pinfunction "SWDIO_26") (pintype "bidirectional"))
    )
    (net (code "124") (name "Net-(U4-XC1)") (class "Default")
      (node (ref "C35") (pin "2") (pinfunction "2_2") (pintype "passive"))
      (node (ref "U4") (pin "34") (pinfunction "XC1_34") (pintype "input"))
      (node (ref "X2") (pin "1") (pinfunction "1_1") (pintype "passive"))
    )
    (net (code "125") (name "Net-(U4-XC2)") (class "Default")
      (node (ref "C36") (pin "2") (pinfunction "2_2") (pintype "passive"))
      (node (ref "U4") (pin "35") (pinfunction "XC2_35") (pintype "input"))
      (node (ref "X2") (pin "3") (pinfunction "3_3") (pintype "passive"))
    )
    (net (code "126") (name "Net-(U5-OSC1{slash}CLKI{slash}RPA2{slash}RA2)") (class "Default")
      (node (ref "C39") (pin "2") (pinfunction "2_2") (pintype "passive"))
      (node (ref "R55") (pin "2") (pinfunction "2_2") (pintype "passive"))
      (node (ref "U5") (pin "9") (pinfunction "OSC1/CLKI/RPA2/RA2_9") (pintype "bidirectional"))
      (node (ref "X3") (pin "2") (pinfunction "2_2") (pintype "passive"))
    )
    (net (code "127") (name "Net-(U5-OSC2{slash}CLKO{slash}RPA3{slash}PMA0{slash}RA3)") (class "Default")
      (node (ref "C40") (pin "2") (pinfunction "2_2") (pintype "passive"))
      (node (ref "R55") (pin "1") (pinfunction "1_1") (pintype "passive"))
      (node (ref "R57") (pin "2") (pinfunction "2_2") (pintype "passive"))
      (node (ref "U5") (pin "10") (pinfunction "OSC2/CLKO/RPA3/PMA0/RA3_10") (pintype "bidirectional"))
    )
    (net (code "128") (name "Net-(U5-PGEC1{slash}AN5{slash}C1INA{slash}C2INC{slash}RTCC{slash}RPB3{slash}SCL2{slash}PMWR{slash}RB3)") (class "Default")
      (node (ref "R48") (pin "2") (pinfunction "2_2") (pintype "passive"))
      (node (ref "U5") (pin "7") (pinfunction "PGEC1/AN5/C1INA/C2INC/RTCC/RPB3/SCL2/PMWR/RB3_7") (pintype "bidirectional"))
    )
    (net (code "129") (name "Net-(U5-PGED1{slash}AN4{slash}C1INB{slash}C2IND{slash}RPB2{slash}SDA2{slash}CTED13{slash}PMD2{slash}RB2)") (class "Default")
      (node (ref "R46") (pin "2") (pinfunction "2_2") (pintype "passive"))
      (node (ref "U5") (pin "6") (pinfunction "PGED1/AN4/C1INB/C2IND/RPB2/SDA2/CTED13/PMD2/RB2_6") (pintype "bidirectional"))
    )
    (net (code "130") (name "Net-(U5-VBUS)") (class "Default")
      (node (ref "R41") (pin "1") (pinfunction "1_1") (pintype "passive"))
      (node (ref "R45") (pin "2") (pinfunction "2_2") (pintype "passive"))
      (node (ref "U5") (pin "15") (pinfunction "VBUS_15") (pintype "power_in"))
    )
    (net (code "131") (name "Net-(U5-VCAP)") (class "Default")
      (node (ref "C29") (pin "1") (pinfunction "1_1") (pintype "passive"))
      (node (ref "U5") (pin "20") (pinfunction "VCAP_20") (pintype "power_in"))
    )
    (net (code "132") (name "Net-(U6-*PG)") (class "Default")
      (node (ref "D13") (pin "1") (pinfunction "1_1") (pintype "passive"))
      (node (ref "U6") (pin "5") (pinfunction "*PG_5") (pintype "output"))
    )
    (net (code "133") (name "Net-(U6-BTST)") (class "Default")
      (node (ref "C44") (pin "1") (pinfunction "1_1") (pintype "passive"))
      (node (ref "D11") (pin "3") (pinfunction "3_3") (pintype "passive"))
      (node (ref "U6") (pin "16") (pinfunction "BTST_16") (pintype "passive"))
    )
    (net (code "134") (name "Net-(U6-ISET)") (class "Default")
      (node (ref "C55") (pin "1") (pinfunction "1_1") (pintype "passive"))
      (node (ref "R47") (pin "2") (pinfunction "2_2") (pintype "passive"))
      (node (ref "R61") (pin "1") (pinfunction "1_1") (pintype "passive"))
      (node (ref "U6") (pin "7") (pinfunction "ISET_7") (pintype "input"))
    )
    (net (code "135") (name "Net-(U6-PH)") (class "Default")
      (node (ref "C44") (pin "2") (pinfunction "2_2") (pintype "passive"))
      (node (ref "L6") (pin "1") (pinfunction "1_1") (pintype "passive"))
      (node (ref "Q10") (pin "1") (pinfunction "S_1") (pintype "passive"))
      (node (ref "Q10") (pin "2") (pinfunction "S_2") (pintype "passive"))
      (node (ref "Q10") (pin "3") (pinfunction "S_3") (pintype "passive"))
      (node (ref "Q11") (pin "5") (pinfunction "D_5") (pintype "passive"))
      (node (ref "Q11") (pin "6") (pinfunction "D_6") (pintype "passive"))
      (node (ref "Q11") (pin "7") (pinfunction "D_7") (pintype "passive"))
      (node (ref "Q11") (pin "8") (pinfunction "D_8") (pintype "passive"))
      (node (ref "U6") (pin "14") (pinfunction "PH_14") (pintype "passive"))
    )
    (net (code "136") (name "Net-(U6-REGN)") (class "Default")
      (node (ref "D11") (pin "1") (pinfunction "1_1") (pintype "passive"))
      (node (ref "U6") (pin "12") (pinfunction "REGN_12") (pintype "output"))
    )
    (net (code "137") (name "Net-(U6-SRP)") (class "Default")
      (node (ref "C50") (pin "1") (pinfunction "1_1") (pintype "passive"))
      (node (ref "C54") (pin "1") (pinfunction "1_1") (pintype "passive"))
      (node (ref "L6") (pin "2") (pinfunction "2_2") (pintype "passive"))
      (node (ref "R63") (pin "1") (pinfunction "1_1") (pintype "passive"))
      (node (ref "U6") (pin "10") (pinfunction "SRP_10") (pintype "input"))
    )
    (net (code "138") (name "Net-(U6-STAT)") (class "Default")
      (node (ref "D12") (pin "1") (pinfunction "1_1") (pintype "passive"))
      (node (ref "U6") (pin "3") (pinfunction "STAT_3") (pintype "passive"))
    )
    (net (code "139") (name "Net-(U6-TS)") (class "Default")
      (node (ref "C57") (pin "1") (pinfunction "1_1") (pintype "passive"))
      (node (ref "R65") (pin "2") (pinfunction "2_2") (pintype "passive"))
      (node (ref "U6") (pin "4") (pinfunction "TS_4") (pintype "input"))
    )
    (net (code "140") (name "Net-(U6-VCC)") (class "Default")
      (node (ref "C49") (pin "2") (pinfunction "2_2") (pintype "passive"))
      (node (ref "R59") (pin "2") (pinfunction "2_2") (pintype "passive"))
      (node (ref "U6") (pin "1") (pinfunction "VCC_1") (pintype "power_in"))
    )
    (net (code "141") (name "Net-(U6-VFB)") (class "Default")
      (node (ref "C56") (pin "1") (pinfunction "1_1") (pintype "passive"))
      (node (ref "R69") (pin "1") (pinfunction "1_1") (pintype "passive"))
      (node (ref "R78") (pin "2") (pinfunction "2_2") (pintype "passive"))
      (node (ref "U6") (pin "8") (pinfunction "VFB_8") (pintype "output"))
    )
    (net (code "142") (name "Net-(U6-VREF)") (class "Default")
      (node (ref "C53") (pin "2") (pinfunction "2_2") (pintype "passive"))
      (node (ref "R44") (pin "2") (pinfunction "2_2") (pintype "passive"))
      (node (ref "U6") (pin "6") (pinfunction "VREF_6") (pintype "output"))
    )
    (net (code "143") (name "Net-(U7-*CS)") (class "Default")
      (node (ref "R77") (pin "1") (pinfunction "1_1") (pintype "passive"))
      (node (ref "U7") (pin "13") (pinfunction "*CS_13") (pintype "input"))
    )
    (net (code "144") (name "Net-(U7-*IRQ{slash}MDAT)") (class "Default")
      (node (ref "R71") (pin "1") (pinfunction "1_1") (pintype "passive"))
      (node (ref "U7") (pin "17") (pinfunction "*IRQ/MDAT_17") (pintype "output"))
    )
    (net (code "145") (name "Net-(U7-AVDD)") (class "Default")
      (node (ref "C45") (pin "1") (pinfunction "1_1") (pintype "passive"))
      (node (ref "C46") (pin "2") (pinfunction "2_2") (pintype "passive"))
      (node (ref "C51") (pin "2") (pinfunction "2_2") (pintype "passive"))
      (node (ref "C52") (pin "1") (pinfunction "1_1") (pintype "passive"))
      (node (ref "R62") (pin "1") (pinfunction "1_1") (pintype "passive"))
      (node (ref "U7") (pin "1") (pinfunction "AVDD_1") (pintype "power_in"))
      (node (ref "U7") (pin "20") (pinfunction "DVDD_20") (pintype "power_in"))
    )
    (net (code "146") (name "Net-(U7-CH0)") (class "Default")
      (node (ref "C58") (pin "2") (pinfunction "2_2") (pintype "passive"))
      (node (ref "R72") (pin "2") (pinfunction "2_2") (pintype "passive"))
      (node (ref "R82") (pin "2") (pinfunction "2_2") (pintype "passive"))
      (node (ref "U7") (pin "5") (pinfunction "CH0_5") (pintype "passive"))
    )
    (net (code "147") (name "Net-(U7-REFIN+{slash}OUT)") (class "Default")
      (node (ref "C59") (pin "2") (pinfunction "2_2") (pintype "passive"))
      (node (ref "U7") (pin "4") (pinfunction "REFIN+/OUT_4") (pintype "bidirectional"))
    )
    (net (code "148") (name "Net-(U7-SCK)") (class "Default")
      (node (ref "R75") (pin "1") (pinfunction "1_1") (pintype "passive"))
      (node (ref "U7") (pin "14") (pinfunction "SCK_14") (pintype "input"))
    )
    (net (code "149") (name "Net-(U7-SDI)") (class "Default")
      (node (ref "R74") (pin "1") (pinfunction "1_1") (pintype "passive"))
      (node (ref "U7") (pin "15") (pinfunction "SDI_15") (pintype "input"))
    )
    (net (code "150") (name "Net-(U7-SDO)") (class "Default")
      (node (ref "R73") (pin "1") (pinfunction "1_1") (pintype "passive"))
      (node (ref "U7") (pin "16") (pinfunction "SDO_16") (pintype "output"))
    )
    (net (code "151") (name "Net-(U8-OUT)") (class "Default")
      (node (ref "R72") (pin "1") (pinfunction "1_1") (pintype "passive"))
      (node (ref "U8") (pin "6") (pinfunction "OUT_6") (pintype "output"))
    )
    (net (code "152") (name "Net-(U10-ADDR0)") (class "Default")
      (node (ref "R90") (pin "2") (pinfunction "2_2") (pintype "passive"))
      (node (ref "U10") (pin "12") (pinfunction "ADDR0_12") (pintype "input"))
    )
    (net (code "153") (name "Net-(U10-ADDR1)") (class "Default")
      (node (ref "R91") (pin "2") (pinfunction "2_2") (pintype "passive"))
      (node (ref "U10") (pin "13") (pinfunction "ADDR1_13") (pintype "input"))
    )
    (net (code "154") (name "Net-(U10-CC1)") (class "Default")
      (node (ref "J20") (pin "A5") (pinfunction "A5_A5") (pintype "passive"))
      (node (ref "U10") (pin "1") (pinfunction "CC1DB_1") (pintype "bidirectional"))
      (node (ref "U10") (pin "2") (pinfunction "CC1_2") (pintype "bidirectional"))
      (node (ref "U11") (pin "2") (pinfunction "2_2") (pintype "bidirectional"))
    )
    (net (code "155") (name "Net-(U10-CC2)") (class "Default")
      (node (ref "J20") (pin "B5") (pinfunction "B5_B5") (pintype "passive"))
      (node (ref "U10") (pin "4") (pinfunction "CC2_4") (pintype "bidirectional"))
      (node (ref "U10") (pin "5") (pinfunction "CC2DB_5") (pintype "bidirectional"))
      (node (ref "U11") (pin "1") (pinfunction "1_1") (pintype "bidirectional"))
    )
    (net (code "156") (name "Net-(U10-DISCH)") (class "Default")
      (node (ref "R86") (pin "1") (pinfunction "1_1") (pintype "passive"))
      (node (ref "U10") (pin "9") (pinfunction "DISCH_9") (pintype "bidirectional"))
    )
    (net (code "157") (name "Net-(U10-RESET)") (class "Default")
      (node (ref "R54") (pin "2") (pinfunction "2_2") (pintype "passive"))
      (node (ref "U10") (pin "6") (pinfunction "RESET_6") (pintype "input"))
    )
    (net (code "158") (name "Net-(U10-VBUS_EN_SNK)") (class "Default")
      (node (ref "R87") (pin "1") (pinfunction "1_1") (pintype "passive"))
      (node (ref "U10") (pin "16") (pinfunction "VBUS_EN_SNK_16") (pintype "output"))
    )
    (net (code "159") (name "Net-(U10-VBUS_VS_DISCH)") (class "Default")
      (node (ref "R88") (pin "1") (pinfunction "1_1") (pintype "passive"))
      (node (ref "U10") (pin "18") (pinfunction "VBUS_VS_DISCH_18") (pintype "input"))
    )
    (net (code "160") (name "Net-(U10-VREG_1V2)") (class "Default")
      (node (ref "C67") (pin "2") (pinfunction "2_2") (pintype "passive"))
      (node (ref "U10") (pin "21") (pinfunction "VREG_1V2_21") (pintype "bidirectional"))
    )
    (net (code "161") (name "Net-(U10-VREG_2V7)") (class "Default")
      (node (ref "C66") (pin "2") (pinfunction "2_2") (pintype "passive"))
      (node (ref "U10") (pin "23") (pinfunction "VREG_2V7_23") (pintype "power_in"))
    )
    (net (code "162") (name "unconnected-(D11-NC-Pad2)") (class "Default")
      (node (ref "D11") (pin "2") (pinfunction "NC_2") (pintype "passive"))
    )
    (net (code "163") (name "unconnected-(E1-NC-Pad2)") (class "Default")
      (node (ref "E1") (pin "2") (pinfunction "NC_2") (pintype "passive"))
    )
    (net (code "164") (name "unconnected-(J13-Pad2)") (class "Default")
      (node (ref "J13") (pin "2") (pinfunction "2_2") (pintype "passive"))
    )
    (net (code "165") (name "unconnected-(J13-Pad3)") (class "Default")
      (node (ref "J13") (pin "3") (pinfunction "3_3") (pintype "passive"))
    )
    (net (code "166") (name "unconnected-(J13-Pad6)") (class "Default")
      (node (ref "J13") (pin "6") (pinfunction "6_6") (pintype "passive"))
    )
    (net (code "167") (name "unconnected-(J14-Pad6)") (class "Default")
      (node (ref "J14") (pin "6") (pinfunction "6_6") (pintype "passive"))
    )
    (net (code "168") (name "unconnected-(J16-Pad6)") (class "Default")
      (node (ref "J16") (pin "6") (pinfunction "6_6") (pintype "passive"))
    )
    (net (code "169") (name "unconnected-(J20-PadA2)") (class "Default")
      (node (ref "J20") (pin "A2") (pinfunction "A2_A2") (pintype "passive"))
    )
    (net (code "170") (name "unconnected-(J20-PadA3)") (class "Default")
      (node (ref "J20") (pin "A3") (pinfunction "A3_A3") (pintype "passive"))
    )
    (net (code "171") (name "unconnected-(J20-PadA8)") (class "Default")
      (node (ref "J20") (pin "A8") (pinfunction "A8_A8") (pintype "passive"))
    )
    (net (code "172") (name "unconnected-(J20-PadA10)") (class "Default")
      (node (ref "J20") (pin "A10") (pinfunction "A10_A10") (pintype "passive"))
    )
    (net (code "173") (name "unconnected-(J20-PadA11)") (class "Default")
      (node (ref "J20") (pin "A11") (pinfunction "A11_A11") (pintype "passive"))
    )
    (net (code "174") (name "unconnected-(J20-PadB2)") (class "Default")
      (node (ref "J20") (pin "B2") (pinfunction "B2_B2") (pintype "passive"))
    )
    (net (code "175") (name "unconnected-(J20-PadB3)") (class "Default")
      (node (ref "J20") (pin "B3") (pinfunction "B3_B3") (pintype "passive"))
    )
    (net (code "176") (name "unconnected-(J20-PadB6)") (class "Default")
      (node (ref "J20") (pin "B6") (pinfunction "B6_B6") (pintype "passive"))
    )
    (net (code "177") (name "unconnected-(J20-PadB7)") (class "Default")
      (node (ref "J20") (pin "B7") (pinfunction "B7_B7") (pintype "passive"))
    )
    (net (code "178") (name "unconnected-(J20-PadB9)") (class "Default")
      (node (ref "J20") (pin "B9") (pinfunction "B9_B9") (pintype "passive"))
    )
    (net (code "179") (name "unconnected-(J20-PadB10)") (class "Default")
      (node (ref "J20") (pin "B10") (pinfunction "B10_B10") (pintype "passive"))
    )
    (net (code "180") (name "unconnected-(J20-PadB11)") (class "Default")
      (node (ref "J20") (pin "B11") (pinfunction "B11_B11") (pintype "passive"))
    )
    (net (code "181") (name "unconnected-(R52-Pad1)") (class "Default")
      (node (ref "R52") (pin "1") (pinfunction "1_1") (pintype "passive"))
    )
    (net (code "182") (name "unconnected-(U1-DCHG-Pad31)") (class "Default")
      (node (ref "U1") (pin "31") (pinfunction "DCHG_31") (pintype "passive"))
    )
    (net (code "183") (name "unconnected-(U1-DDSG-Pad32)") (class "Default")
      (node (ref "U1") (pin "32") (pinfunction "DDSG_32") (pintype "passive"))
    )
    (net (code "184") (name "unconnected-(U1-NC-Pad1)") (class "Default")
      (node (ref "U1") (pin "1") (pinfunction "NC_1") (pintype "passive"))
    )
    (net (code "185") (name "unconnected-(U1-NC-Pad3)") (class "Default")
      (node (ref "U1") (pin "3") (pinfunction "NC_3") (pintype "passive"))
    )
    (net (code "186") (name "unconnected-(U1-NC-Pad5)") (class "Default")
      (node (ref "U1") (pin "5") (pinfunction "NC_5") (pintype "passive"))
    )
    (net (code "187") (name "unconnected-(U1-NC-Pad7)") (class "Default")
      (node (ref "U1") (pin "7") (pinfunction "NC_7") (pintype "passive"))
    )
    (net (code "188") (name "unconnected-(U1-NC-Pad9)") (class "Default")
      (node (ref "U1") (pin "9") (pinfunction "NC_9") (pintype "passive"))
    )
    (net (code "189") (name "unconnected-(U1-NC-Pad11)") (class "Default")
      (node (ref "U1") (pin "11") (pinfunction "NC_11") (pintype "passive"))
    )
    (net (code "190") (name "unconnected-(U1-NC-Pad19)") (class "Default")
      (node (ref "U1") (pin "19") (pinfunction "NC_19") (pintype "passive"))
    )
    (net (code "191") (name "unconnected-(U1-NC-Pad44)") (class "Default")
      (node (ref "U1") (pin "44") (pinfunction "NC_44") (pintype "passive"))
    )
    (net (code "192") (name "unconnected-(U1-PCHG-Pad40)") (class "Default")
      (node (ref "U1") (pin "40") (pinfunction "PCHG_40") (pintype "passive"))
    )
    (net (code "193") (name "unconnected-(U1-PDSG-Pad39)") (class "Default")
      (node (ref "U1") (pin "39") (pinfunction "PDSG_39") (pintype "passive"))
    )
    (net (code "194") (name "unconnected-(U1-REG2-Pad34)") (class "Default")
      (node (ref "U1") (pin "34") (pinfunction "REG2_34") (pintype "passive"))
    )
    (net (code "195") (name "unconnected-(U1-TS2-Pad22)") (class "Default")
      (node (ref "U1") (pin "22") (pinfunction "TS2_22") (pintype "passive"))
    )
    (net (code "196") (name "unconnected-(U4-NC-Pad44)") (class "Default")
      (node (ref "U4") (pin "44") (pinfunction "NC_44") (pintype "passive"))
    )
    (net (code "197") (name "unconnected-(U4-NFC1{slash}P0.09-Pad11)") (class "Default")
      (node (ref "U4") (pin "11") (pinfunction "NFC1/P0.09_11") (pintype "bidirectional"))
    )
    (net (code "198") (name "unconnected-(U4-NFC2{slash}P0.10-Pad12)") (class "Default")
      (node (ref "U4") (pin "12") (pinfunction "NFC2/P0.10_12") (pintype "bidirectional"))
    )
    (net (code "199") (name "unconnected-(U4-P0.02{slash}AIN0-Pad4)") (class "Default")
      (node (ref "U4") (pin "4") (pinfunction "P0.02/AIN0_4") (pintype "bidirectional"))
    )
    (net (code "200") (name "unconnected-(U4-P0.03{slash}AIN1-Pad5)") (class "Default")
      (node (ref "U4") (pin "5") (pinfunction "P0.03/AIN1_5") (pintype "bidirectional"))
    )
    (net (code "201") (name "unconnected-(U4-P0.04{slash}AIN2-Pad6)") (class "Default")
      (node (ref "U4") (pin "6") (pinfunction "P0.04/AIN2_6") (pintype "bidirectional"))
    )
    (net (code "202") (name "unconnected-(U4-P0.05{slash}AIN3-Pad7)") (class "Default")
      (node (ref "U4") (pin "7") (pinfunction "P0.05/AIN3_7") (pintype "bidirectional"))
    )
    (net (code "203") (name "unconnected-(U4-P0.06-Pad8)") (class "Default")
      (node (ref "U4") (pin "8") (pinfunction "P0.06_8") (pintype "bidirectional"))
    )
    (net (code "204") (name "unconnected-(U4-P0.07-Pad9)") (class "Default")
      (node (ref "U4") (pin "9") (pinfunction "P0.07_9") (pintype "bidirectional"))
    )
    (net (code "205") (name "unconnected-(U4-P0.08-Pad10)") (class "Default")
      (node (ref "U4") (pin "10") (pinfunction "P0.08_10") (pintype "bidirectional"))
    )
    (net (code "206") (name "unconnected-(U4-P0.14{slash}TRACEDATA[3]-Pad17)") (class "Default")
      (node (ref "U4") (pin "17") (pinfunction "P0.14/TRACEDATA[3]_17") (pintype "bidirectional"))
    )
    (net (code "207") (name "unconnected-(U4-P0.15{slash}TRACEDATA[2]-Pad18)") (class "Default")
      (node (ref "U4") (pin "18") (pinfunction "P0.15/TRACEDATA[2]_18") (pintype "bidirectional"))
    )
    (net (code "208") (name "unconnected-(U4-P0.16{slash}TRACEDATA[1]-Pad19)") (class "Default")
      (node (ref "U4") (pin "19") (pinfunction "P0.16/TRACEDATA[1]_19") (pintype "bidirectional"))
    )
    (net (code "209") (name "unconnected-(U4-P0.17-Pad20)") (class "Default")
      (node (ref "U4") (pin "20") (pinfunction "P0.17_20") (pintype "bidirectional"))
    )
    (net (code "210") (name "unconnected-(U4-P0.18{slash}TRACEDATA[0]{slash}SWO-Pad21)") (class "Default")
      (node (ref "U4") (pin "21") (pinfunction "P0.18/TRACEDATA[0]/SWO_21") (pintype "bidirectional"))
    )
    (net (code "211") (name "unconnected-(U4-P0.19-Pad22)") (class "Default")
      (node (ref "U4") (pin "22") (pinfunction "P0.19_22") (pintype "bidirectional"))
    )
    (net (code "212") (name "unconnected-(U4-P0.20{slash}TRACECLK-Pad23)") (class "Default")
      (node (ref "U4") (pin "23") (pinfunction "P0.20/TRACECLK_23") (pintype "bidirectional"))
    )
    (net (code "213") (name "unconnected-(U4-P0.22-Pad27)") (class "Default")
      (node (ref "U4") (pin "27") (pinfunction "P0.22_27") (pintype "bidirectional"))
    )
    (net (code "214") (name "unconnected-(U4-P0.23-Pad28)") (class "Default")
      (node (ref "U4") (pin "28") (pinfunction "P0.23_28") (pintype "bidirectional"))
    )
    (net (code "215") (name "unconnected-(U4-P0.24-Pad29)") (class "Default")
      (node (ref "U4") (pin "29") (pinfunction "P0.24_29") (pintype "bidirectional"))
    )
    (net (code "216") (name "unconnected-(U4-P0.25-Pad37)") (class "Default")
      (node (ref "U4") (pin "37") (pinfunction "P0.25_37") (pintype "bidirectional"))
    )
    (net (code "217") (name "unconnected-(U4-P0.26-Pad38)") (class "Default")
      (node (ref "U4") (pin "38") (pinfunction "P0.26_38") (pintype "bidirectional"))
    )
    (net (code "218") (name "unconnected-(U4-P0.27-Pad39)") (class "Default")
      (node (ref "U4") (pin "39") (pinfunction "P0.27_39") (pintype "bidirectional"))
    )
    (net (code "219") (name "unconnected-(U4-P0.28{slash}AIN4-Pad40)") (class "Default")
      (node (ref "U4") (pin "40") (pinfunction "P0.28/AIN4_40") (pintype "bidirectional"))
    )
    (net (code "220") (name "unconnected-(U4-P0.29{slash}AIN5-Pad41)") (class "Default")
      (node (ref "U4") (pin "41") (pinfunction "P0.29/AIN5_41") (pintype "bidirectional"))
    )
    (net (code "221") (name "unconnected-(U4-P0.30{slash}AIN6-Pad42)") (class "Default")
      (node (ref "U4") (pin "42") (pinfunction "P0.30/AIN6_42") (pintype "bidirectional"))
    )
    (net (code "222") (name "unconnected-(U4-P0.31{slash}AIN7-Pad43)") (class "Default")
      (node (ref "U4") (pin "43") (pinfunction "P0.31/AIN7_43") (pintype "bidirectional"))
    )
    (net (code "223") (name "unconnected-(U9-DV{slash}DT-Pad6)") (class "Default")
      (node (ref "U9") (pin "6") (pinfunction "DV/DT_6") (pintype "passive"))
    )
    (net (code "224") (name "unconnected-(U9-GND-Pad3)") (class "Default")
      (node (ref "U9") (pin "3") (pinfunction "GND_3") (pintype "power_in"))
    )
    (net (code "225") (name "unconnected-(U9-ILIMIT-Pad4)") (class "Default")
      (node (ref "U9") (pin "4") (pinfunction "ILIMIT_4") (pintype "passive"))
    )
    (net (code "226") (name "unconnected-(U10-ALERT-Pad19)") (class "Default")
      (node (ref "U10") (pin "19") (pinfunction "ALERT_19") (pintype "output"))
    )
    (net (code "227") (name "unconnected-(U10-ATTACH-Pad11)") (class "Default")
      (node (ref "U10") (pin "11") (pinfunction "ATTACH_11") (pintype "output"))
    )
    (net (code "228") (name "unconnected-(U10-A_B_SIDE-Pad17)") (class "Default")
      (node (ref "U10") (pin "17") (pinfunction "A_B_SIDE_17") (pintype "output"))
    )
    (net (code "229") (name "unconnected-(U10-GPIO-Pad15)") (class "Default")
      (node (ref "U10") (pin "15") (pinfunction "GPIO_15") (pintype "bidirectional"))
    )
    (net (code "230") (name "unconnected-(U10-RP_1A5-Pad14)") (class "Default")
      (node (ref "U10") (pin "14") (pinfunction "RP_1A5_14") (pintype "output"))
    )
    (net (code "231") (name "unconnected-(U10-RP_3A-Pad20)") (class "Default")
      (node (ref "U10") (pin "20") (pinfunction "RP_3A_20") (pintype "output"))
    )
  )
)
